# RastoBot-r2.net
KiCad netlist of a schematic drawn in EAGLE
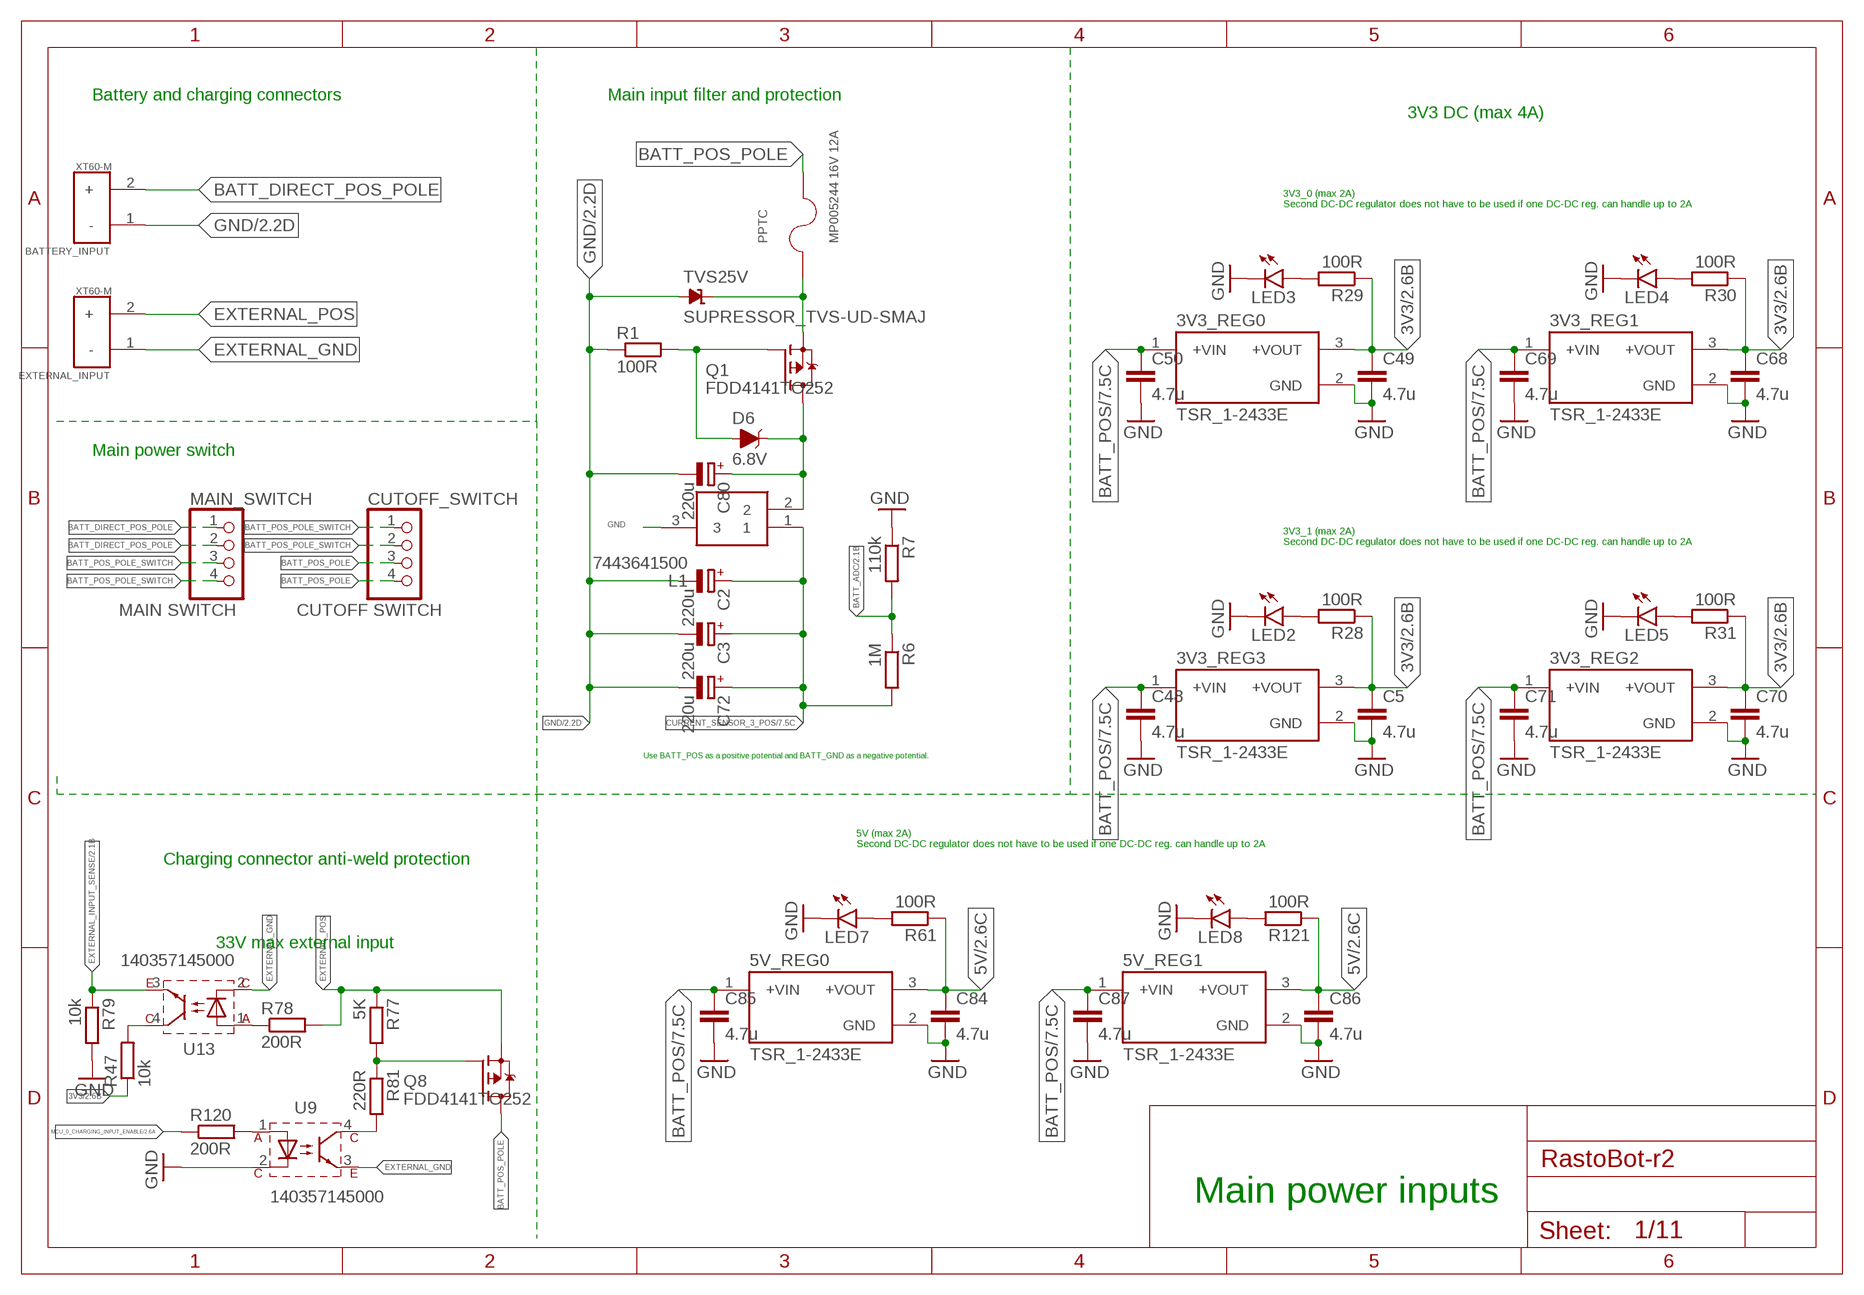
[diagram p0: schematic, sheet 1]
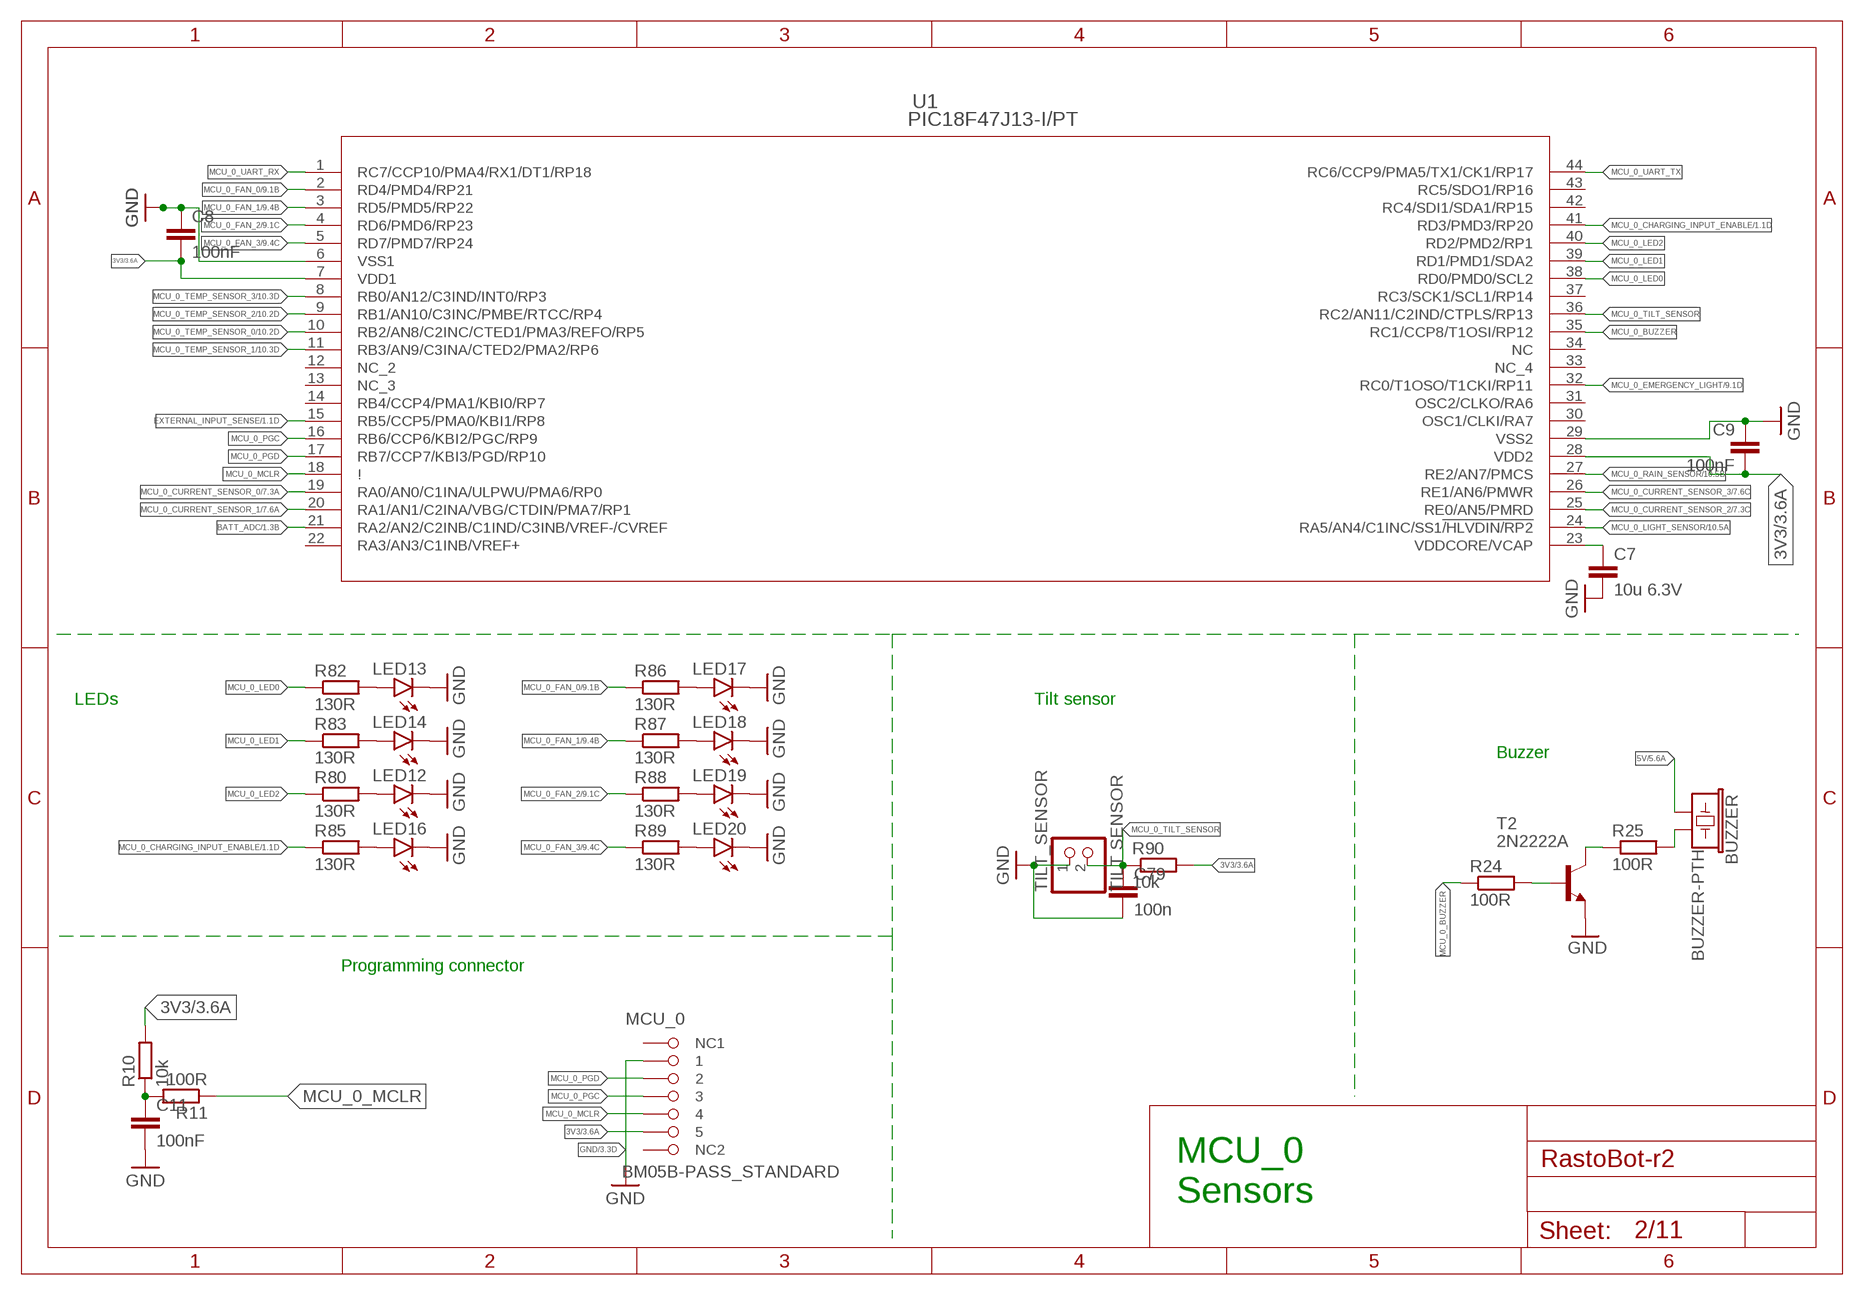
[diagram p1: schematic, sheet 2]
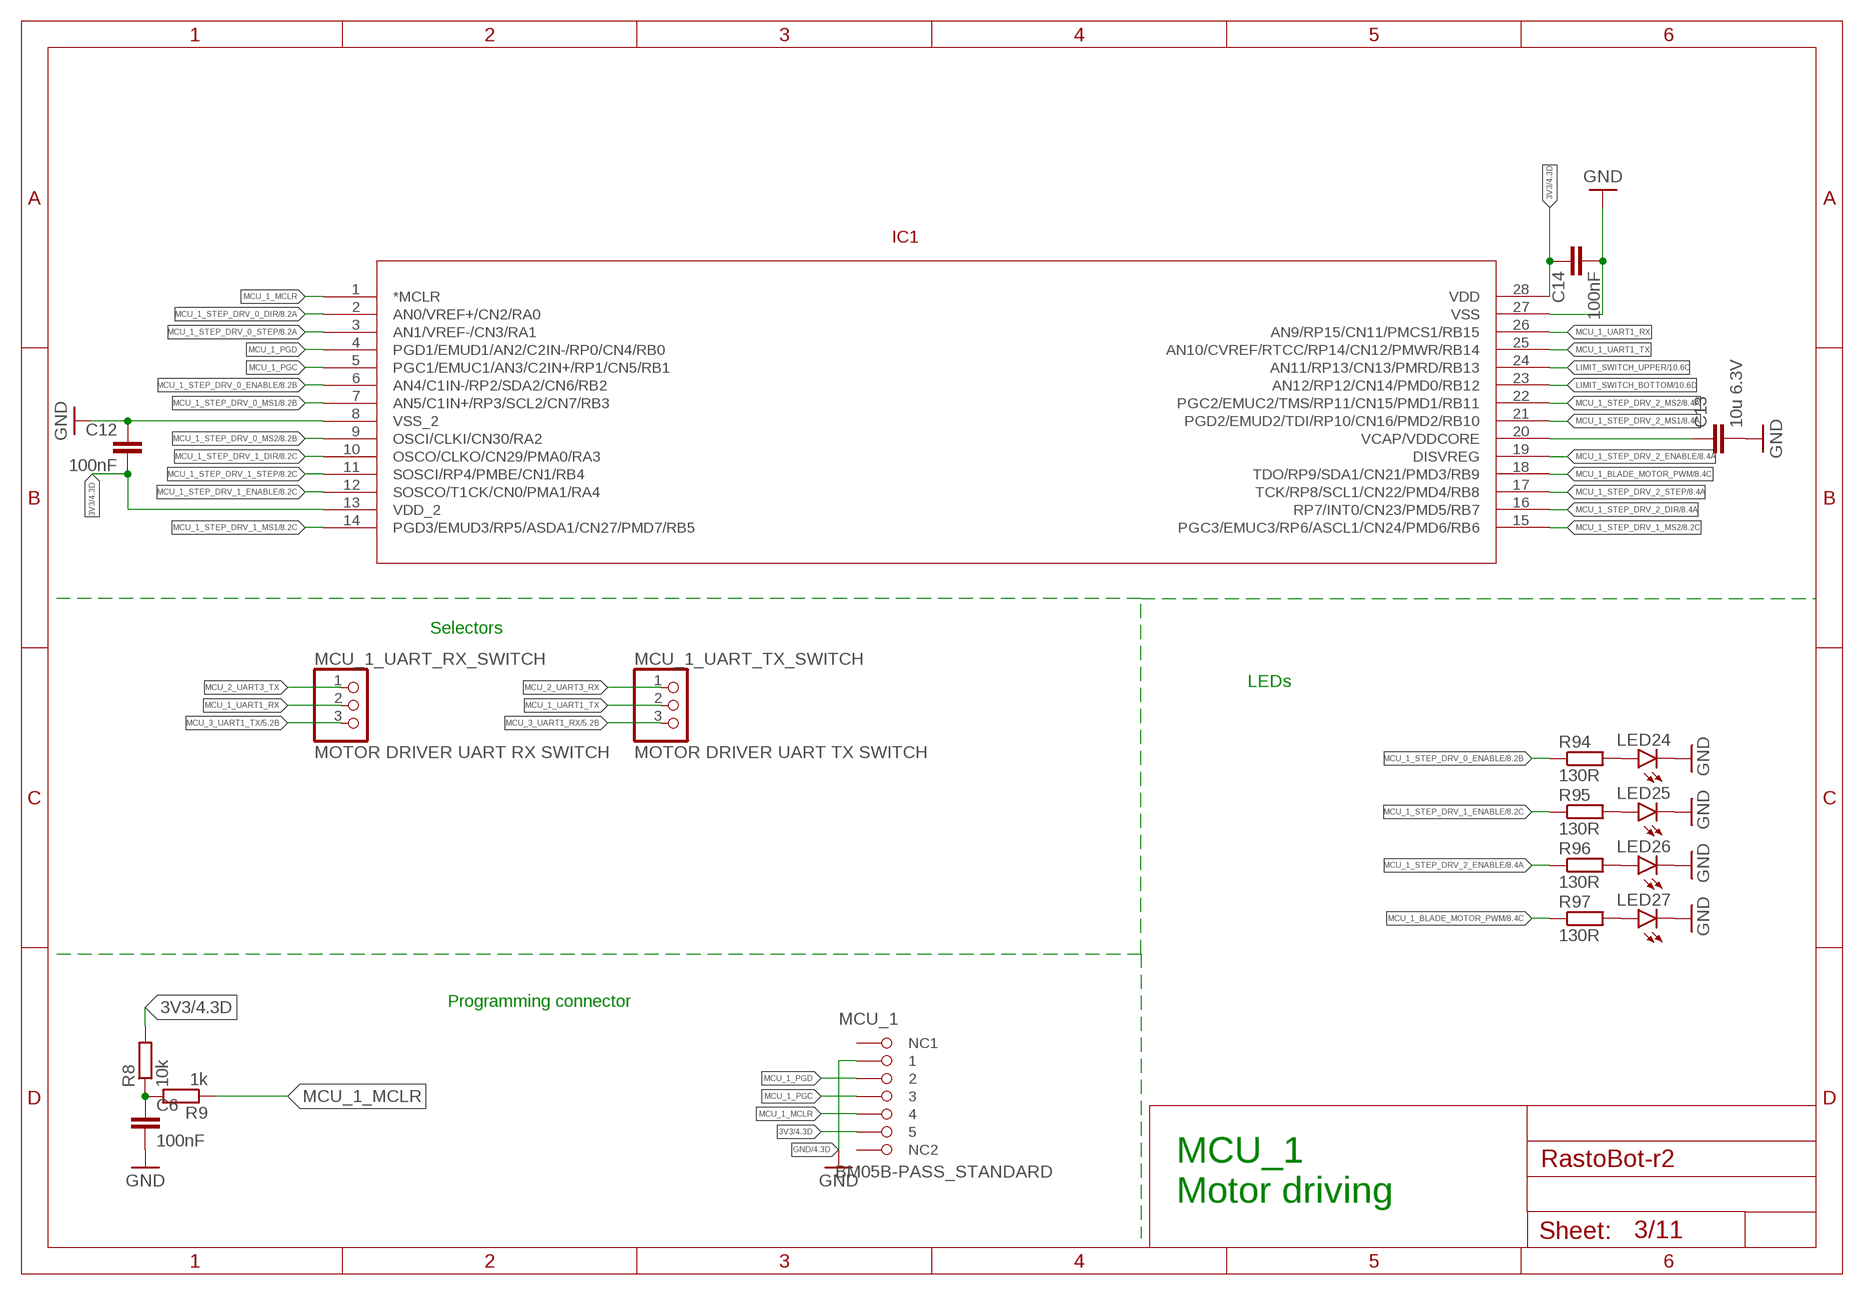
[diagram p2: schematic, sheet 3]
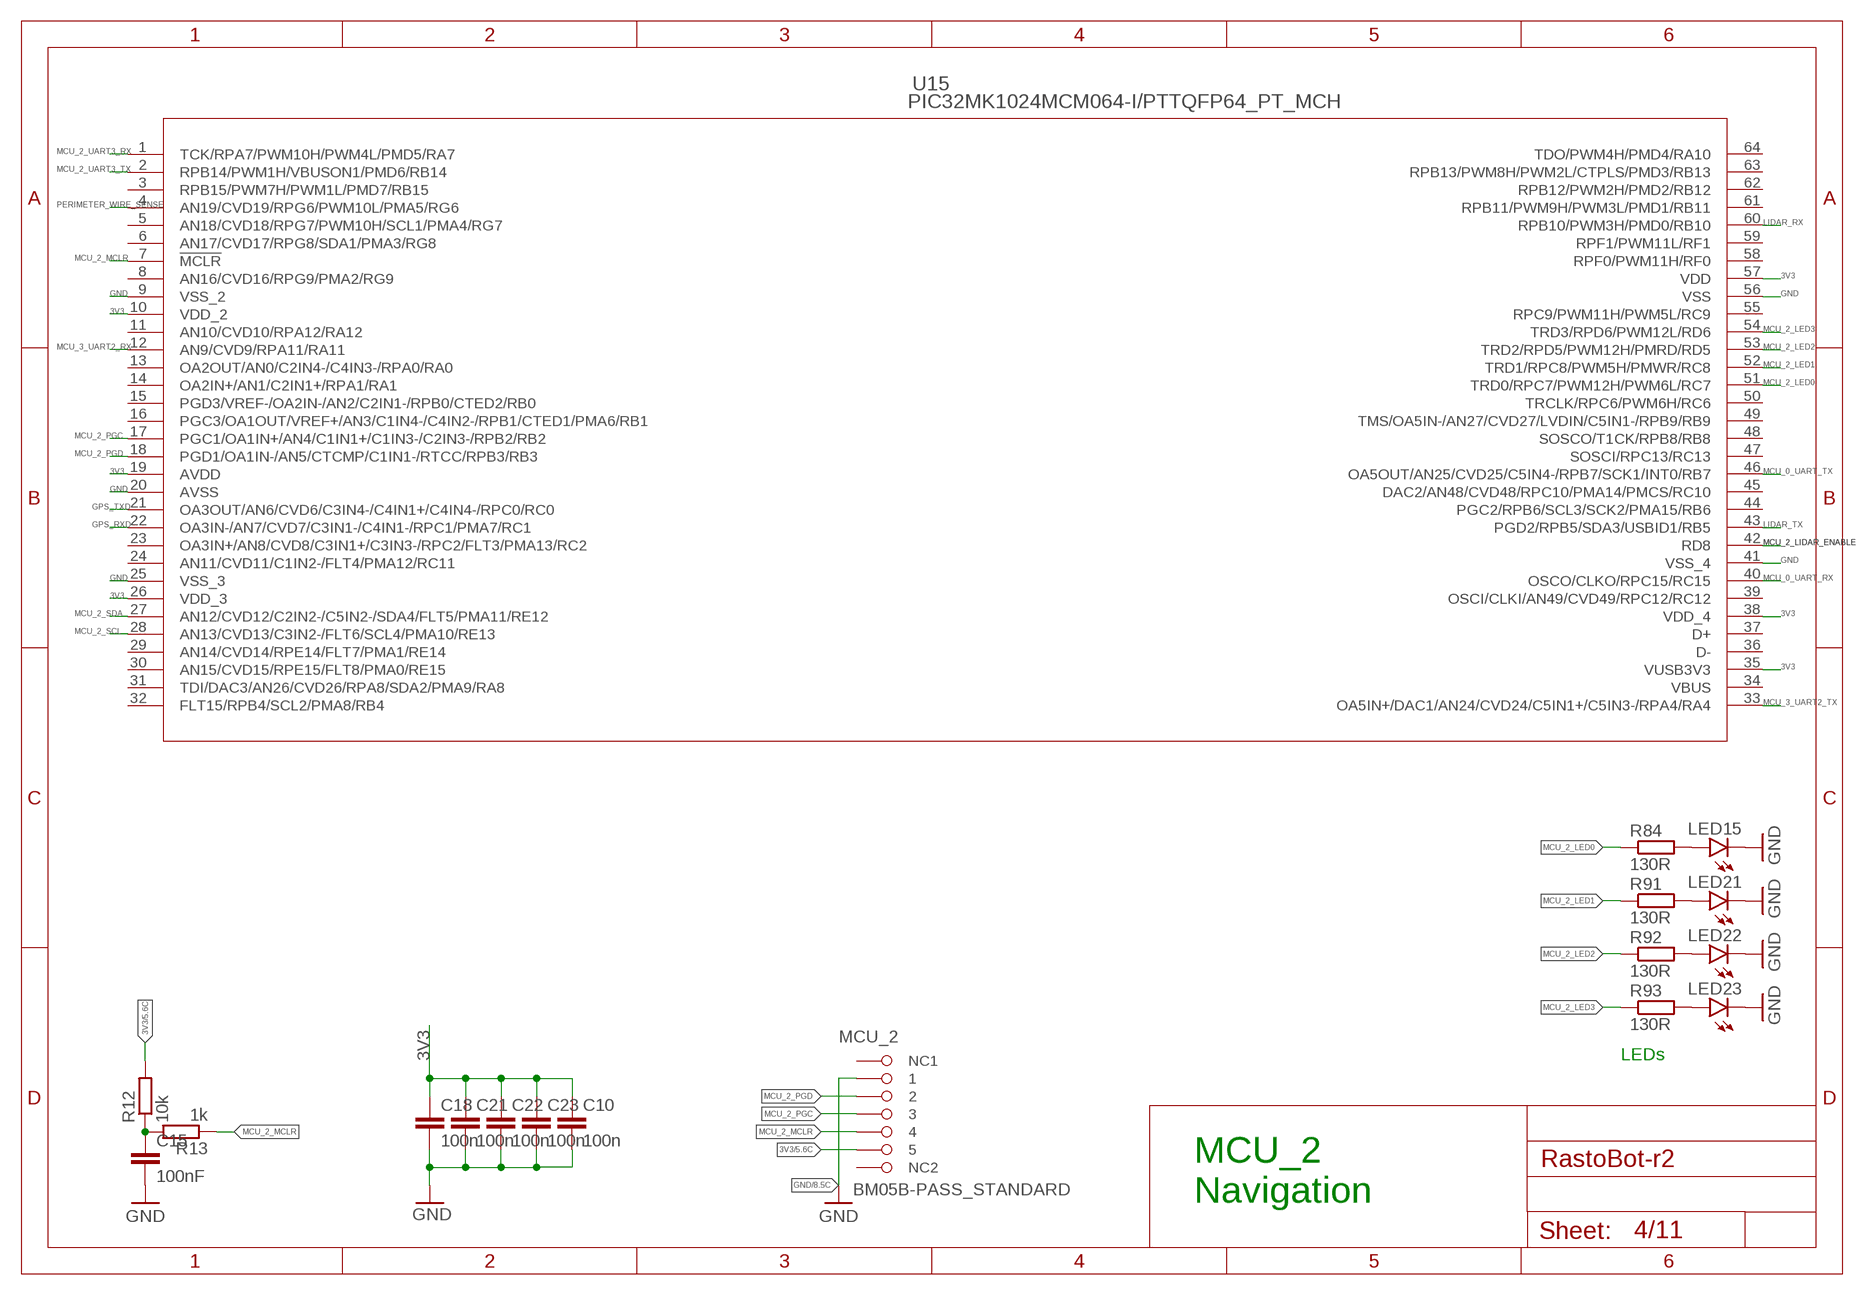
[diagram p3: schematic, sheet 4]
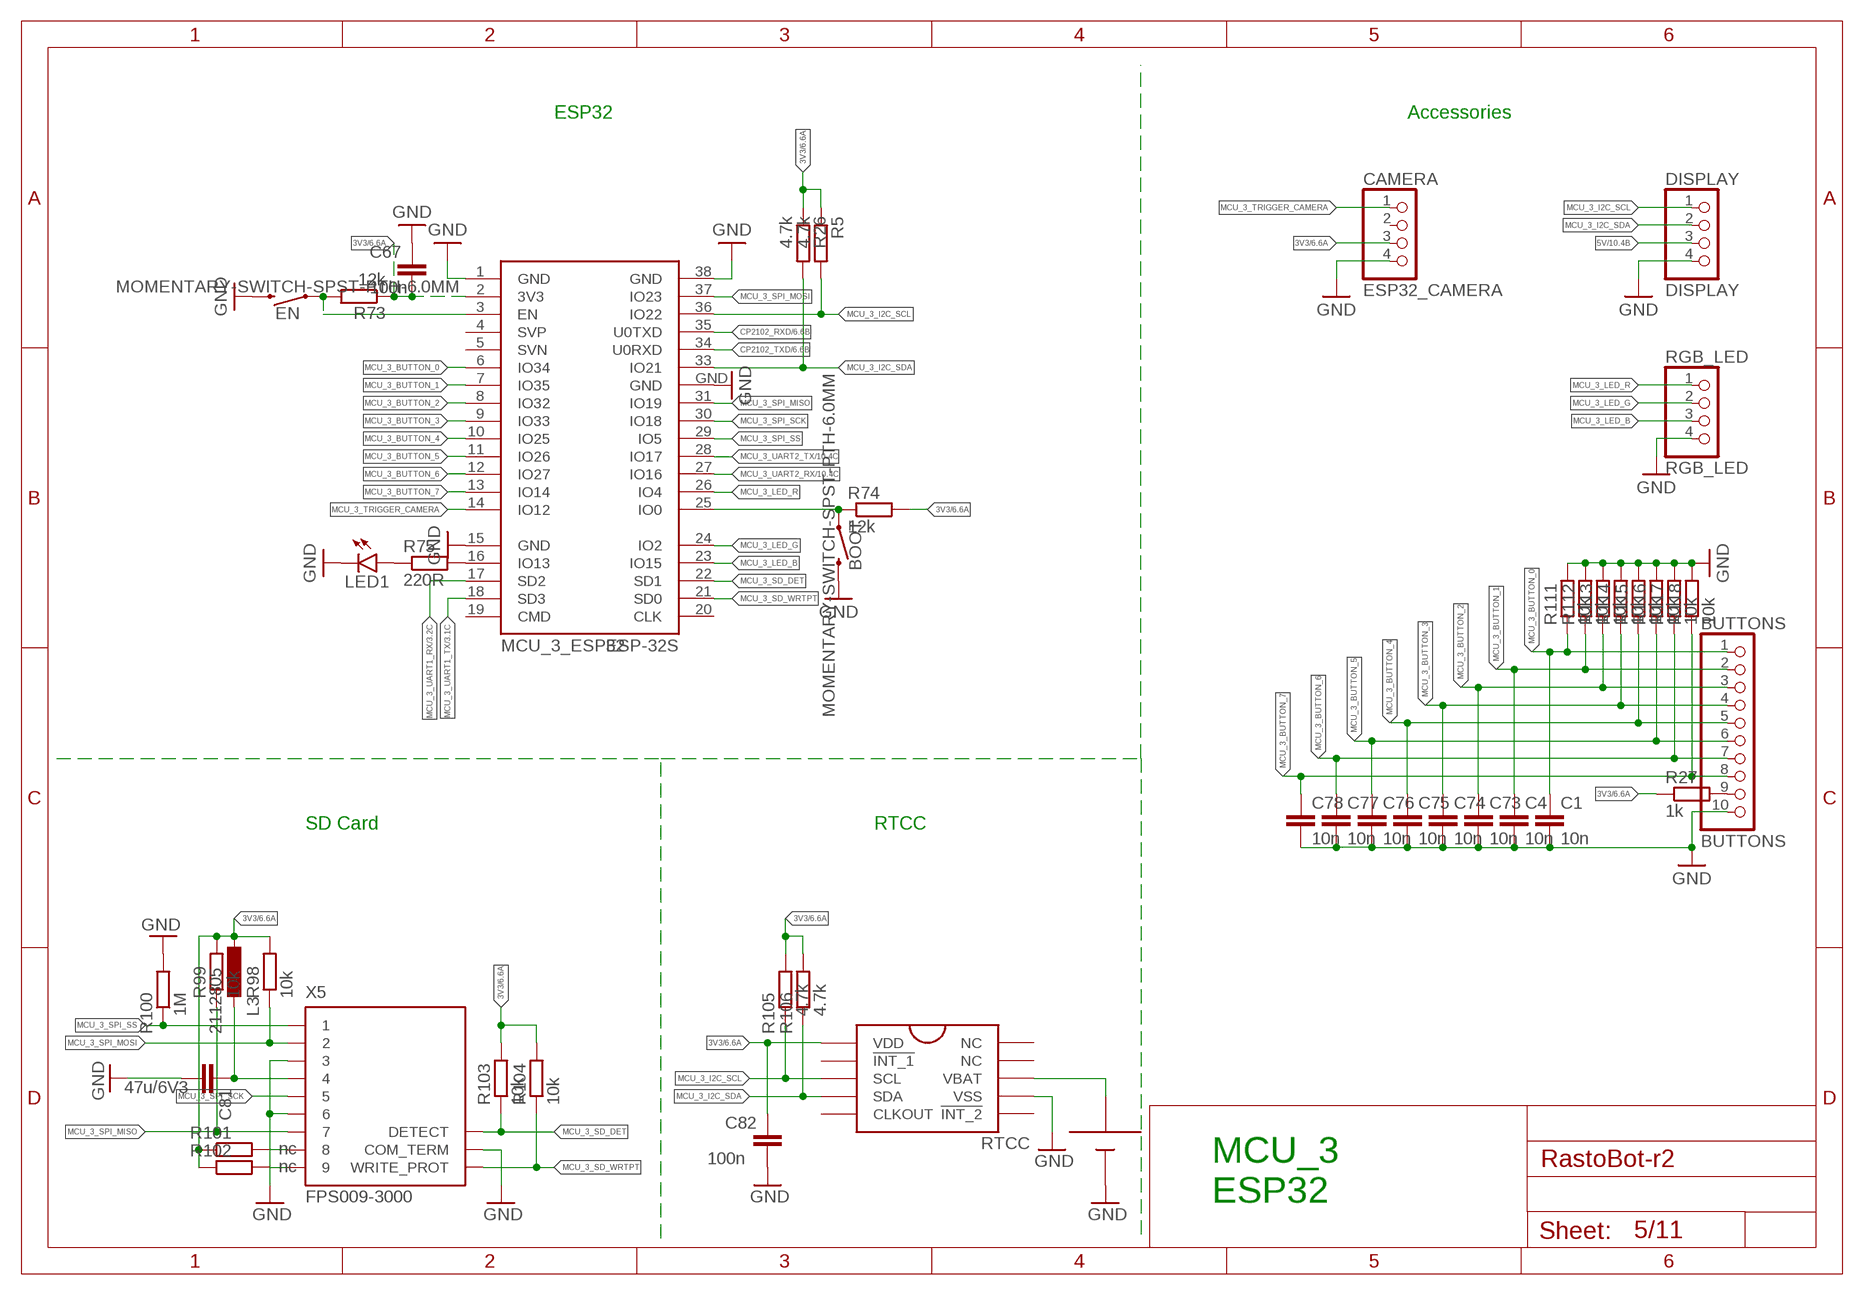
[diagram p4: schematic, sheet 5]
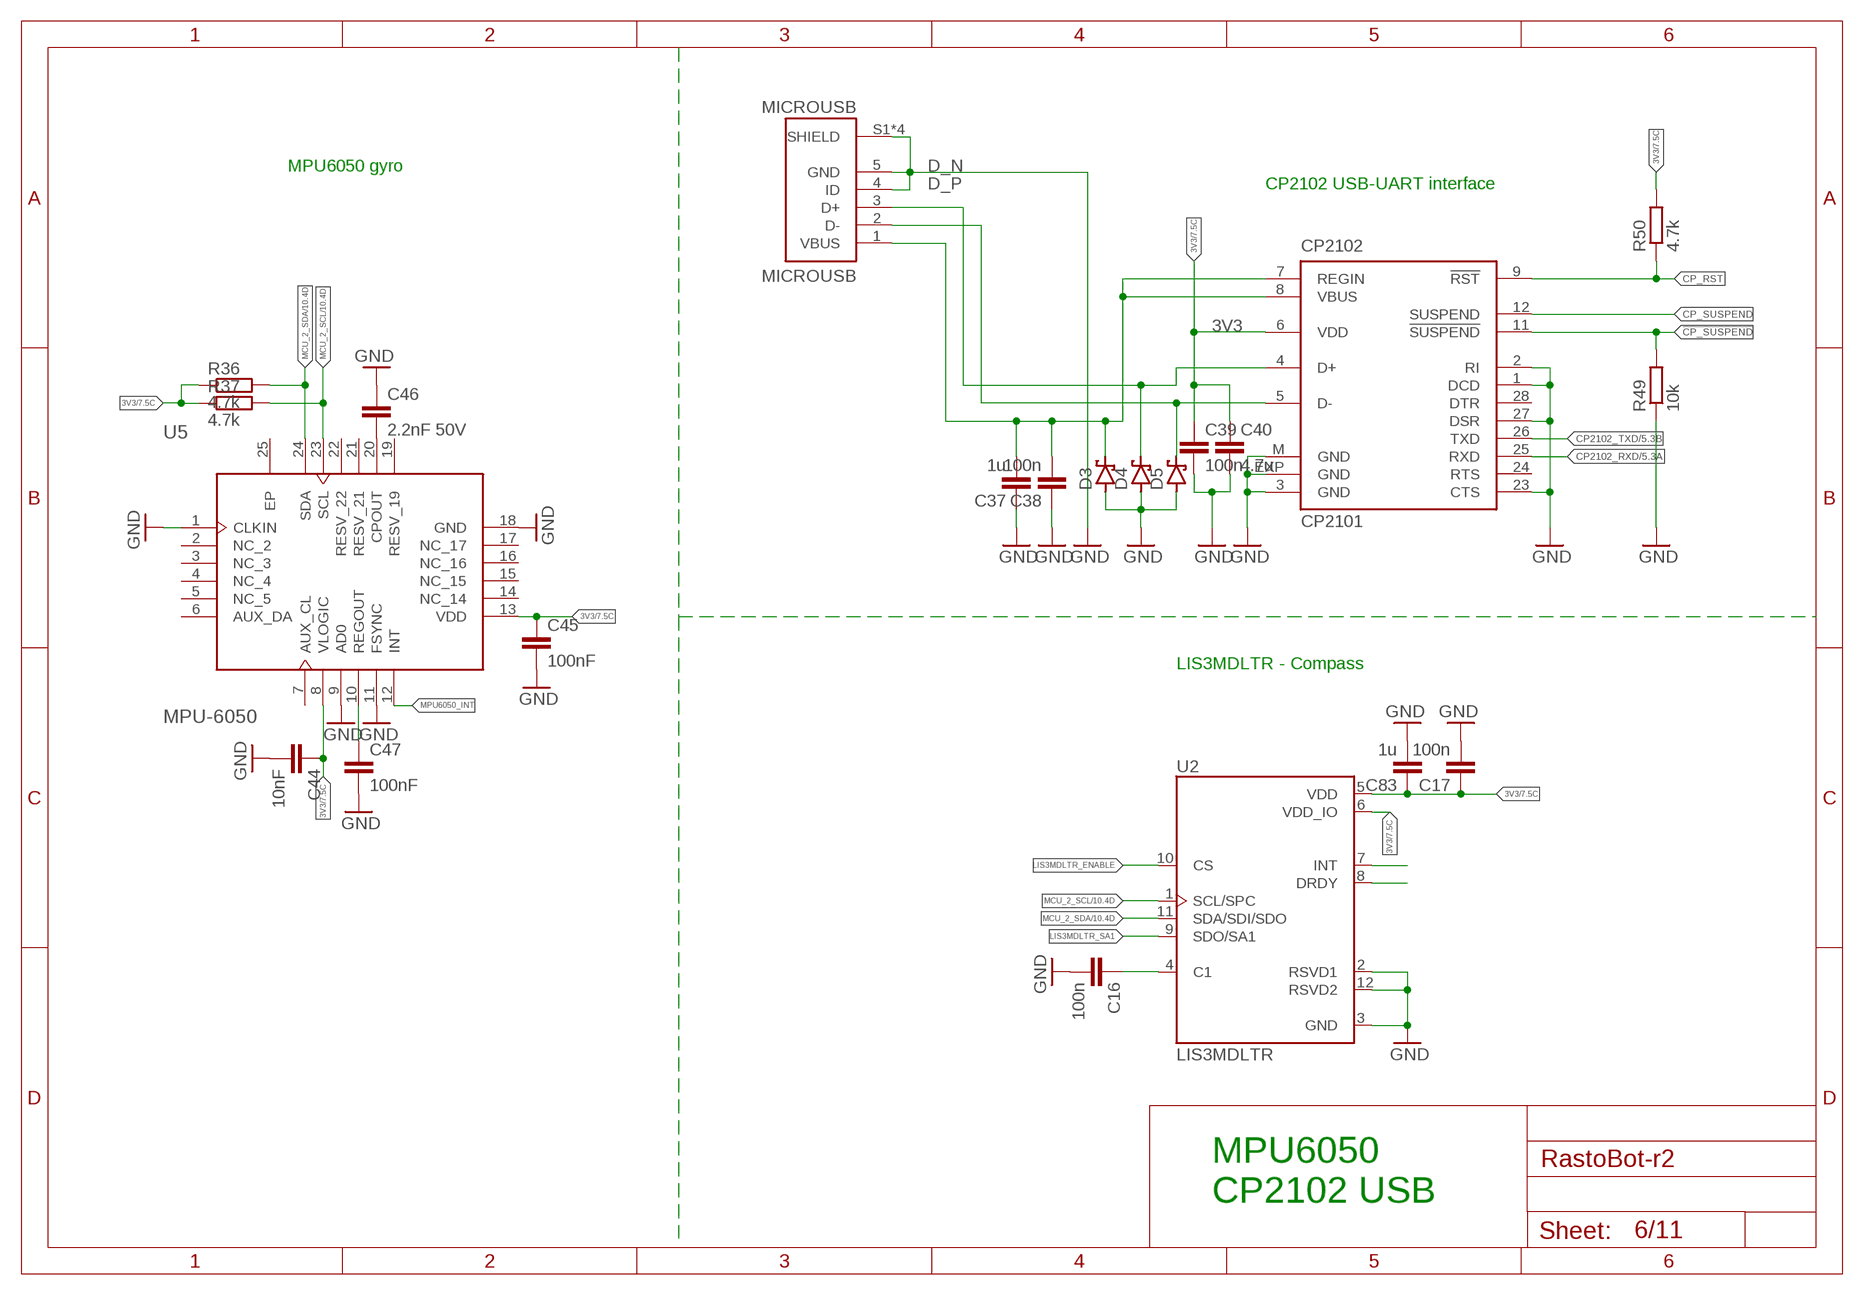
[diagram p5: schematic, sheet 6]
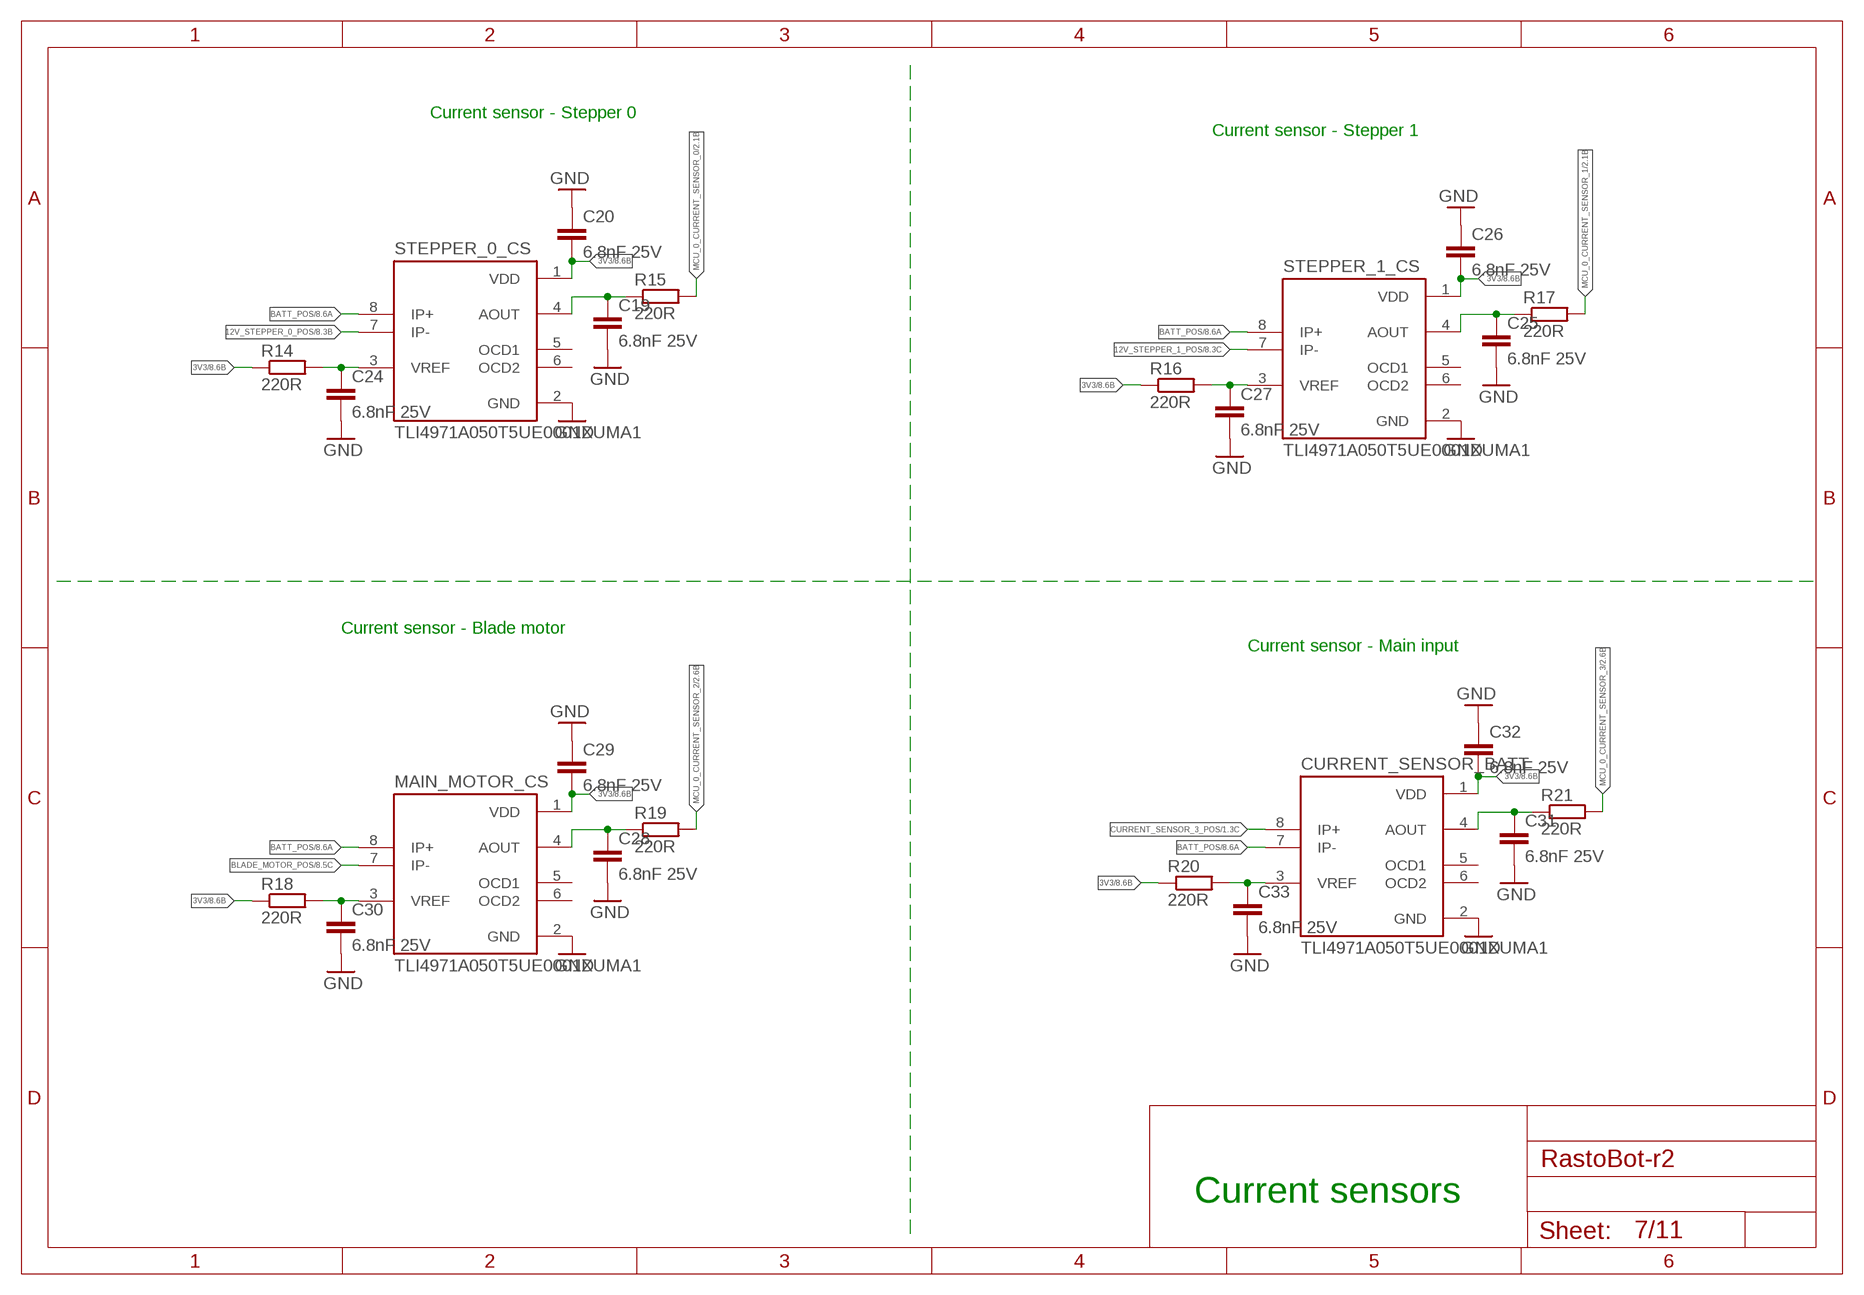
[diagram p6: schematic, sheet 7]
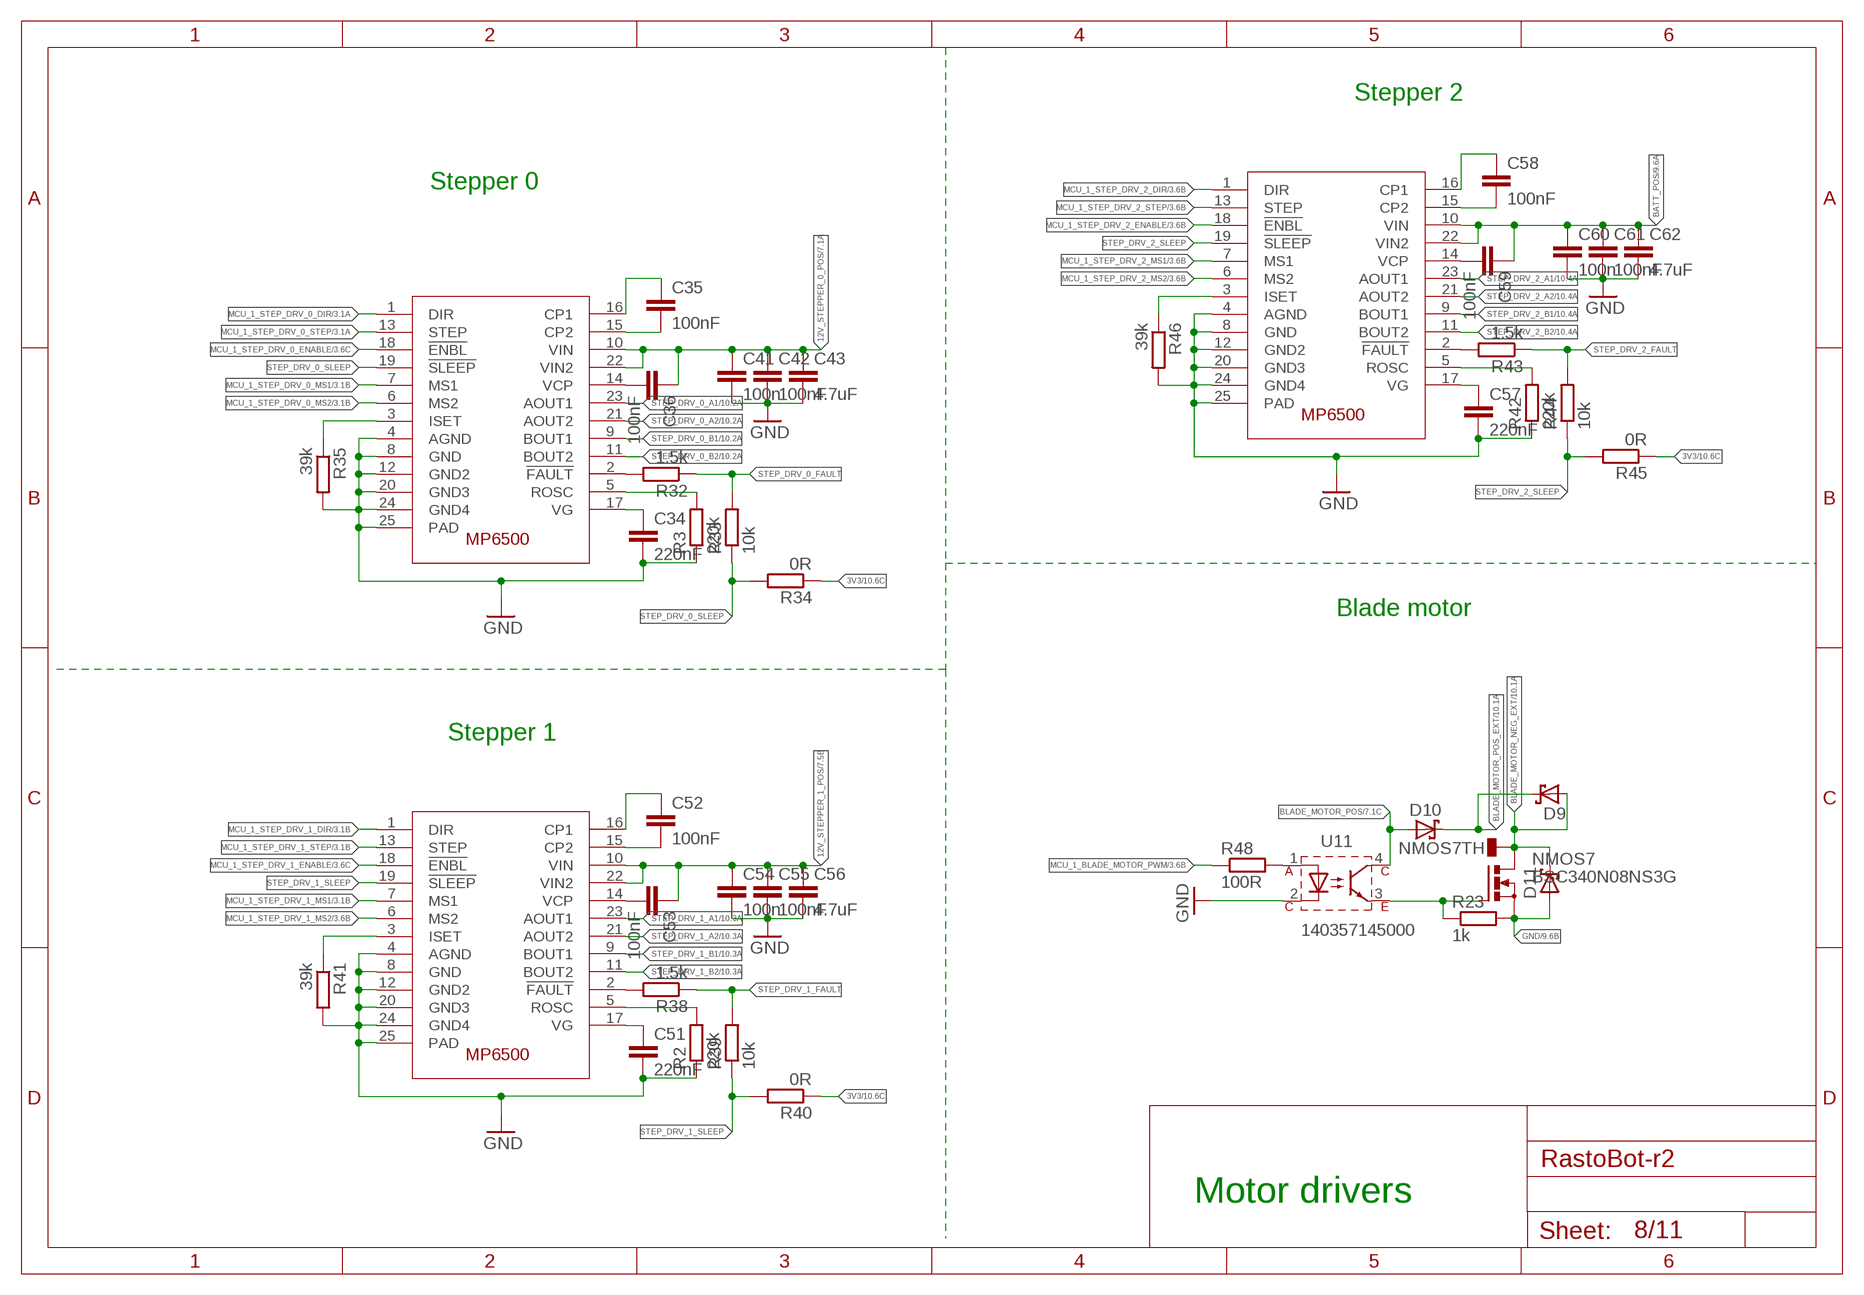
[diagram p7: schematic, sheet 8]
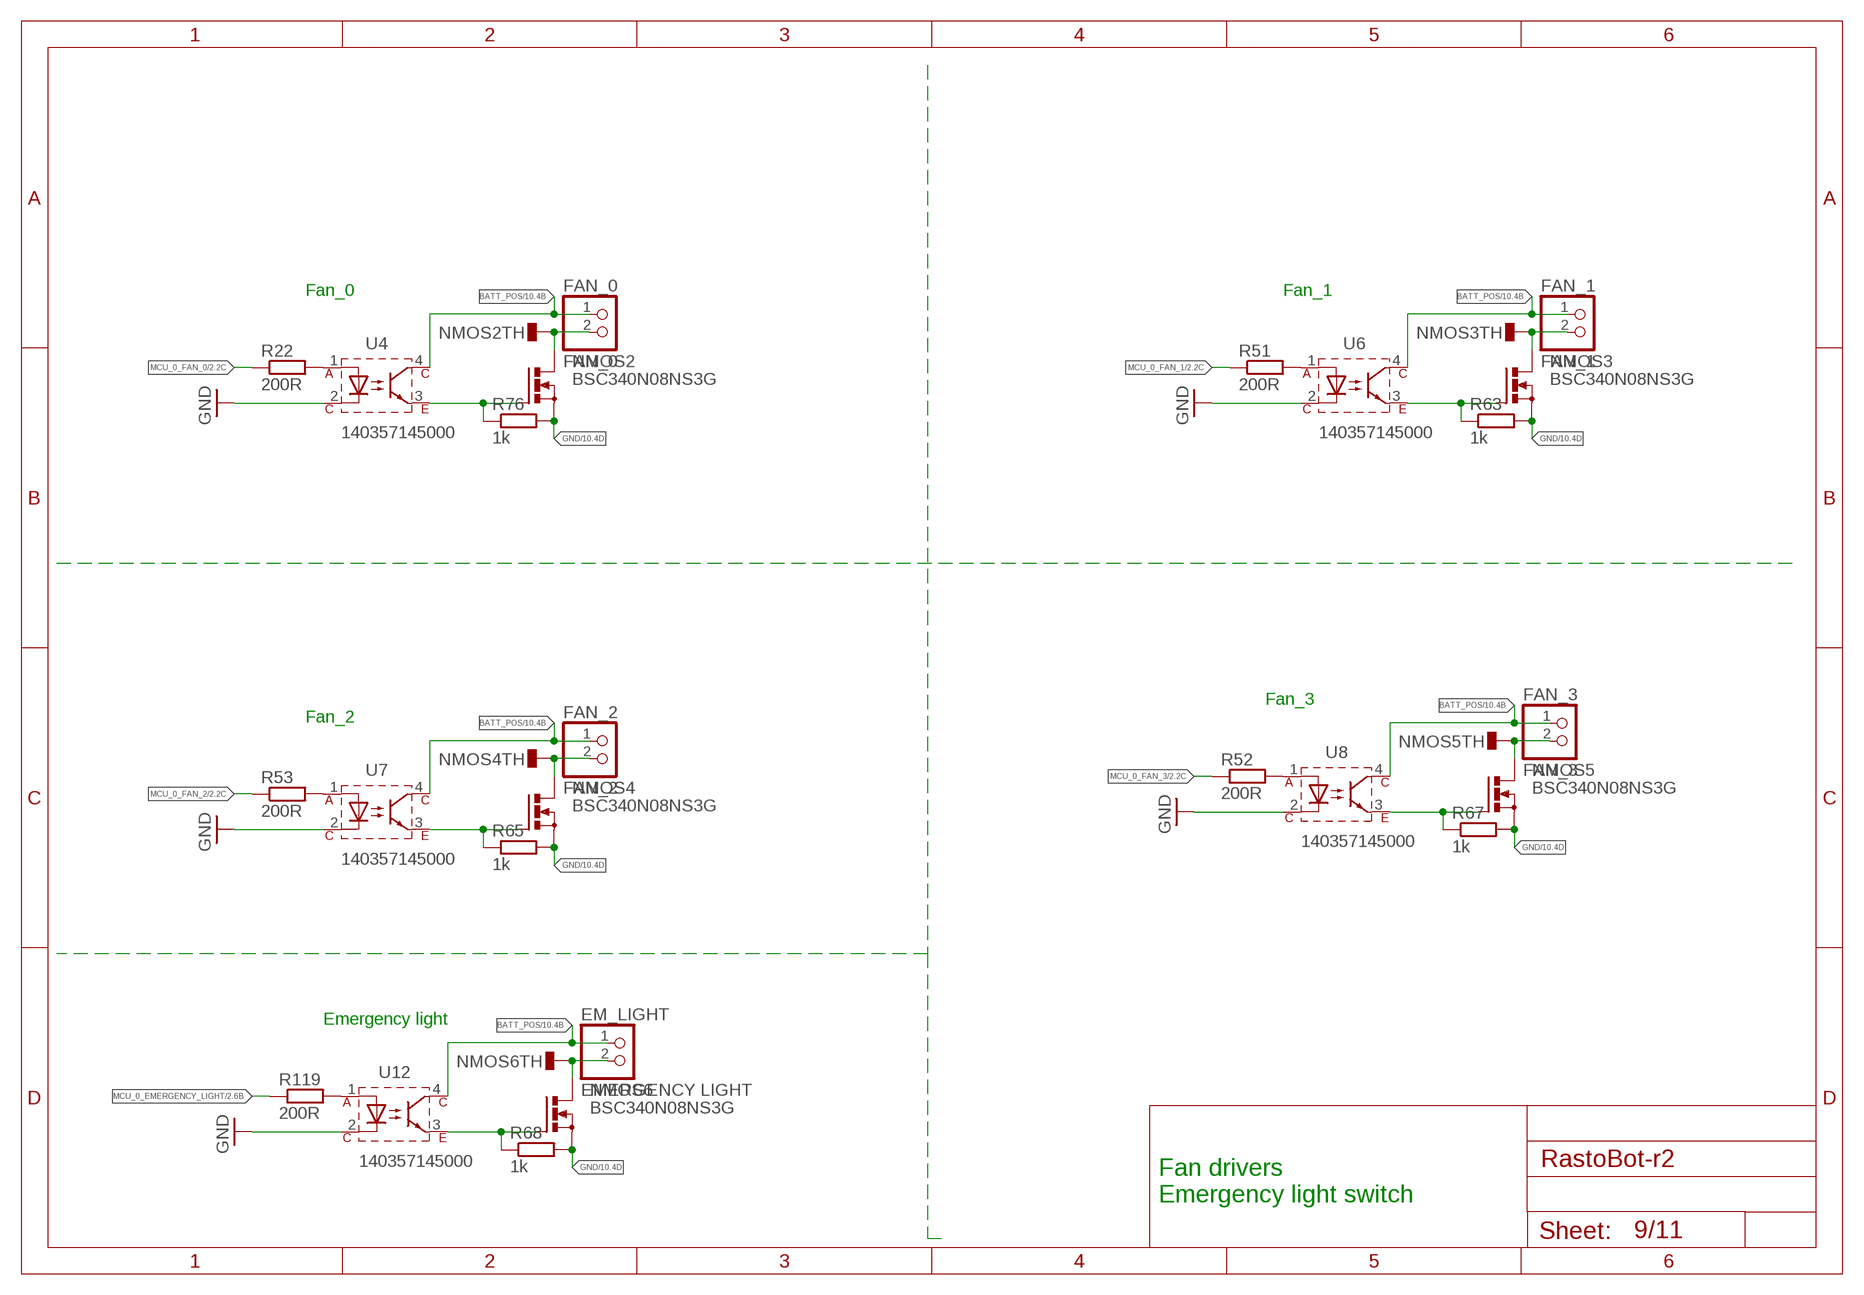
[diagram p8: schematic, sheet 9]
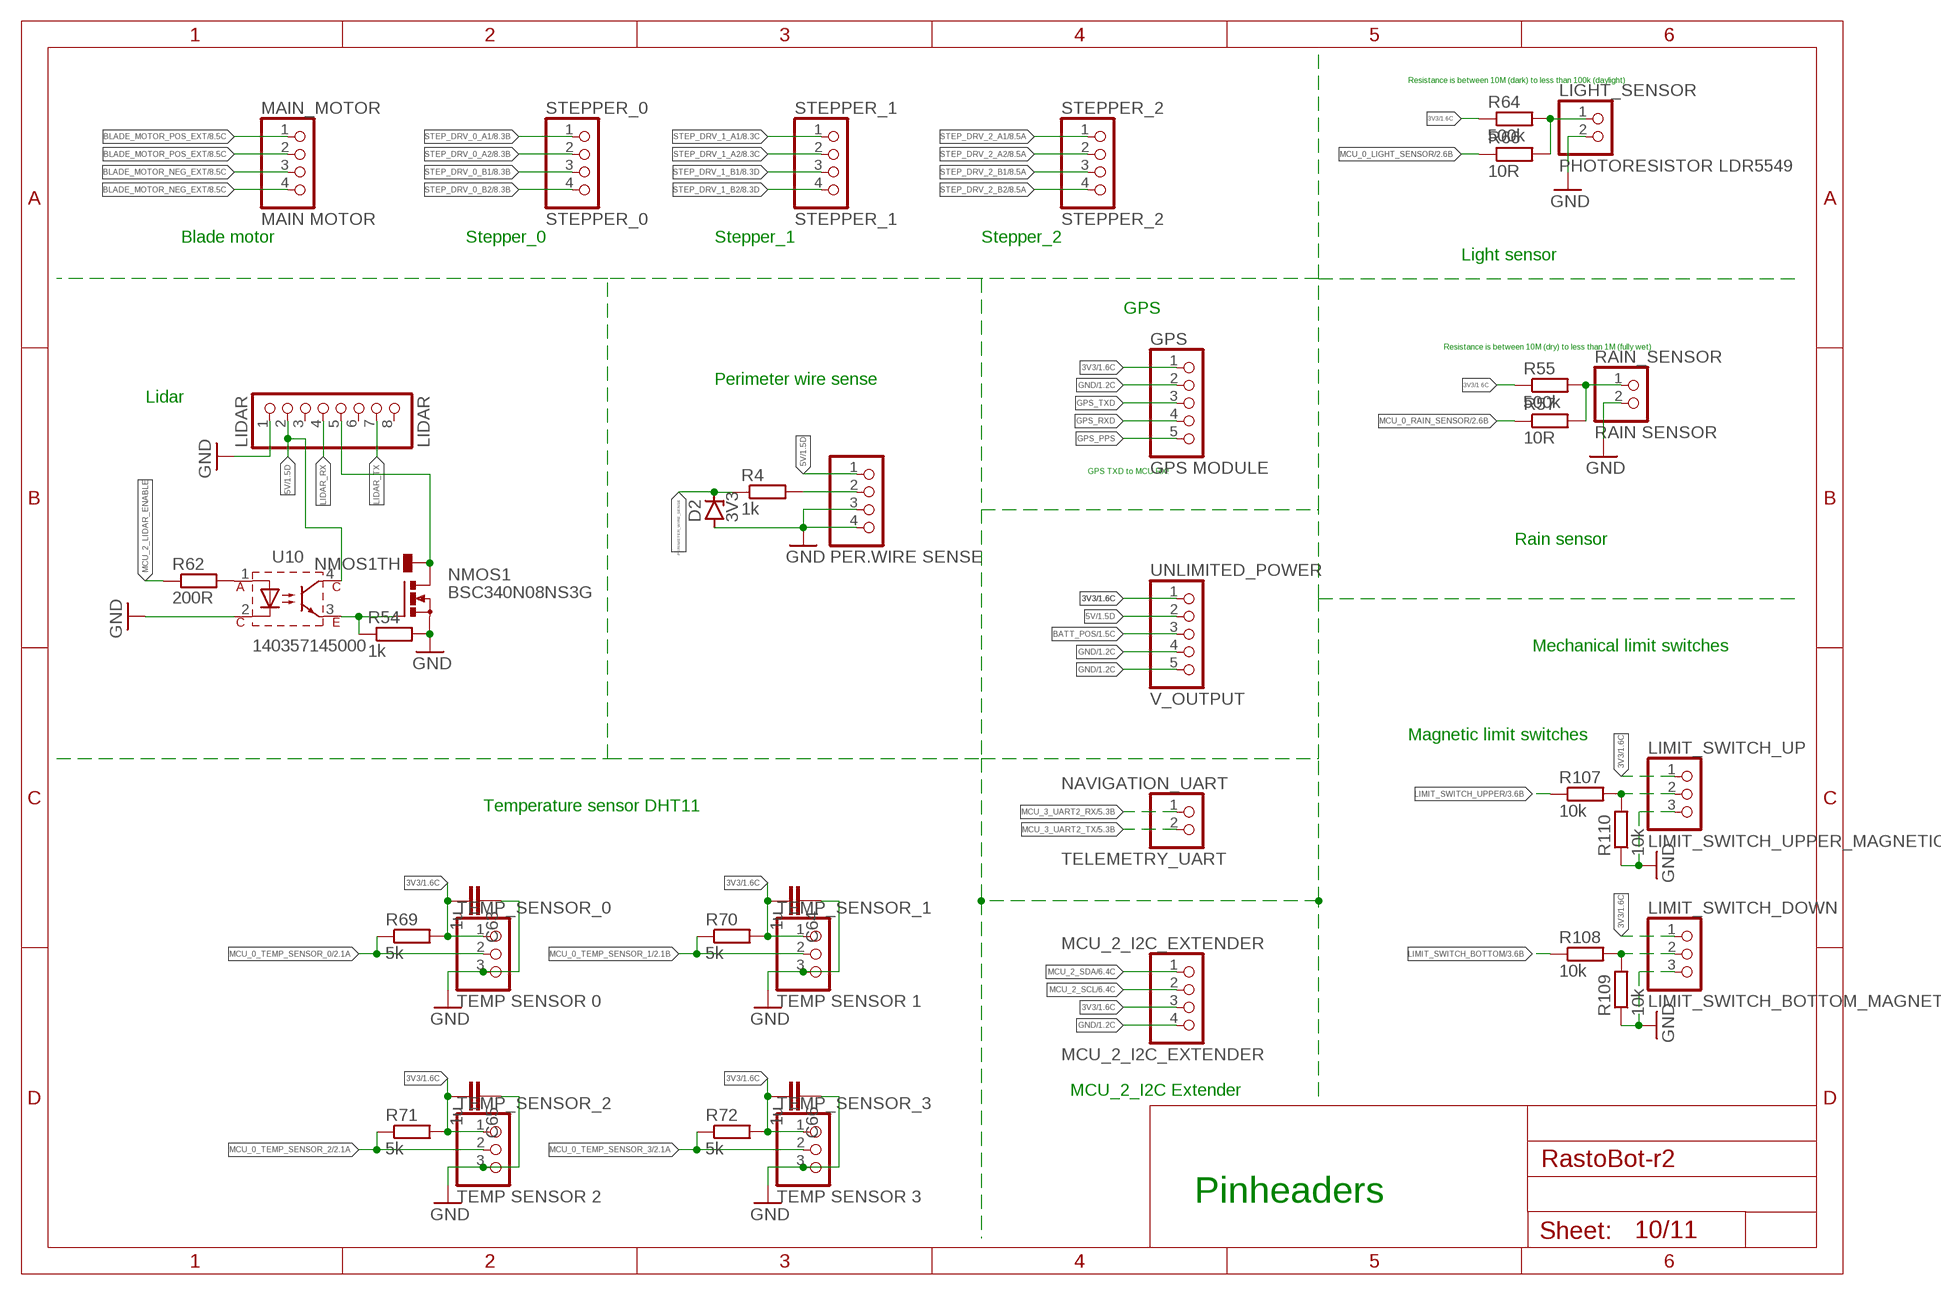
[diagram p9: schematic, sheet 10]
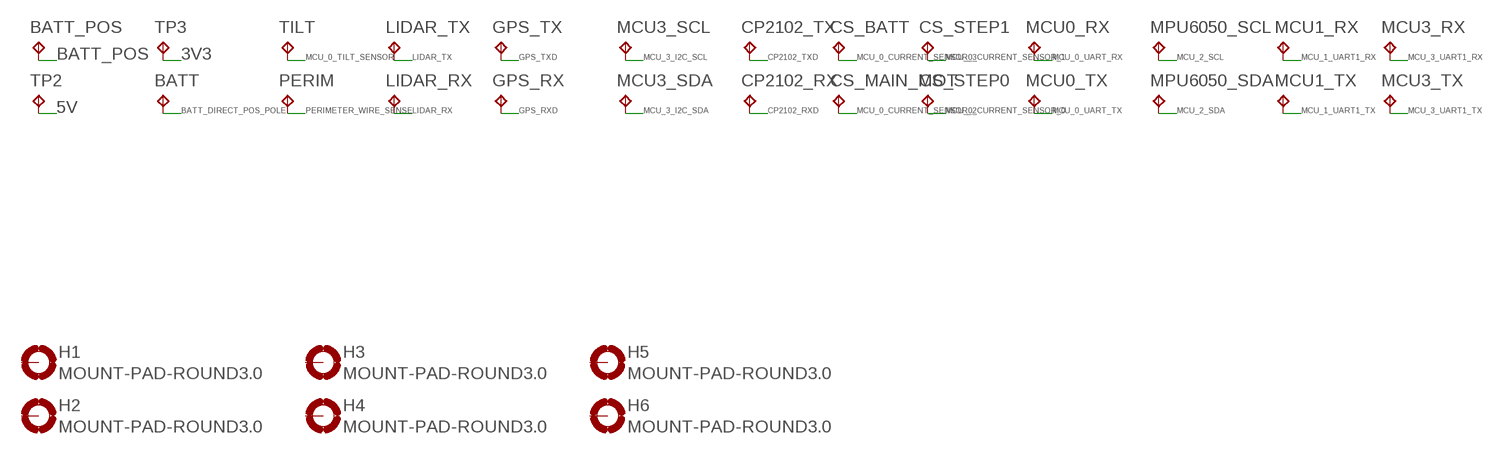
[diagram p10: schematic, sheet 11]

(export (version "E")
  (design (tool "Eeschema 10.0.6"))
  (components
    (comp (ref "BATT")
      (value "TPB1,27")
      (footprint "eagle-import:B1,27")
      (libsource (lib "eagle-import") (part "TPB1,27"))
    )
    (comp (ref "BATT_POS")
      (value "TPB1,27")
      (footprint "eagle-import:B1,27")
      (libsource (lib "eagle-import") (part "TPB1,27"))
    )
    (comp (ref "CP2102_RX")
      (value "TPB1,27")
      (footprint "eagle-import:B1,27")
      (libsource (lib "eagle-import") (part "TPB1,27"))
    )
    (comp (ref "CP2102_TX")
      (value "TPB1,27")
      (footprint "eagle-import:B1,27")
      (libsource (lib "eagle-import") (part "TPB1,27"))
    )
    (comp (ref "CS_BATT")
      (value "TPB1,27")
      (footprint "eagle-import:B1,27")
      (libsource (lib "eagle-import") (part "TPB1,27"))
    )
    (comp (ref "CS_MAIN_MOT")
      (value "TPB1,27")
      (footprint "eagle-import:B1,27")
      (libsource (lib "eagle-import") (part "TPB1,27"))
    )
    (comp (ref "CS_STEP0")
      (value "TPB1,27")
      (footprint "eagle-import:B1,27")
      (libsource (lib "eagle-import") (part "TPB1,27"))
    )
    (comp (ref "CS_STEP1")
      (value "TPB1,27")
      (footprint "eagle-import:B1,27")
      (libsource (lib "eagle-import") (part "TPB1,27"))
    )
    (comp (ref "GPS_RX")
      (value "TPB1,27")
      (footprint "eagle-import:B1,27")
      (libsource (lib "eagle-import") (part "TPB1,27"))
    )
    (comp (ref "GPS_TX")
      (value "TPB1,27")
      (footprint "eagle-import:B1,27")
      (libsource (lib "eagle-import") (part "TPB1,27"))
    )
    (comp (ref "H1")
      (value "MOUNT-PAD-ROUND3.0")
      (footprint "eagle-import:3,0-PAD")
      (libsource (lib "eagle-import") (part "MOUNT-PAD-ROUND3.0"))
    )
    (comp (ref "H2")
      (value "MOUNT-PAD-ROUND3.0")
      (footprint "eagle-import:3,0-PAD")
      (libsource (lib "eagle-import") (part "MOUNT-PAD-ROUND3.0"))
    )
    (comp (ref "H3")
      (value "MOUNT-PAD-ROUND3.0")
      (footprint "eagle-import:3,0-PAD")
      (libsource (lib "eagle-import") (part "MOUNT-PAD-ROUND3.0"))
    )
    (comp (ref "H4")
      (value "MOUNT-PAD-ROUND3.0")
      (footprint "eagle-import:3,0-PAD")
      (libsource (lib "eagle-import") (part "MOUNT-PAD-ROUND3.0"))
    )
    (comp (ref "H5")
      (value "MOUNT-PAD-ROUND3.0")
      (footprint "eagle-import:3,0-PAD")
      (libsource (lib "eagle-import") (part "MOUNT-PAD-ROUND3.0"))
    )
    (comp (ref "H6")
      (value "MOUNT-PAD-ROUND3.0")
      (footprint "eagle-import:3,0-PAD")
      (libsource (lib "eagle-import") (part "MOUNT-PAD-ROUND3.0"))
    )
    (comp (ref "LIDAR_RX")
      (value "TPB1,27")
      (footprint "eagle-import:B1,27")
      (libsource (lib "eagle-import") (part "TPB1,27"))
    )
    (comp (ref "LIDAR_TX")
      (value "TPB1,27")
      (footprint "eagle-import:B1,27")
      (libsource (lib "eagle-import") (part "TPB1,27"))
    )
    (comp (ref "MCU0_RX")
      (value "TPB1,27")
      (footprint "eagle-import:B1,27")
      (libsource (lib "eagle-import") (part "TPB1,27"))
    )
    (comp (ref "MCU0_TX")
      (value "TPB1,27")
      (footprint "eagle-import:B1,27")
      (libsource (lib "eagle-import") (part "TPB1,27"))
    )
    (comp (ref "MCU1_RX")
      (value "TPB1,27")
      (footprint "eagle-import:B1,27")
      (libsource (lib "eagle-import") (part "TPB1,27"))
    )
    (comp (ref "MCU1_TX")
      (value "TPB1,27")
      (footprint "eagle-import:B1,27")
      (libsource (lib "eagle-import") (part "TPB1,27"))
    )
    (comp (ref "MCU3_RX")
      (value "TPB1,27")
      (footprint "eagle-import:B1,27")
      (libsource (lib "eagle-import") (part "TPB1,27"))
    )
    (comp (ref "MCU3_SCL")
      (value "TPB1,27")
      (footprint "eagle-import:B1,27")
      (libsource (lib "eagle-import") (part "TPB1,27"))
    )
    (comp (ref "MCU3_SDA")
      (value "TPB1,27")
      (footprint "eagle-import:B1,27")
      (libsource (lib "eagle-import") (part "TPB1,27"))
    )
    (comp (ref "MCU3_TX")
      (value "TPB1,27")
      (footprint "eagle-import:B1,27")
      (libsource (lib "eagle-import") (part "TPB1,27"))
    )
    (comp (ref "MPU6050_SCL")
      (value "TPB1,27")
      (footprint "eagle-import:B1,27")
      (libsource (lib "eagle-import") (part "TPB1,27"))
    )
    (comp (ref "MPU6050_SDA")
      (value "TPB1,27")
      (footprint "eagle-import:B1,27")
      (libsource (lib "eagle-import") (part "TPB1,27"))
    )
    (comp (ref "PERIM")
      (value "TPB1,27")
      (footprint "eagle-import:B1,27")
      (libsource (lib "eagle-import") (part "TPB1,27"))
    )
    (comp (ref "TILT")
      (value "TPB1,27")
      (footprint "eagle-import:B1,27")
      (libsource (lib "eagle-import") (part "TPB1,27"))
    )
    (comp (ref "TP2")
      (value "TPB1,27")
      (footprint "eagle-import:B1,27")
      (libsource (lib "eagle-import") (part "TPB1,27"))
    )
    (comp (ref "TP3")
      (value "TPB1,27")
      (footprint "eagle-import:B1,27")
      (libsource (lib "eagle-import") (part "TPB1,27"))
    )
    (comp (ref "C10")
      (value "100n")
      (footprint "eagle-import:C0603")
      (libsource (lib "eagle-import") (part "C-EUC0603"))
    )
    (comp (ref "C15")
      (value "100nF")
      (footprint "eagle-import:C0603")
      (libsource (lib "eagle-import") (part "rcl_334_C-EUC0603"))
    )
    (comp (ref "C18")
      (value "100n")
      (footprint "eagle-import:C0603")
      (libsource (lib "eagle-import") (part "C-EUC0603"))
    )
    (comp (ref "C21")
      (value "100n")
      (footprint "eagle-import:C0603")
      (libsource (lib "eagle-import") (part "C-EUC0603"))
    )
    (comp (ref "C22")
      (value "100n")
      (footprint "eagle-import:C0603")
      (libsource (lib "eagle-import") (part "C-EUC0603"))
    )
    (comp (ref "C23")
      (value "100n")
      (footprint "eagle-import:C0603")
      (libsource (lib "eagle-import") (part "C-EUC0603"))
    )
    (comp (ref "LED15")
      (value "LEDSML0805")
      (footprint "eagle-import:SML0805")
      (libsource (lib "eagle-import") (part "LEDSML0805"))
    )
    (comp (ref "LED21")
      (value "LEDSML0805")
      (footprint "eagle-import:SML0805")
      (libsource (lib "eagle-import") (part "LEDSML0805"))
    )
    (comp (ref "LED22")
      (value "LEDSML0805")
      (footprint "eagle-import:SML0805")
      (libsource (lib "eagle-import") (part "LEDSML0805"))
    )
    (comp (ref "LED23")
      (value "LEDSML0805")
      (footprint "eagle-import:SML0805")
      (libsource (lib "eagle-import") (part "LEDSML0805"))
    )
    (comp (ref "MCU_2")
      (value "BM05B-PASS_STANDARD")
      (footprint "eagle-import:BM05B-PASS")
      (libsource (lib "eagle-import") (part "BM05B-PASS_STANDARD"))
    )
    (comp (ref "R12")
      (value "10k")
      (footprint "eagle-import:R0805")
      (libsource (lib "eagle-import") (part "rcl_334_R-EU_R0805"))
    )
    (comp (ref "R13")
      (value "1k")
      (footprint "eagle-import:R0805")
      (libsource (lib "eagle-import") (part "rcl_334_R-EU_R0805"))
    )
    (comp (ref "R84")
      (value "130R")
      (footprint "eagle-import:R0603")
      (libsource (lib "eagle-import") (part "rcl_334_R-EU_R0603"))
    )
    (comp (ref "R91")
      (value "130R")
      (footprint "eagle-import:R0603")
      (libsource (lib "eagle-import") (part "rcl_334_R-EU_R0603"))
    )
    (comp (ref "R92")
      (value "130R")
      (footprint "eagle-import:R0603")
      (libsource (lib "eagle-import") (part "rcl_334_R-EU_R0603"))
    )
    (comp (ref "R93")
      (value "130R")
      (footprint "eagle-import:R0603")
      (libsource (lib "eagle-import") (part "rcl_334_R-EU_R0603"))
    )
    (comp (ref "U15")
      (value "PIC32MK1024MCM064-I/PTTQFP64_PT_MCH")
      (footprint "eagle-import:TQFP64_PT_MCH")
      (fields
        (field (name "MANUFACTURER_PART_NUMBER") "PIC32MK1024MCM064-I/PT")
        (field (name "COPYRIGHT") "Copyright (C) 2022 Ultra Librarian. All rights reserved.")
      )
      (libsource (lib "eagle-import") (part "PIC32MK1024MCM064-I/PTTQFP64_PT_MCH"))
    )
    (comp (ref "C34")
      (value "220nF")
      (footprint "eagle-import:C0603")
      (libsource (lib "eagle-import") (part "rcl_334_C-EUC0603"))
    )
    (comp (ref "C35")
      (value "100nF")
      (footprint "eagle-import:C0603")
      (libsource (lib "eagle-import") (part "rcl_334_C-EUC0603"))
    )
    (comp (ref "C36")
      (value "100nF")
      (footprint "eagle-import:C0603")
      (libsource (lib "eagle-import") (part "rcl_334_C-EUC0603"))
    )
    (comp (ref "C41")
      (value "100n")
      (footprint "eagle-import:C0603")
      (libsource (lib "eagle-import") (part "rcl_334_C-EUC0603"))
    )
    (comp (ref "C42")
      (value "100nF")
      (footprint "eagle-import:C0603")
      (libsource (lib "eagle-import") (part "rcl_334_C-EUC0603"))
    )
    (comp (ref "C43")
      (value "4.7uF")
      (footprint "eagle-import:C0603")
      (libsource (lib "eagle-import") (part "rcl_334_C-EUC0603"))
    )
    (comp (ref "C51")
      (value "220nF")
      (footprint "eagle-import:C0603")
      (libsource (lib "eagle-import") (part "rcl_334_C-EUC0603"))
    )
    (comp (ref "C52")
      (value "100nF")
      (footprint "eagle-import:C0603")
      (libsource (lib "eagle-import") (part "rcl_334_C-EUC0603"))
    )
    (comp (ref "C53")
      (value "100nF")
      (footprint "eagle-import:C0603")
      (libsource (lib "eagle-import") (part "rcl_334_C-EUC0603"))
    )
    (comp (ref "C54")
      (value "100n")
      (footprint "eagle-import:C0603")
      (libsource (lib "eagle-import") (part "rcl_334_C-EUC0603"))
    )
    (comp (ref "C55")
      (value "100nF")
      (footprint "eagle-import:C0603")
      (libsource (lib "eagle-import") (part "rcl_334_C-EUC0603"))
    )
    (comp (ref "C56")
      (value "4.7uF")
      (footprint "eagle-import:C0603")
      (libsource (lib "eagle-import") (part "rcl_334_C-EUC0603"))
    )
    (comp (ref "C57")
      (value "220nF")
      (footprint "eagle-import:C0603")
      (libsource (lib "eagle-import") (part "rcl_334_C-EUC0603"))
    )
    (comp (ref "C58")
      (value "100nF")
      (footprint "eagle-import:C0603")
      (libsource (lib "eagle-import") (part "rcl_334_C-EUC0603"))
    )
    (comp (ref "C59")
      (value "100nF")
      (footprint "eagle-import:C0603")
      (libsource (lib "eagle-import") (part "rcl_334_C-EUC0603"))
    )
    (comp (ref "C60")
      (value "100n")
      (footprint "eagle-import:C0603")
      (libsource (lib "eagle-import") (part "rcl_334_C-EUC0603"))
    )
    (comp (ref "C61")
      (value "100nF")
      (footprint "eagle-import:C0603")
      (libsource (lib "eagle-import") (part "rcl_334_C-EUC0603"))
    )
    (comp (ref "C62")
      (value "4.7uF")
      (footprint "eagle-import:C0603")
      (libsource (lib "eagle-import") (part "rcl_334_C-EUC0603"))
    )
    (comp (ref "D9")
      (value "SCHOTTKY-DIODEAG")
      (footprint "eagle-import:AG")
      (libsource (lib "eagle-import") (part "SCHOTTKY-DIODEAG"))
    )
    (comp (ref "D10")
      (value "SCHOTTKY-DIODEAG")
      (footprint "eagle-import:AG")
      (libsource (lib "eagle-import") (part "SCHOTTKY-DIODEAG"))
    )
    (comp (ref "D11")
      (value "SCHOTTKY-DIODEAG")
      (footprint "eagle-import:AG")
      (libsource (lib "eagle-import") (part "SCHOTTKY-DIODEAG"))
    )
    (comp (ref "NMOS7")
      (value "BSC340N08NS3G")
      (footprint "eagle-import:PG-TDSON-8")
      (libsource (lib "eagle-import") (part "BSC340N08NS3G"))
    )
    (comp (ref "R2")
      (value "220k")
      (footprint "eagle-import:R0603")
      (libsource (lib "eagle-import") (part "rcl_334_R-EU_R0603"))
    )
    (comp (ref "R3")
      (value "220k")
      (footprint "eagle-import:R0603")
      (libsource (lib "eagle-import") (part "rcl_334_R-EU_R0603"))
    )
    (comp (ref "R23")
      (value "1k")
      (footprint "eagle-import:R0805")
      (libsource (lib "eagle-import") (part "rcl_334_R-EU_R0805"))
    )
    (comp (ref "R32")
      (value "1.5k")
      (footprint "eagle-import:R0603")
      (libsource (lib "eagle-import") (part "rcl_334_R-EU_R0603"))
    )
    (comp (ref "R33")
      (value "10k")
      (footprint "eagle-import:R0603")
      (libsource (lib "eagle-import") (part "rcl_334_R-EU_R0603"))
    )
    (comp (ref "R34")
      (value "0R")
      (footprint "eagle-import:R0603")
      (libsource (lib "eagle-import") (part "rcl_334_R-EU_R0603"))
    )
    (comp (ref "R35")
      (value "39k")
      (footprint "eagle-import:R0603")
      (libsource (lib "eagle-import") (part "rcl_334_R-EU_R0603"))
    )
    (comp (ref "R38")
      (value "1.5k")
      (footprint "eagle-import:R0603")
      (libsource (lib "eagle-import") (part "rcl_334_R-EU_R0603"))
    )
    (comp (ref "R39")
      (value "10k")
      (footprint "eagle-import:R0603")
      (libsource (lib "eagle-import") (part "rcl_334_R-EU_R0603"))
    )
    (comp (ref "R40")
      (value "0R")
      (footprint "eagle-import:R0603")
      (libsource (lib "eagle-import") (part "rcl_334_R-EU_R0603"))
    )
    (comp (ref "R41")
      (value "39k")
      (footprint "eagle-import:R0603")
      (libsource (lib "eagle-import") (part "rcl_334_R-EU_R0603"))
    )
    (comp (ref "R42")
      (value "220k")
      (footprint "eagle-import:R0603")
      (libsource (lib "eagle-import") (part "rcl_334_R-EU_R0603"))
    )
    (comp (ref "R43")
      (value "1.5k")
      (footprint "eagle-import:R0603")
      (libsource (lib "eagle-import") (part "rcl_334_R-EU_R0603"))
    )
    (comp (ref "R44")
      (value "10k")
      (footprint "eagle-import:R0603")
      (libsource (lib "eagle-import") (part "rcl_334_R-EU_R0603"))
    )
    (comp (ref "R45")
      (value "0R")
      (footprint "eagle-import:R0603")
      (libsource (lib "eagle-import") (part "rcl_334_R-EU_R0603"))
    )
    (comp (ref "R46")
      (value "39k")
      (footprint "eagle-import:R0603")
      (libsource (lib "eagle-import") (part "rcl_334_R-EU_R0603"))
    )
    (comp (ref "R48")
      (value "100R")
      (footprint "eagle-import:R0805")
      (libsource (lib "eagle-import") (part "rcl_334_R-EU_R0805"))
    )
    (comp (ref "SD1")
      (value "MP6500")
      (footprint "eagle-import:QFN65P500X500X100-25N")
      (libsource (lib "eagle-import") (part "MP6500"))
    )
    (comp (ref "SD2")
      (value "MP6500")
      (footprint "eagle-import:QFN65P500X500X100-25N")
      (libsource (lib "eagle-import") (part "MP6500"))
    )
    (comp (ref "SD3")
      (value "MP6500")
      (footprint "eagle-import:QFN65P500X500X100-25N")
      (libsource (lib "eagle-import") (part "MP6500"))
    )
    (comp (ref "U11")
      (value "140357145000")
      (footprint "eagle-import:WL-OCPT_SOP4")
      (libsource (lib "eagle-import") (part "WL-OCPT_SERIES_357_140357145000"))
    )
    (comp (ref "BUZZER")
      (value "BUZZER-PTH")
      (footprint "eagle-import:BUZZER-12MM")
      (libsource (lib "eagle-import") (part "BUZZER-PTH"))
    )
    (comp (ref "C7")
      (value "10u 6.3V")
      (footprint "eagle-import:C1206")
      (libsource (lib "eagle-import") (part "rcl_334_C-EUC1206"))
    )
    (comp (ref "C8")
      (value "100nF")
      (footprint "eagle-import:C0603")
      (libsource (lib "eagle-import") (part "rcl_334_C-EUC0603"))
    )
    (comp (ref "C9")
      (value "100nF")
      (footprint "eagle-import:C0603")
      (libsource (lib "eagle-import") (part "rcl_334_C-EUC0603"))
    )
    (comp (ref "C11")
      (value "100nF")
      (footprint "eagle-import:C0603")
      (libsource (lib "eagle-import") (part "rcl_334_C-EUC0603"))
    )
    (comp (ref "C79")
      (value "100n")
      (footprint "eagle-import:C1206")
      (libsource (lib "eagle-import") (part "rcl_334_C-EUC1206"))
    )
    (comp (ref "LED12")
      (value "LEDSML0805")
      (footprint "eagle-import:SML0805")
      (libsource (lib "eagle-import") (part "LEDSML0805"))
    )
    (comp (ref "LED13")
      (value "LEDSML0805")
      (footprint "eagle-import:SML0805")
      (libsource (lib "eagle-import") (part "LEDSML0805"))
    )
    (comp (ref "LED14")
      (value "LEDSML0805")
      (footprint "eagle-import:SML0805")
      (libsource (lib "eagle-import") (part "LEDSML0805"))
    )
    (comp (ref "LED16")
      (value "LEDSML0805")
      (footprint "eagle-import:SML0805")
      (libsource (lib "eagle-import") (part "LEDSML0805"))
    )
    (comp (ref "LED17")
      (value "LEDSML0805")
      (footprint "eagle-import:SML0805")
      (libsource (lib "eagle-import") (part "LEDSML0805"))
    )
    (comp (ref "LED18")
      (value "LEDSML0805")
      (footprint "eagle-import:SML0805")
      (libsource (lib "eagle-import") (part "LEDSML0805"))
    )
    (comp (ref "LED19")
      (value "LEDSML0805")
      (footprint "eagle-import:SML0805")
      (libsource (lib "eagle-import") (part "LEDSML0805"))
    )
    (comp (ref "LED20")
      (value "LEDSML0805")
      (footprint "eagle-import:SML0805")
      (libsource (lib "eagle-import") (part "LEDSML0805"))
    )
    (comp (ref "MCU_0")
      (value "BM05B-PASS_STANDARD")
      (footprint "eagle-import:BM05B-PASS")
      (libsource (lib "eagle-import") (part "BM05B-PASS_STANDARD"))
    )
    (comp (ref "R10")
      (value "10k")
      (footprint "eagle-import:R0805")
      (libsource (lib "eagle-import") (part "rcl_334_R-EU_R0805"))
    )
    (comp (ref "R11")
      (value "100R")
      (footprint "eagle-import:R0805")
      (libsource (lib "eagle-import") (part "rcl_334_R-EU_R0805"))
    )
    (comp (ref "R24")
      (value "100R")
      (footprint "eagle-import:R0805")
      (libsource (lib "eagle-import") (part "rcl_334_R-EU_R0805"))
    )
    (comp (ref "R25")
      (value "100R")
      (footprint "eagle-import:R0805")
      (libsource (lib "eagle-import") (part "rcl_334_R-EU_R0805"))
    )
    (comp (ref "R80")
      (value "130R")
      (footprint "eagle-import:R0603")
      (libsource (lib "eagle-import") (part "rcl_334_R-EU_R0603"))
    )
    (comp (ref "R82")
      (value "130R")
      (footprint "eagle-import:R0603")
      (libsource (lib "eagle-import") (part "rcl_334_R-EU_R0603"))
    )
    (comp (ref "R83")
      (value "130R")
      (footprint "eagle-import:R0603")
      (libsource (lib "eagle-import") (part "rcl_334_R-EU_R0603"))
    )
    (comp (ref "R85")
      (value "130R")
      (footprint "eagle-import:R0603")
      (libsource (lib "eagle-import") (part "rcl_334_R-EU_R0603"))
    )
    (comp (ref "R86")
      (value "130R")
      (footprint "eagle-import:R0603")
      (libsource (lib "eagle-import") (part "rcl_334_R-EU_R0603"))
    )
    (comp (ref "R87")
      (value "130R")
      (footprint "eagle-import:R0603")
      (libsource (lib "eagle-import") (part "rcl_334_R-EU_R0603"))
    )
    (comp (ref "R88")
      (value "130R")
      (footprint "eagle-import:R0603")
      (libsource (lib "eagle-import") (part "rcl_334_R-EU_R0603"))
    )
    (comp (ref "R89")
      (value "130R")
      (footprint "eagle-import:R0603")
      (libsource (lib "eagle-import") (part "rcl_334_R-EU_R0603"))
    )
    (comp (ref "R90")
      (value "10k")
      (footprint "eagle-import:R0603")
      (libsource (lib "eagle-import") (part "rcl_334_R-EU_R0603"))
    )
    (comp (ref "T2")
      (value "2N2222A")
      (footprint "eagle-import:TO92-CBE")
      (libsource (lib "eagle-import") (part "-NPN-TO92-CBEBC547"))
    )
    (comp (ref "TILT_SENSOR")
      (value "TILT SENSOR")
      (footprint "eagle-import:1X02")
      (libsource (lib "eagle-import") (part "PINHD-1X2"))
    )
    (comp (ref "U1")
      (value "PIC18F47J13-I/PT")
      (footprint "eagle-import:TQFP44_10X10MC_MCH")
      (fields
        (field (name "MANUFACTURER_PART_NUMBER") "pic18f47j13-i/pt")
        (field (name "COPYRIGHT") "Copyright (C) 2022 Ultra Librarian. All rights reserved.")
      )
      (libsource (lib "eagle-import") (part "PIC18F47J13-I/PT"))
    )
    (comp (ref "3V3_REG0")
      (value "TSR_1-2433E")
      (footprint "eagle-import:CONV_TSR_1-2433E")
      (fields (field (name "MF") "Traco Power") (field (name "MP") "TSR 1-2433E"))
      (libsource (lib "eagle-import") (part "TSR_1-2433E"))
    )
    (comp (ref "3V3_REG1")
      (value "TSR_1-2433E")
      (footprint "eagle-import:CONV_TSR_1-2433E")
      (fields (field (name "MF") "Traco Power") (field (name "MP") "TSR 1-2433E"))
      (libsource (lib "eagle-import") (part "TSR_1-2433E"))
    )
    (comp (ref "3V3_REG2")
      (value "TSR_1-2433E")
      (footprint "eagle-import:CONV_TSR_1-2433E")
      (fields (field (name "MF") "Traco Power") (field (name "MP") "TSR 1-2433E"))
      (libsource (lib "eagle-import") (part "TSR_1-2433E"))
    )
    (comp (ref "3V3_REG3")
      (value "TSR_1-2433E")
      (footprint "eagle-import:CONV_TSR_1-2433E")
      (fields (field (name "MF") "Traco Power") (field (name "MP") "TSR 1-2433E"))
      (libsource (lib "eagle-import") (part "TSR_1-2433E"))
    )
    (comp (ref "5V_REG0")
      (value "TSR_1-2433E")
      (footprint "eagle-import:CONV_TSR_1-2433E")
      (fields (field (name "MF") "Traco Power") (field (name "MP") "TSR 1-2433E"))
      (libsource (lib "eagle-import") (part "TSR_1-2433E"))
    )
    (comp (ref "5V_REG1")
      (value "TSR_1-2433E")
      (footprint "eagle-import:CONV_TSR_1-2433E")
      (fields (field (name "MF") "Traco Power") (field (name "MP") "TSR 1-2433E"))
      (libsource (lib "eagle-import") (part "TSR_1-2433E"))
    )
    (comp (ref "BATTERY_INPUT")
      (value "XT60-M")
      (footprint "eagle-import:AMASS_XT60-M")
      (fields (field (name "MF") "AMASS"))
      (libsource (lib "eagle-import") (part "XT60-M"))
    )
    (comp (ref "C2")
      (value "220u")
      (footprint "eagle-import:E2,5-5")
      (libsource (lib "eagle-import") (part "CPOL-EUE2.5-5"))
    )
    (comp (ref "C3")
      (value "220u")
      (footprint "eagle-import:E2,5-5")
      (libsource (lib "eagle-import") (part "CPOL-EUE2.5-5"))
    )
    (comp (ref "C5")
      (value "4.7u")
      (footprint "eagle-import:C1206")
      (libsource (lib "eagle-import") (part "rcl_334_C-EUC1206"))
    )
    (comp (ref "C48")
      (value "4.7u")
      (footprint "eagle-import:C1206")
      (libsource (lib "eagle-import") (part "rcl_334_C-EUC1206"))
    )
    (comp (ref "C49")
      (value "4.7u")
      (footprint "eagle-import:C1206")
      (libsource (lib "eagle-import") (part "rcl_334_C-EUC1206"))
    )
    (comp (ref "C50")
      (value "4.7u")
      (footprint "eagle-import:C1206")
      (libsource (lib "eagle-import") (part "rcl_334_C-EUC1206"))
    )
    (comp (ref "C68")
      (value "4.7u")
      (footprint "eagle-import:C1206")
      (libsource (lib "eagle-import") (part "rcl_334_C-EUC1206"))
    )
    (comp (ref "C69")
      (value "4.7u")
      (footprint "eagle-import:C1206")
      (libsource (lib "eagle-import") (part "rcl_334_C-EUC1206"))
    )
    (comp (ref "C70")
      (value "4.7u")
      (footprint "eagle-import:C1206")
      (libsource (lib "eagle-import") (part "rcl_334_C-EUC1206"))
    )
    (comp (ref "C71")
      (value "4.7u")
      (footprint "eagle-import:C1206")
      (libsource (lib "eagle-import") (part "rcl_334_C-EUC1206"))
    )
    (comp (ref "C72")
      (value "220u")
      (footprint "eagle-import:E2,5-5")
      (libsource (lib "eagle-import") (part "CPOL-EUE2.5-5"))
    )
    (comp (ref "C80")
      (value "220u")
      (footprint "eagle-import:E2,5-5")
      (libsource (lib "eagle-import") (part "CPOL-EUE2.5-5"))
    )
    (comp (ref "C84")
      (value "4.7u")
      (footprint "eagle-import:C1206")
      (libsource (lib "eagle-import") (part "rcl_334_C-EUC1206"))
    )
    (comp (ref "C85")
      (value "4.7u")
      (footprint "eagle-import:C1206")
      (libsource (lib "eagle-import") (part "rcl_334_C-EUC1206"))
    )
    (comp (ref "C86")
      (value "4.7u")
      (footprint "eagle-import:C1206")
      (libsource (lib "eagle-import") (part "rcl_334_C-EUC1206"))
    )
    (comp (ref "C87")
      (value "4.7u")
      (footprint "eagle-import:C1206")
      (libsource (lib "eagle-import") (part "rcl_334_C-EUC1206"))
    )
    (comp (ref "CUTOFF_SWITCH")
      (value "CUTOFF SWITCH")
      (footprint "eagle-import:1X04")
      (libsource (lib "eagle-import") (part "PINHD-1X4"))
    )
    (comp (ref "D6")
      (value "6.8V")
      (footprint "eagle-import:SOD-323")
      (libsource (lib "eagle-import") (part "DIODE-ZENER-BZT52C3V6S"))
    )
    (comp (ref "EXTERNAL_INPUT")
      (value "XT60-M")
      (footprint "eagle-import:AMASS_XT60-M")
      (fields (field (name "MF") "AMASS"))
      (libsource (lib "eagle-import") (part "XT60-M"))
    )
    (comp (ref "L1")
      (value "7443641500")
      (footprint "eagle-import:74436413300")
      (fields (field (name "MOUSER_PART_NUMBER") "710-7443641500"))
      (libsource (lib "eagle-import") (part "7443641500"))
    )
    (comp (ref "LED2")
      (value "LEDSML0805")
      (footprint "eagle-import:SML0805")
      (libsource (lib "eagle-import") (part "LEDSML0805"))
    )
    (comp (ref "LED3")
      (value "LEDSML0805")
      (footprint "eagle-import:SML0805")
      (libsource (lib "eagle-import") (part "LEDSML0805"))
    )
    (comp (ref "LED4")
      (value "LEDSML0805")
      (footprint "eagle-import:SML0805")
      (libsource (lib "eagle-import") (part "LEDSML0805"))
    )
    (comp (ref "LED5")
      (value "LEDSML0805")
      (footprint "eagle-import:SML0805")
      (libsource (lib "eagle-import") (part "LEDSML0805"))
    )
    (comp (ref "LED7")
      (value "LEDSML0805")
      (footprint "eagle-import:SML0805")
      (libsource (lib "eagle-import") (part "LEDSML0805"))
    )
    (comp (ref "LED8")
      (value "LEDSML0805")
      (footprint "eagle-import:SML0805")
      (libsource (lib "eagle-import") (part "LEDSML0805"))
    )
    (comp (ref "MAIN_SWITCH")
      (value "MAIN SWITCH")
      (footprint "eagle-import:1X04")
      (libsource (lib "eagle-import") (part "PINHD-1X4"))
    )
    (comp (ref "PPTC")
      (value "MP005244 16V 12A")
      (footprint "eagle-import:FUSE_0ZCF0075AF2C")
      (fields (field (name "MF") "Bel Fuse") (field (name "MP") "0ZCF0075AF2C"))
      (libsource (lib "eagle-import") (part "0ZCF0075AF2C"))
    )
    (comp (ref "Q1")
      (value "FDD4141TO252")
      (footprint "eagle-import:TO252")
      (libsource (lib "eagle-import") (part "FDD4141TO252"))
    )
    (comp (ref "Q8")
      (value "FDD4141TO252")
      (footprint "eagle-import:TO252")
      (libsource (lib "eagle-import") (part "FDD4141TO252"))
    )
    (comp (ref "R1")
      (value "100R")
      (footprint "eagle-import:R0805")
      (libsource (lib "eagle-import") (part "rcl_334_R-EU_R0805"))
    )
    (comp (ref "R6")
      (value "1M")
      (footprint "eagle-import:R0805")
      (libsource (lib "eagle-import") (part "rcl_334_R-EU_R0805"))
    )
    (comp (ref "R7")
      (value "110k")
      (footprint "eagle-import:R0805")
      (libsource (lib "eagle-import") (part "rcl_334_R-EU_R0805"))
    )
    (comp (ref "R28")
      (value "100R")
      (footprint "eagle-import:R0603")
      (libsource (lib "eagle-import") (part "rcl_334_R-EU_R0603"))
    )
    (comp (ref "R29")
      (value "100R")
      (footprint "eagle-import:R0603")
      (libsource (lib "eagle-import") (part "rcl_334_R-EU_R0603"))
    )
    (comp (ref "R30")
      (value "100R")
      (footprint "eagle-import:R0603")
      (libsource (lib "eagle-import") (part "rcl_334_R-EU_R0603"))
    )
    (comp (ref "R31")
      (value "100R")
      (footprint "eagle-import:R0603")
      (libsource (lib "eagle-import") (part "rcl_334_R-EU_R0603"))
    )
    (comp (ref "R47")
      (value "10k")
      (footprint "eagle-import:R0805")
      (libsource (lib "eagle-import") (part "rcl_334_R-EU_R0805"))
    )
    (comp (ref "R61")
      (value "100R")
      (footprint "eagle-import:R0603")
      (libsource (lib "eagle-import") (part "rcl_334_R-EU_R0603"))
    )
    (comp (ref "R77")
      (value "5K")
      (footprint "eagle-import:R0805")
      (libsource (lib "eagle-import") (part "rcl_334_R-EU_R0805"))
    )
    (comp (ref "R78")
      (value "200R")
      (footprint "eagle-import:R0805")
      (libsource (lib "eagle-import") (part "rcl_334_R-EU_R0805"))
    )
    (comp (ref "R79")
      (value "10k")
      (footprint "eagle-import:R0805")
      (libsource (lib "eagle-import") (part "rcl_334_R-EU_R0805"))
    )
    (comp (ref "R81")
      (value "220R")
      (footprint "eagle-import:R0805")
      (libsource (lib "eagle-import") (part "rcl_334_R-EU_R0805"))
    )
    (comp (ref "R120")
      (value "200R")
      (footprint "eagle-import:R0805")
      (libsource (lib "eagle-import") (part "rcl_334_R-EU_R0805"))
    )
    (comp (ref "R121")
      (value "100R")
      (footprint "eagle-import:R0603")
      (libsource (lib "eagle-import") (part "rcl_334_R-EU_R0603"))
    )
    (comp (ref "TVS25V")
      (value "SUPRESSOR_TVS-UD-SMAJ")
      (footprint "eagle-import:SUPRESSOR_SMAJ")
      (libsource (lib "eagle-import") (part "SUPRESSOR_TVS-UD-SMAJ"))
    )
    (comp (ref "U9")
      (value "140357145000")
      (footprint "eagle-import:WL-OCPT_SOP4")
      (libsource (lib "eagle-import") (part "WL-OCPT_SERIES_357_140357145000"))
    )
    (comp (ref "U13")
      (value "140357145000")
      (footprint "eagle-import:WL-OCPT_SOP4")
      (libsource (lib "eagle-import") (part "WL-OCPT_SERIES_357_140357145000"))
    )
    (comp (ref "C6")
      (value "100nF")
      (footprint "eagle-import:C0603")
      (libsource (lib "eagle-import") (part "rcl_334_C-EUC0603"))
    )
    (comp (ref "C12")
      (value "100nF")
      (footprint "eagle-import:C0603")
      (libsource (lib "eagle-import") (part "rcl_334_C-EUC0603"))
    )
    (comp (ref "C13")
      (value "10u 6.3V")
      (footprint "eagle-import:C1206")
      (libsource (lib "eagle-import") (part "rcl_334_C-EUC1206"))
    )
    (comp (ref "C14")
      (value "100nF")
      (footprint "eagle-import:C0603")
      (libsource (lib "eagle-import") (part "rcl_334_C-EUC0603"))
    )
    (comp (ref "IC1")
      (value "PIC24FJ32GA002-X")
      (footprint "eagle-import:SPDIP28_300MC")
      (libsource (lib "eagle-import") (part "PIC24FJ32GA002-X"))
    )
    (comp (ref "LED24")
      (value "LEDSML0805")
      (footprint "eagle-import:SML0805")
      (libsource (lib "eagle-import") (part "LEDSML0805"))
    )
    (comp (ref "LED25")
      (value "LEDSML0805")
      (footprint "eagle-import:SML0805")
      (libsource (lib "eagle-import") (part "LEDSML0805"))
    )
    (comp (ref "LED26")
      (value "LEDSML0805")
      (footprint "eagle-import:SML0805")
      (libsource (lib "eagle-import") (part "LEDSML0805"))
    )
    (comp (ref "LED27")
      (value "LEDSML0805")
      (footprint "eagle-import:SML0805")
      (libsource (lib "eagle-import") (part "LEDSML0805"))
    )
    (comp (ref "MCU_1")
      (value "BM05B-PASS_STANDARD")
      (footprint "eagle-import:BM05B-PASS")
      (libsource (lib "eagle-import") (part "BM05B-PASS_STANDARD"))
    )
    (comp (ref "MCU_1_UART_RX_SWITCH")
      (value "MOTOR DRIVER UART RX SWITCH")
      (footprint "eagle-import:1X03")
      (libsource (lib "eagle-import") (part "PINHD-1X3"))
    )
    (comp (ref "MCU_1_UART_TX_SWITCH")
      (value "MOTOR DRIVER UART TX SWITCH")
      (footprint "eagle-import:1X03")
      (libsource (lib "eagle-import") (part "PINHD-1X3"))
    )
    (comp (ref "R8")
      (value "10k")
      (footprint "eagle-import:R0805")
      (libsource (lib "eagle-import") (part "rcl_334_R-EU_R0805"))
    )
    (comp (ref "R9")
      (value "1k")
      (footprint "eagle-import:R0805")
      (libsource (lib "eagle-import") (part "rcl_334_R-EU_R0805"))
    )
    (comp (ref "R94")
      (value "130R")
      (footprint "eagle-import:R0603")
      (libsource (lib "eagle-import") (part "rcl_334_R-EU_R0603"))
    )
    (comp (ref "R95")
      (value "130R")
      (footprint "eagle-import:R0603")
      (libsource (lib "eagle-import") (part "rcl_334_R-EU_R0603"))
    )
    (comp (ref "R96")
      (value "130R")
      (footprint "eagle-import:R0603")
      (libsource (lib "eagle-import") (part "rcl_334_R-EU_R0603"))
    )
    (comp (ref "R97")
      (value "130R")
      (footprint "eagle-import:R0603")
      (libsource (lib "eagle-import") (part "rcl_334_R-EU_R0603"))
    )
    (comp (ref "C19")
      (value "6.8nF 25V")
      (footprint "eagle-import:C0603")
      (libsource (lib "eagle-import") (part "rcl_334_C-EUC0603"))
    )
    (comp (ref "C20")
      (value "6.8nF 25V")
      (footprint "eagle-import:C0603")
      (libsource (lib "eagle-import") (part "rcl_334_C-EUC0603"))
    )
    (comp (ref "C24")
      (value "6.8nF 25V")
      (footprint "eagle-import:C0603")
      (libsource (lib "eagle-import") (part "rcl_334_C-EUC0603"))
    )
    (comp (ref "C25")
      (value "6.8nF 25V")
      (footprint "eagle-import:C0603")
      (libsource (lib "eagle-import") (part "rcl_334_C-EUC0603"))
    )
    (comp (ref "C26")
      (value "6.8nF 25V")
      (footprint "eagle-import:C0603")
      (libsource (lib "eagle-import") (part "rcl_334_C-EUC0603"))
    )
    (comp (ref "C27")
      (value "6.8nF 25V")
      (footprint "eagle-import:C0603")
      (libsource (lib "eagle-import") (part "rcl_334_C-EUC0603"))
    )
    (comp (ref "C28")
      (value "6.8nF 25V")
      (footprint "eagle-import:C0603")
      (libsource (lib "eagle-import") (part "rcl_334_C-EUC0603"))
    )
    (comp (ref "C29")
      (value "6.8nF 25V")
      (footprint "eagle-import:C0603")
      (libsource (lib "eagle-import") (part "rcl_334_C-EUC0603"))
    )
    (comp (ref "C30")
      (value "6.8nF 25V")
      (footprint "eagle-import:C0603")
      (libsource (lib "eagle-import") (part "rcl_334_C-EUC0603"))
    )
    (comp (ref "C31")
      (value "6.8nF 25V")
      (footprint "eagle-import:C0603")
      (libsource (lib "eagle-import") (part "rcl_334_C-EUC0603"))
    )
    (comp (ref "C32")
      (value "6.8nF 25V")
      (footprint "eagle-import:C0603")
      (libsource (lib "eagle-import") (part "rcl_334_C-EUC0603"))
    )
    (comp (ref "C33")
      (value "6.8nF 25V")
      (footprint "eagle-import:C0603")
      (libsource (lib "eagle-import") (part "rcl_334_C-EUC0603"))
    )
    (comp (ref "CURRENT_SENSOR_BATT")
      (value "TLI4971A050T5UE0001XUMA1")
      (footprint "eagle-import:IC_TLI4971A050T5UE0001XUMA1")
      (fields (field (name "MF") "Infineon Technologies"))
      (libsource (lib "eagle-import") (part "TLI4971A050T5UE0001XUMA1"))
    )
    (comp (ref "MAIN_MOTOR_CS")
      (value "TLI4971A050T5UE0001XUMA1")
      (footprint "eagle-import:IC_TLI4971A050T5UE0001XUMA1")
      (fields (field (name "MF") "Infineon Technologies"))
      (libsource (lib "eagle-import") (part "TLI4971A050T5UE0001XUMA1"))
    )
    (comp (ref "R14")
      (value "220R")
      (footprint "eagle-import:R0805")
      (libsource (lib "eagle-import") (part "rcl_334_R-EU_R0805"))
    )
    (comp (ref "R15")
      (value "220R")
      (footprint "eagle-import:R0805")
      (libsource (lib "eagle-import") (part "rcl_334_R-EU_R0805"))
    )
    (comp (ref "R16")
      (value "220R")
      (footprint "eagle-import:R0805")
      (libsource (lib "eagle-import") (part "rcl_334_R-EU_R0805"))
    )
    (comp (ref "R17")
      (value "220R")
      (footprint "eagle-import:R0805")
      (libsource (lib "eagle-import") (part "rcl_334_R-EU_R0805"))
    )
    (comp (ref "R18")
      (value "220R")
      (footprint "eagle-import:R0805")
      (libsource (lib "eagle-import") (part "rcl_334_R-EU_R0805"))
    )
    (comp (ref "R19")
      (value "220R")
      (footprint "eagle-import:R0805")
      (libsource (lib "eagle-import") (part "rcl_334_R-EU_R0805"))
    )
    (comp (ref "R20")
      (value "220R")
      (footprint "eagle-import:R0805")
      (libsource (lib "eagle-import") (part "rcl_334_R-EU_R0805"))
    )
    (comp (ref "R21")
      (value "220R")
      (footprint "eagle-import:R0805")
      (libsource (lib "eagle-import") (part "rcl_334_R-EU_R0805"))
    )
    (comp (ref "STEPPER_0_CS")
      (value "TLI4971A050T5UE0001XUMA1")
      (footprint "eagle-import:IC_TLI4971A050T5UE0001XUMA1")
      (fields (field (name "MF") "Infineon Technologies"))
      (libsource (lib "eagle-import") (part "TLI4971A050T5UE0001XUMA1"))
    )
    (comp (ref "STEPPER_1_CS")
      (value "TLI4971A050T5UE0001XUMA1")
      (footprint "eagle-import:IC_TLI4971A050T5UE0001XUMA1")
      (fields (field (name "MF") "Infineon Technologies"))
      (libsource (lib "eagle-import") (part "TLI4971A050T5UE0001XUMA1"))
    )
    (comp (ref "BATT1")
      (value "SMTU2032LF")
      (footprint "eagle-import:SMTU2032LF")
      (libsource (lib "eagle-import") (part "SMTU2032LF"))
    )
    (comp (ref "BOOT")
      (value "MOMENTARY-SWITCH-SPST-PTH-6.0MM")
      (footprint "eagle-import:TACTILE_SWITCH_PTH_6.0MM")
      (libsource (lib "eagle-import") (part "MOMENTARY-SWITCH-SPST-PTH-6.0MM"))
    )
    (comp (ref "BUTTONS")
      (value "BUTTONS")
      (footprint "eagle-import:1X10")
      (libsource (lib "eagle-import") (part "PINHD-1X10"))
    )
    (comp (ref "C1")
      (value "10n")
      (footprint "eagle-import:C0603")
      (libsource (lib "eagle-import") (part "rcl_334_C-EUC0603"))
    )
    (comp (ref "C4")
      (value "10n")
      (footprint "eagle-import:C0603")
      (libsource (lib "eagle-import") (part "rcl_334_C-EUC0603"))
    )
    (comp (ref "C67")
      (value "100n")
      (footprint "eagle-import:C0603")
      (libsource (lib "eagle-import") (part "C-EUC0603"))
    )
    (comp (ref "C73")
      (value "10n")
      (footprint "eagle-import:C0603")
      (libsource (lib "eagle-import") (part "rcl_334_C-EUC0603"))
    )
    (comp (ref "C74")
      (value "10n")
      (footprint "eagle-import:C0603")
      (libsource (lib "eagle-import") (part "rcl_334_C-EUC0603"))
    )
    (comp (ref "C75")
      (value "10n")
      (footprint "eagle-import:C0603")
      (libsource (lib "eagle-import") (part "rcl_334_C-EUC0603"))
    )
    (comp (ref "C76")
      (value "10n")
      (footprint "eagle-import:C0603")
      (libsource (lib "eagle-import") (part "rcl_334_C-EUC0603"))
    )
    (comp (ref "C77")
      (value "10n")
      (footprint "eagle-import:C0603")
      (libsource (lib "eagle-import") (part "rcl_334_C-EUC0603"))
    )
    (comp (ref "C78")
      (value "10n")
      (footprint "eagle-import:C0603")
      (libsource (lib "eagle-import") (part "rcl_334_C-EUC0603"))
    )
    (comp (ref "C81")
      (value "47u/6V3")
      (footprint "eagle-import:C1206")
      (libsource (lib "eagle-import") (part "C-EUC1206"))
    )
    (comp (ref "C82")
      (value "100n")
      (footprint "eagle-import:C0603")
      (libsource (lib "eagle-import") (part "C-EUC0603"))
    )
    (comp (ref "CAMERA")
      (value "ESP32_CAMERA")
      (footprint "eagle-import:1X04")
      (libsource (lib "eagle-import") (part "PINHD-1X4"))
    )
    (comp (ref "DISPLAY")
      (value "DISPLAY")
      (footprint "eagle-import:1X04")
      (libsource (lib "eagle-import") (part "PINHD-1X4"))
    )
    (comp (ref "EN")
      (value "MOMENTARY-SWITCH-SPST-PTH-6.0MM")
      (footprint "eagle-import:TACTILE_SWITCH_PTH_6.0MM")
      (libsource (lib "eagle-import") (part "MOMENTARY-SWITCH-SPST-PTH-6.0MM"))
    )
    (comp (ref "L3")
      (value "2112805")
      (footprint "eagle-import:L2825P")
      (libsource (lib "eagle-import") (part "L-EUL2825P"))
    )
    (comp (ref "LED1")
      (value "LEDSML0805")
      (footprint "eagle-import:SML0805")
      (libsource (lib "eagle-import") (part "LEDSML0805"))
    )
    (comp (ref "MCU_3_ESP32")
      (value "ESP-32S")
      (footprint "eagle-import:ESP-32S")
      (fields (field (name "MF") "Olimex LTD"))
      (libsource (lib "eagle-import") (part "ESP-32S"))
    )
    (comp (ref "R5")
      (value "4.7k")
      (footprint "eagle-import:R0603")
      (libsource (lib "eagle-import") (part "rcl_334_R-EU_R0603"))
    )
    (comp (ref "R26")
      (value "4.7k")
      (footprint "eagle-import:R0603")
      (libsource (lib "eagle-import") (part "rcl_334_R-EU_R0603"))
    )
    (comp (ref "R27")
      (value "1k")
      (footprint "eagle-import:R0603")
      (libsource (lib "eagle-import") (part "rcl_334_R-EU_R0603"))
    )
    (comp (ref "R73")
      (value "12k")
      (footprint "eagle-import:R0805")
      (libsource (lib "eagle-import") (part "rcl_334_R-EU_R0805"))
    )
    (comp (ref "R74")
      (value "12k")
      (footprint "eagle-import:R0805")
      (libsource (lib "eagle-import") (part "rcl_334_R-EU_R0805"))
    )
    (comp (ref "R75")
      (value "220R")
      (footprint "eagle-import:R0805")
      (libsource (lib "eagle-import") (part "rcl_334_R-EU_R0805"))
    )
    (comp (ref "R98")
      (value "10k")
      (footprint "eagle-import:R0603")
      (libsource (lib "eagle-import") (part "R-EU_R0603"))
    )
    (comp (ref "R99")
      (value "10k")
      (footprint "eagle-import:R0603")
      (libsource (lib "eagle-import") (part "R-EU_R0603"))
    )
    (comp (ref "R100")
      (value "1M")
      (footprint "eagle-import:R0603")
      (libsource (lib "eagle-import") (part "R-EU_R0603"))
    )
    (comp (ref "R101")
      (value "nc")
      (footprint "eagle-import:R0603")
      (libsource (lib "eagle-import") (part "R-EU_R0603"))
    )
    (comp (ref "R102")
      (value "nc")
      (footprint "eagle-import:R0603")
      (libsource (lib "eagle-import") (part "R-EU_R0603"))
    )
    (comp (ref "R103")
      (value "10k")
      (footprint "eagle-import:R0603")
      (libsource (lib "eagle-import") (part "R-EU_R0603"))
    )
    (comp (ref "R104")
      (value "10k")
      (footprint "eagle-import:R0603")
      (libsource (lib "eagle-import") (part "R-EU_R0603"))
    )
    (comp (ref "R105")
      (value "4.7k")
      (footprint "eagle-import:R0603")
      (libsource (lib "eagle-import") (part "R-EU_R0603"))
    )
    (comp (ref "R106")
      (value "4.7k")
      (footprint "eagle-import:R0603")
      (libsource (lib "eagle-import") (part "R-EU_R0603"))
    )
    (comp (ref "R111")
      (value "10k")
      (footprint "eagle-import:R0603")
      (libsource (lib "eagle-import") (part "rcl_334_R-EU_R0603"))
    )
    (comp (ref "R112")
      (value "10k")
      (footprint "eagle-import:R0603")
      (libsource (lib "eagle-import") (part "rcl_334_R-EU_R0603"))
    )
    (comp (ref "R113")
      (value "10k")
      (footprint "eagle-import:R0603")
      (libsource (lib "eagle-import") (part "rcl_334_R-EU_R0603"))
    )
    (comp (ref "R114")
      (value "10k")
      (footprint "eagle-import:R0603")
      (libsource (lib "eagle-import") (part "rcl_334_R-EU_R0603"))
    )
    (comp (ref "R115")
      (value "10k")
      (footprint "eagle-import:R0603")
      (libsource (lib "eagle-import") (part "rcl_334_R-EU_R0603"))
    )
    (comp (ref "R116")
      (value "10k")
      (footprint "eagle-import:R0603")
      (libsource (lib "eagle-import") (part "rcl_334_R-EU_R0603"))
    )
    (comp (ref "R117")
      (value "10k")
      (footprint "eagle-import:R0603")
      (libsource (lib "eagle-import") (part "rcl_334_R-EU_R0603"))
    )
    (comp (ref "R118")
      (value "10k")
      (footprint "eagle-import:R0603")
      (libsource (lib "eagle-import") (part "rcl_334_R-EU_R0603"))
    )
    (comp (ref "RGB_LED")
      (value "RGB_LED")
      (footprint "eagle-import:1X04")
      (libsource (lib "eagle-import") (part "PINHD-1X4"))
    )
    (comp (ref "RTCC")
      (value "AB-RTCMC-32.768KHZ-B5ZE-S3-T")
      (footprint "eagle-import:AB-RTCMC-32.768KHZ-B5ZE-S3-T")
      (libsource (lib "eagle-import") (part "AB-RTCMC-32.768KHZ-B5ZE-S3-T"))
    )
    (comp (ref "X5")
      (value "FPS009-3000")
      (footprint "eagle-import:FPS009-3000")
      (libsource (lib "eagle-import") (part "FPS009-3000"))
    )
    (comp (ref "EM_LIGHT")
      (value "EMERGENCY LIGHT")
      (footprint "eagle-import:1X02")
      (libsource (lib "eagle-import") (part "PINHD-1X2"))
    )
    (comp (ref "FAN_0")
      (value "FAN_0")
      (footprint "eagle-import:1X02")
      (libsource (lib "eagle-import") (part "PINHD-1X2"))
    )
    (comp (ref "FAN_1")
      (value "FAN_1")
      (footprint "eagle-import:1X02")
      (libsource (lib "eagle-import") (part "PINHD-1X2"))
    )
    (comp (ref "FAN_2")
      (value "FAN_2")
      (footprint "eagle-import:1X02")
      (libsource (lib "eagle-import") (part "PINHD-1X2"))
    )
    (comp (ref "FAN_3")
      (value "FAN_3")
      (footprint "eagle-import:1X02")
      (libsource (lib "eagle-import") (part "PINHD-1X2"))
    )
    (comp (ref "NMOS2")
      (value "BSC340N08NS3G")
      (footprint "eagle-import:PG-TDSON-8")
      (libsource (lib "eagle-import") (part "BSC340N08NS3G"))
    )
    (comp (ref "NMOS3")
      (value "BSC340N08NS3G")
      (footprint "eagle-import:PG-TDSON-8")
      (libsource (lib "eagle-import") (part "BSC340N08NS3G"))
    )
    (comp (ref "NMOS4")
      (value "BSC340N08NS3G")
      (footprint "eagle-import:PG-TDSON-8")
      (libsource (lib "eagle-import") (part "BSC340N08NS3G"))
    )
    (comp (ref "NMOS5")
      (value "BSC340N08NS3G")
      (footprint "eagle-import:PG-TDSON-8")
      (libsource (lib "eagle-import") (part "BSC340N08NS3G"))
    )
    (comp (ref "NMOS6")
      (value "BSC340N08NS3G")
      (footprint "eagle-import:PG-TDSON-8")
      (libsource (lib "eagle-import") (part "BSC340N08NS3G"))
    )
    (comp (ref "R22")
      (value "200R")
      (footprint "eagle-import:R0805")
      (libsource (lib "eagle-import") (part "rcl_334_R-EU_R0805"))
    )
    (comp (ref "R51")
      (value "200R")
      (footprint "eagle-import:R0805")
      (libsource (lib "eagle-import") (part "rcl_334_R-EU_R0805"))
    )
    (comp (ref "R52")
      (value "200R")
      (footprint "eagle-import:R0805")
      (libsource (lib "eagle-import") (part "rcl_334_R-EU_R0805"))
    )
    (comp (ref "R53")
      (value "200R")
      (footprint "eagle-import:R0805")
      (libsource (lib "eagle-import") (part "rcl_334_R-EU_R0805"))
    )
    (comp (ref "R63")
      (value "1k")
      (footprint "eagle-import:R0805")
      (libsource (lib "eagle-import") (part "rcl_334_R-EU_R0805"))
    )
    (comp (ref "R65")
      (value "1k")
      (footprint "eagle-import:R0805")
      (libsource (lib "eagle-import") (part "rcl_334_R-EU_R0805"))
    )
    (comp (ref "R67")
      (value "1k")
      (footprint "eagle-import:R0805")
      (libsource (lib "eagle-import") (part "rcl_334_R-EU_R0805"))
    )
    (comp (ref "R68")
      (value "1k")
      (footprint "eagle-import:R0805")
      (libsource (lib "eagle-import") (part "rcl_334_R-EU_R0805"))
    )
    (comp (ref "R76")
      (value "1k")
      (footprint "eagle-import:R0805")
      (libsource (lib "eagle-import") (part "rcl_334_R-EU_R0805"))
    )
    (comp (ref "R119")
      (value "200R")
      (footprint "eagle-import:R0805")
      (libsource (lib "eagle-import") (part "rcl_334_R-EU_R0805"))
    )
    (comp (ref "U4")
      (value "140357145000")
      (footprint "eagle-import:WL-OCPT_SOP4")
      (libsource (lib "eagle-import") (part "WL-OCPT_SERIES_357_140357145000"))
    )
    (comp (ref "U6")
      (value "140357145000")
      (footprint "eagle-import:WL-OCPT_SOP4")
      (libsource (lib "eagle-import") (part "WL-OCPT_SERIES_357_140357145000"))
    )
    (comp (ref "U7")
      (value "140357145000")
      (footprint "eagle-import:WL-OCPT_SOP4")
      (libsource (lib "eagle-import") (part "WL-OCPT_SERIES_357_140357145000"))
    )
    (comp (ref "U8")
      (value "140357145000")
      (footprint "eagle-import:WL-OCPT_SOP4")
      (libsource (lib "eagle-import") (part "WL-OCPT_SERIES_357_140357145000"))
    )
    (comp (ref "U12")
      (value "140357145000")
      (footprint "eagle-import:WL-OCPT_SOP4")
      (libsource (lib "eagle-import") (part "WL-OCPT_SERIES_357_140357145000"))
    )
    (comp (ref "C16")
      (value "100n")
      (footprint "eagle-import:C0603")
      (libsource (lib "eagle-import") (part "rcl@1_C-EUC0603"))
    )
    (comp (ref "C17")
      (value "100n")
      (footprint "eagle-import:C0603")
      (libsource (lib "eagle-import") (part "rcl@1_C-EUC0603"))
    )
    (comp (ref "C37")
      (value "1u")
      (footprint "eagle-import:C0603")
      (libsource (lib "eagle-import") (part "rcl@1_C-EUC0603"))
    )
    (comp (ref "C38")
      (value "100n")
      (footprint "eagle-import:C0603")
      (libsource (lib "eagle-import") (part "rcl@1_C-EUC0603"))
    )
    (comp (ref "C39")
      (value "100n")
      (footprint "eagle-import:C0603")
      (libsource (lib "eagle-import") (part "rcl@1_C-EUC0603"))
    )
    (comp (ref "C40")
      (value "4.7u")
      (footprint "eagle-import:C0603")
      (libsource (lib "eagle-import") (part "rcl@1_C-EUC0603"))
    )
    (comp (ref "C44")
      (value "10nF")
      (footprint "eagle-import:C0603")
      (libsource (lib "eagle-import") (part "rcl_334_C-EUC0603"))
    )
    (comp (ref "C45")
      (value "100nF")
      (footprint "eagle-import:C0603")
      (libsource (lib "eagle-import") (part "rcl_334_C-EUC0603"))
    )
    (comp (ref "C46")
      (value "2.2nF 50V")
      (footprint "eagle-import:C0603")
      (libsource (lib "eagle-import") (part "rcl_334_C-EUC0603"))
    )
    (comp (ref "C47")
      (value "100nF")
      (footprint "eagle-import:C0603")
      (libsource (lib "eagle-import") (part "rcl_334_C-EUC0603"))
    )
    (comp (ref "C83")
      (value "1u")
      (footprint "eagle-import:C0603")
      (libsource (lib "eagle-import") (part "rcl@1_C-EUC0603"))
    )
    (comp (ref "CP2102")
      (value "CP2101")
      (footprint "eagle-import:MLP28")
      (fields (field (name "MF") "FARNELL") (field (name "MPN") "CP2102-GM"))
      (libsource (lib "eagle-import") (part "CP2101"))
    )
    (comp (ref "D3")
      (value "BAT60J")
      (footprint "eagle-import:SOD323_ST")
      (libsource (lib "eagle-import") (part "BAT60J"))
    )
    (comp (ref "D4")
      (value "BAT60J")
      (footprint "eagle-import:SOD323_ST")
      (libsource (lib "eagle-import") (part "BAT60J"))
    )
    (comp (ref "D5")
      (value "BAT60J")
      (footprint "eagle-import:SOD323_ST")
      (libsource (lib "eagle-import") (part "BAT60J"))
    )
    (comp (ref "MICROUSB")
      (value "MICROUSB")
      (footprint "eagle-import:MOLEX_47642-0001")
      (fields (field (name "MF") "Molex") (field (name "MP") "47642-0001"))
      (libsource (lib "eagle-import") (part "MICROUSB"))
    )
    (comp (ref "R36")
      (value "4.7k")
      (footprint "eagle-import:R0603")
      (libsource (lib "eagle-import") (part "rcl_334_R-EU_R0603"))
    )
    (comp (ref "R37")
      (value "4.7k")
      (footprint "eagle-import:R0603")
      (libsource (lib "eagle-import") (part "rcl_334_R-EU_R0603"))
    )
    (comp (ref "R49")
      (value "10k")
      (footprint "eagle-import:R0603")
      (libsource (lib "eagle-import") (part "rcl@1_R-EU_R0603"))
    )
    (comp (ref "R50")
      (value "4.7k")
      (footprint "eagle-import:R0603")
      (libsource (lib "eagle-import") (part "rcl@1_R-EU_R0603"))
    )
    (comp (ref "U2")
      (value "LIS3MDLTR")
      (footprint "eagle-import:XDCR_LIS3MDLTR")
      (fields (field (name "MF") "STMicroelectronics"))
      (libsource (lib "eagle-import") (part "LIS3MDLTR"))
    )
    (comp (ref "U5")
      (value "MPU-6050")
      (footprint "eagle-import:24-VFQFN")
      (fields
        (field (name "DIGIKEY_PART_NUMBER") "1428-1007-1-ND")
        (field (name "MANUFACTURER") "TDK InvenSense")
        (field (name "CREATED_BY") "PCBLayout.com")
      )
      (libsource (lib "eagle-import") (part "MPU-6050"))
    )
    (comp (ref "C63")
      (value "1u")
      (footprint "eagle-import:C0603")
      (libsource (lib "eagle-import") (part "rcl@1_C-EUC0603"))
    )
    (comp (ref "C64")
      (value "1u")
      (footprint "eagle-import:C0603")
      (libsource (lib "eagle-import") (part "rcl@1_C-EUC0603"))
    )
    (comp (ref "C65")
      (value "1u")
      (footprint "eagle-import:C0603")
      (libsource (lib "eagle-import") (part "rcl@1_C-EUC0603"))
    )
    (comp (ref "C66")
      (value "1u")
      (footprint "eagle-import:C0603")
      (libsource (lib "eagle-import") (part "rcl@1_C-EUC0603"))
    )
    (comp (ref "D2")
      (value "3V3")
      (footprint "eagle-import:SOD80C")
      (libsource (lib "eagle-import") (part "ZENER-DIODESOD80C"))
    )
    (comp (ref "GPS")
      (value "GPS MODULE")
      (footprint "eagle-import:1X05")
      (libsource (lib "eagle-import") (part "PINHD-1X5"))
    )
    (comp (ref "LIDAR")
      (value "LIDAR")
      (footprint "eagle-import:1X08")
      (libsource (lib "eagle-import") (part "PINHD-1X8"))
    )
    (comp (ref "LIGHT_SENSOR")
      (value "PHOTORESISTOR LDR5549")
      (footprint "eagle-import:1X02")
      (libsource (lib "eagle-import") (part "PINHD-1X2"))
    )
    (comp (ref "LIMIT_SWITCH_DOWN")
      (value "LIMIT_SWITCH_BOTTOM_MAGNETIC")
      (footprint "eagle-import:1X03")
      (libsource (lib "eagle-import") (part "PINHD-1X3"))
    )
    (comp (ref "LIMIT_SWITCH_UP")
      (value "LIMIT_SWITCH_UPPER_MAGNETIC")
      (footprint "eagle-import:1X03")
      (libsource (lib "eagle-import") (part "PINHD-1X3"))
    )
    (comp (ref "MAIN_MOTOR")
      (value "MAIN MOTOR")
      (footprint "eagle-import:1X04")
      (libsource (lib "eagle-import") (part "PINHD-1X4"))
    )
    (comp (ref "MCU_2_I2C_EXTENDER")
      (value "MCU_2_I2C_EXTENDER")
      (footprint "eagle-import:1X04")
      (libsource (lib "eagle-import") (part "PINHD-1X4"))
    )
    (comp (ref "NAVIGATION_UART")
      (value "TELEMETRY_UART")
      (footprint "eagle-import:1X02")
      (libsource (lib "eagle-import") (part "PINHD-1X2"))
    )
    (comp (ref "NMOS1")
      (value "BSC340N08NS3G")
      (footprint "eagle-import:PG-TDSON-8")
      (libsource (lib "eagle-import") (part "BSC340N08NS3G"))
    )
    (comp (ref "PERIMETER_WIRE")
      (value "PER.WIRE SENSE")
      (footprint "eagle-import:1X04")
      (libsource (lib "eagle-import") (part "PINHD-1X4"))
    )
    (comp (ref "R4")
      (value "1k")
      (footprint "eagle-import:R0805")
      (libsource (lib "eagle-import") (part "rcl_334_R-EU_R0805"))
    )
    (comp (ref "R54")
      (value "1k")
      (footprint "eagle-import:R0805")
      (libsource (lib "eagle-import") (part "rcl_334_R-EU_R0805"))
    )
    (comp (ref "R55")
      (value "500k")
      (footprint "eagle-import:R0805")
      (libsource (lib "eagle-import") (part "rcl_334_R-EU_R0805"))
    )
    (comp (ref "R57")
      (value "10R")
      (footprint "eagle-import:R0805")
      (libsource (lib "eagle-import") (part "rcl_334_R-EU_R0805"))
    )
    (comp (ref "R62")
      (value "200R")
      (footprint "eagle-import:R0805")
      (libsource (lib "eagle-import") (part "rcl_334_R-EU_R0805"))
    )
    (comp (ref "R64")
      (value "500k")
      (footprint "eagle-import:R0805")
      (libsource (lib "eagle-import") (part "rcl_334_R-EU_R0805"))
    )
    (comp (ref "R66")
      (value "10R")
      (footprint "eagle-import:R0805")
      (libsource (lib "eagle-import") (part "rcl_334_R-EU_R0805"))
    )
    (comp (ref "R69")
      (value "5k")
      (footprint "eagle-import:R0805")
      (libsource (lib "eagle-import") (part "rcl_334_R-EU_R0805"))
    )
    (comp (ref "R70")
      (value "5k")
      (footprint "eagle-import:R0603")
      (libsource (lib "eagle-import") (part "rcl_334_R-EU_R0603"))
    )
    (comp (ref "R71")
      (value "5k")
      (footprint "eagle-import:R0805")
      (libsource (lib "eagle-import") (part "rcl_334_R-EU_R0805"))
    )
    (comp (ref "R72")
      (value "5k")
      (footprint "eagle-import:R0805")
      (libsource (lib "eagle-import") (part "rcl_334_R-EU_R0805"))
    )
    (comp (ref "R107")
      (value "10k")
      (footprint "eagle-import:R0805")
      (libsource (lib "eagle-import") (part "rcl_334_R-EU_R0805"))
    )
    (comp (ref "R108")
      (value "10k")
      (footprint "eagle-import:R0805")
      (libsource (lib "eagle-import") (part "rcl_334_R-EU_R0805"))
    )
    (comp (ref "R109")
      (value "10k")
      (footprint "eagle-import:R0805")
      (libsource (lib "eagle-import") (part "rcl_334_R-EU_R0805"))
    )
    (comp (ref "R110")
      (value "10k")
      (footprint "eagle-import:R0805")
      (libsource (lib "eagle-import") (part "rcl_334_R-EU_R0805"))
    )
    (comp (ref "RAIN_SENSOR")
      (value "RAIN SENSOR")
      (footprint "eagle-import:1X02")
      (libsource (lib "eagle-import") (part "PINHD-1X2"))
    )
    (comp (ref "STEPPER_0")
      (value "STEPPER_0")
      (footprint "eagle-import:1X04")
      (libsource (lib "eagle-import") (part "PINHD-1X4"))
    )
    (comp (ref "STEPPER_1")
      (value "STEPPER_1")
      (footprint "eagle-import:1X04")
      (libsource (lib "eagle-import") (part "PINHD-1X4"))
    )
    (comp (ref "STEPPER_2")
      (value "STEPPER_2")
      (footprint "eagle-import:1X04")
      (libsource (lib "eagle-import") (part "PINHD-1X4"))
    )
    (comp (ref "TEMP_SENSOR_0")
      (value "TEMP SENSOR 0")
      (footprint "eagle-import:1X03")
      (libsource (lib "eagle-import") (part "PINHD-1X3"))
    )
    (comp (ref "TEMP_SENSOR_1")
      (value "TEMP SENSOR 1")
      (footprint "eagle-import:1X03")
      (libsource (lib "eagle-import") (part "PINHD-1X3"))
    )
    (comp (ref "TEMP_SENSOR_2")
      (value "TEMP SENSOR 2")
      (footprint "eagle-import:1X03")
      (libsource (lib "eagle-import") (part "PINHD-1X3"))
    )
    (comp (ref "TEMP_SENSOR_3")
      (value "TEMP SENSOR 3")
      (footprint "eagle-import:1X03")
      (libsource (lib "eagle-import") (part "PINHD-1X3"))
    )
    (comp (ref "U10")
      (value "140357145000")
      (footprint "eagle-import:WL-OCPT_SOP4")
      (libsource (lib "eagle-import") (part "WL-OCPT_SERIES_357_140357145000"))
    )
    (comp (ref "UNLIMITED_POWER")
      (value "V_OUTPUT")
      (footprint "eagle-import:1X05")
      (libsource (lib "eagle-import") (part "PINHD-1X5"))
    )
  )
  (nets
    (net (code "1") (name "3V3") (class "Default")
      (node (ref "3V3_REG0") (pin "3") (pinfunction "+VOUT_3") (pintype "output"))
      (node (ref "3V3_REG1") (pin "3") (pinfunction "+VOUT_3") (pintype "output"))
      (node (ref "3V3_REG2") (pin "3") (pinfunction "+VOUT_3") (pintype "output"))
      (node (ref "3V3_REG3") (pin "3") (pinfunction "+VOUT_3") (pintype "output"))
      (node (ref "C10") (pin "1") (pinfunction "1_1") (pintype "passive"))
      (node (ref "C12") (pin "2") (pinfunction "2_2") (pintype "passive"))
      (node (ref "C14") (pin "1") (pinfunction "1_1") (pintype "passive"))
      (node (ref "C17") (pin "1") (pinfunction "1_1") (pintype "passive"))
      (node (ref "C18") (pin "1") (pinfunction "1_1") (pintype "passive"))
      (node (ref "C20") (pin "2") (pinfunction "2_2") (pintype "passive"))
      (node (ref "C21") (pin "1") (pinfunction "1_1") (pintype "passive"))
      (node (ref "C22") (pin "1") (pinfunction "1_1") (pintype "passive"))
      (node (ref "C23") (pin "1") (pinfunction "1_1") (pintype "passive"))
      (node (ref "C26") (pin "2") (pinfunction "2_2") (pintype "passive"))
      (node (ref "C29") (pin "2") (pinfunction "2_2") (pintype "passive"))
      (node (ref "C32") (pin "2") (pinfunction "2_2") (pintype "passive"))
      (node (ref "C39") (pin "1") (pinfunction "1_1") (pintype "passive"))
      (node (ref "C40") (pin "1") (pinfunction "1_1") (pintype "passive"))
      (node (ref "C44") (pin "1") (pinfunction "1_1") (pintype "passive"))
      (node (ref "C45") (pin "1") (pinfunction "1_1") (pintype "passive"))
      (node (ref "C49") (pin "1") (pinfunction "1_1") (pintype "passive"))
      (node (ref "C5") (pin "1") (pinfunction "1_1") (pintype "passive"))
      (node (ref "C63") (pin "2") (pinfunction "2_2") (pintype "passive"))
      (node (ref "C64") (pin "2") (pinfunction "2_2") (pintype "passive"))
      (node (ref "C65") (pin "2") (pinfunction "2_2") (pintype "passive"))
      (node (ref "C66") (pin "2") (pinfunction "2_2") (pintype "passive"))
      (node (ref "C67") (pin "2") (pinfunction "2_2") (pintype "passive"))
      (node (ref "C68") (pin "1") (pinfunction "1_1") (pintype "passive"))
      (node (ref "C70") (pin "1") (pinfunction "1_1") (pintype "passive"))
      (node (ref "C8") (pin "2") (pinfunction "2_2") (pintype "passive"))
      (node (ref "C82") (pin "1") (pinfunction "1_1") (pintype "passive"))
      (node (ref "C83") (pin "1") (pinfunction "1_1") (pintype "passive"))
      (node (ref "C9") (pin "2") (pinfunction "2_2") (pintype "passive"))
      (node (ref "CAMERA") (pin "3") (pinfunction "3_3") (pintype "passive"))
      (node (ref "CP2102") (pin "6") (pinfunction "VDD_6") (pintype "power_in"))
      (node (ref "CURRENT_SENSOR_BATT") (pin "1") (pinfunction "VDD_1") (pintype "power_in"))
      (node (ref "GPS") (pin "1") (pinfunction "1_1") (pintype "passive"))
      (node (ref "IC1") (pin "13") (pinfunction "VDD_2_13") (pintype "passive"))
      (node (ref "IC1") (pin "28") (pinfunction "VDD_28") (pintype "passive"))
      (node (ref "L3") (pin "2") (pinfunction "2_2") (pintype "passive"))
      (node (ref "LIMIT_SWITCH_DOWN") (pin "1") (pinfunction "1_1") (pintype "passive"))
      (node (ref "LIMIT_SWITCH_UP") (pin "1") (pinfunction "1_1") (pintype "passive"))
      (node (ref "MAIN_MOTOR_CS") (pin "1") (pinfunction "VDD_1") (pintype "power_in"))
      (node (ref "MCU_0") (pin "P$5") (pinfunction "5_P$5") (pintype "bidirectional"))
      (node (ref "MCU_1") (pin "P$5") (pinfunction "5_P$5") (pintype "bidirectional"))
      (node (ref "MCU_2") (pin "P$5") (pinfunction "5_P$5") (pintype "bidirectional"))
      (node (ref "MCU_2_I2C_EXTENDER") (pin "3") (pinfunction "3_3") (pintype "passive"))
      (node (ref "MCU_3_ESP32") (pin "2") (pinfunction "3V3_2") (pintype "power_in"))
      (node (ref "R10") (pin "2") (pinfunction "2_2") (pintype "passive"))
      (node (ref "R101") (pin "1") (pinfunction "1_1") (pintype "passive"))
      (node (ref "R102") (pin "1") (pinfunction "1_1") (pintype "passive"))
      (node (ref "R103") (pin "2") (pinfunction "2_2") (pintype "passive"))
      (node (ref "R104") (pin "2") (pinfunction "2_2") (pintype "passive"))
      (node (ref "R105") (pin "2") (pinfunction "2_2") (pintype "passive"))
      (node (ref "R106") (pin "2") (pinfunction "2_2") (pintype "passive"))
      (node (ref "R12") (pin "2") (pinfunction "2_2") (pintype "passive"))
      (node (ref "R14") (pin "1") (pinfunction "1_1") (pintype "passive"))
      (node (ref "R16") (pin "1") (pinfunction "1_1") (pintype "passive"))
      (node (ref "R18") (pin "1") (pinfunction "1_1") (pintype "passive"))
      (node (ref "R20") (pin "1") (pinfunction "1_1") (pintype "passive"))
      (node (ref "R26") (pin "1") (pinfunction "1_1") (pintype "passive"))
      (node (ref "R27") (pin "1") (pinfunction "1_1") (pintype "passive"))
      (node (ref "R28") (pin "1") (pinfunction "1_1") (pintype "passive"))
      (node (ref "R29") (pin "1") (pinfunction "1_1") (pintype "passive"))
      (node (ref "R30") (pin "1") (pinfunction "1_1") (pintype "passive"))
      (node (ref "R31") (pin "1") (pinfunction "1_1") (pintype "passive"))
      (node (ref "R34") (pin "1") (pinfunction "1_1") (pintype "passive"))
      (node (ref "R36") (pin "1") (pinfunction "1_1") (pintype "passive"))
      (node (ref "R37") (pin "1") (pinfunction "1_1") (pintype "passive"))
      (node (ref "R40") (pin "1") (pinfunction "1_1") (pintype "passive"))
      (node (ref "R45") (pin "1") (pinfunction "1_1") (pintype "passive"))
      (node (ref "R47") (pin "1") (pinfunction "1_1") (pintype "passive"))
      (node (ref "R5") (pin "1") (pinfunction "1_1") (pintype "passive"))
      (node (ref "R50") (pin "2") (pinfunction "2_2") (pintype "passive"))
      (node (ref "R55") (pin "1") (pinfunction "1_1") (pintype "passive"))
      (node (ref "R64") (pin "1") (pinfunction "1_1") (pintype "passive"))
      (node (ref "R69") (pin "2") (pinfunction "2_2") (pintype "passive"))
      (node (ref "R70") (pin "2") (pinfunction "2_2") (pintype "passive"))
      (node (ref "R71") (pin "2") (pinfunction "2_2") (pintype "passive"))
      (node (ref "R72") (pin "2") (pinfunction "2_2") (pintype "passive"))
      (node (ref "R73") (pin "1") (pinfunction "1_1") (pintype "passive"))
      (node (ref "R74") (pin "2") (pinfunction "2_2") (pintype "passive"))
      (node (ref "R8") (pin "2") (pinfunction "2_2") (pintype "passive"))
      (node (ref "R90") (pin "2") (pinfunction "2_2") (pintype "passive"))
      (node (ref "R98") (pin "2") (pinfunction "2_2") (pintype "passive"))
      (node (ref "R99") (pin "2") (pinfunction "2_2") (pintype "passive"))
      (node (ref "RTCC") (pin "1") (pinfunction "VDD_1") (pintype "bidirectional"))
      (node (ref "STEPPER_0_CS") (pin "1") (pinfunction "VDD_1") (pintype "power_in"))
      (node (ref "STEPPER_1_CS") (pin "1") (pinfunction "VDD_1") (pintype "power_in"))
      (node (ref "TEMP_SENSOR_0") (pin "1") (pinfunction "1_1") (pintype "passive"))
      (node (ref "TEMP_SENSOR_1") (pin "1") (pinfunction "1_1") (pintype "passive"))
      (node (ref "TEMP_SENSOR_2") (pin "1") (pinfunction "1_1") (pintype "passive"))
      (node (ref "TEMP_SENSOR_3") (pin "1") (pinfunction "1_1") (pintype "passive"))
      (node (ref "TP3") (pin "TP") (pinfunction "TP_TP") (pintype "input"))
      (node (ref "U1") (pin "28") (pinfunction "VDD2_28") (pintype "power_in"))
      (node (ref "U1") (pin "7") (pinfunction "VDD1_7") (pintype "power_in"))
      (node (ref "U15") (pin "10") (pinfunction "VDD_2_10") (pintype "power_in"))
      (node (ref "U15") (pin "19") (pinfunction "AVDD_19") (pintype "power_in"))
      (node (ref "U15") (pin "26") (pinfunction "VDD_3_26") (pintype "power_in"))
      (node (ref "U15") (pin "35") (pinfunction "VUSB3V3_35") (pintype "power_in"))
      (node (ref "U15") (pin "38") (pinfunction "VDD_4_38") (pintype "power_in"))
      (node (ref "U15") (pin "57") (pinfunction "VDD_57") (pintype "power_in"))
      (node (ref "U2") (pin "5") (pinfunction "VDD_5") (pintype "power_in"))
      (node (ref "U2") (pin "6") (pinfunction "VDD_IO_6") (pintype "power_in"))
      (node (ref "U5") (pin "13") (pinfunction "VDD_13") (pintype "power_in"))
      (node (ref "U5") (pin "8") (pinfunction "VLOGIC_8") (pintype "power_in"))
      (node (ref "UNLIMITED_POWER") (pin "1") (pinfunction "1_1") (pintype "passive"))
    )
    (net (code "2") (name "5V") (class "Default")
      (node (ref "5V_REG0") (pin "3") (pinfunction "+VOUT_3") (pintype "output"))
      (node (ref "5V_REG1") (pin "3") (pinfunction "+VOUT_3") (pintype "output"))
      (node (ref "BUZZER") (pin "+") (pinfunction "1_+") (pintype "passive"))
      (node (ref "C84") (pin "1") (pinfunction "1_1") (pintype "passive"))
      (node (ref "C86") (pin "1") (pinfunction "1_1") (pintype "passive"))
      (node (ref "DISPLAY") (pin "3") (pinfunction "3_3") (pintype "passive"))
      (node (ref "LIDAR") (pin "2") (pinfunction "2_2") (pintype "passive"))
      (node (ref "PERIMETER_WIRE") (pin "1") (pinfunction "1_1") (pintype "passive"))
      (node (ref "R121") (pin "1") (pinfunction "1_1") (pintype "passive"))
      (node (ref "R61") (pin "1") (pinfunction "1_1") (pintype "passive"))
      (node (ref "TP2") (pin "TP") (pinfunction "TP_TP") (pintype "input"))
      (node (ref "U10") (pin "4") (pinfunction "4_4") (pintype "passive"))
      (node (ref "UNLIMITED_POWER") (pin "2") (pinfunction "2_2") (pintype "passive"))
    )
    (net (code "3") (name "12V_STEPPER_0_POS") (class "Default")
      (node (ref "C36") (pin "1") (pinfunction "1_1") (pintype "passive"))
      (node (ref "C41") (pin "1") (pinfunction "1_1") (pintype "passive"))
      (node (ref "C42") (pin "1") (pinfunction "1_1") (pintype "passive"))
      (node (ref "C43") (pin "1") (pinfunction "1_1") (pintype "passive"))
      (node (ref "SD1") (pin "10") (pinfunction "VIN_10") (pintype "bidirectional"))
      (node (ref "SD1") (pin "22") (pinfunction "VIN2_22") (pintype "bidirectional"))
      (node (ref "STEPPER_0_CS") (pin "7") (pinfunction "IP-_7") (pintype "input"))
    )
    (net (code "4") (name "12V_STEPPER_1_POS") (class "Default")
      (node (ref "C53") (pin "1") (pinfunction "1_1") (pintype "passive"))
      (node (ref "C54") (pin "1") (pinfunction "1_1") (pintype "passive"))
      (node (ref "C55") (pin "1") (pinfunction "1_1") (pintype "passive"))
      (node (ref "C56") (pin "1") (pinfunction "1_1") (pintype "passive"))
      (node (ref "SD2") (pin "10") (pinfunction "VIN_10") (pintype "bidirectional"))
      (node (ref "SD2") (pin "22") (pinfunction "VIN2_22") (pintype "bidirectional"))
      (node (ref "STEPPER_1_CS") (pin "7") (pinfunction "IP-_7") (pintype "input"))
    )
    (net (code "5") (name "BATT_ADC") (class "Default")
      (node (ref "R6") (pin "1") (pinfunction "1_1") (pintype "passive"))
      (node (ref "R7") (pin "2") (pinfunction "2_2") (pintype "passive"))
      (node (ref "U1") (pin "21") (pinfunction "RA2/AN2/C2INB/C1IND/C3INB/VREF-/CVREF_21") (pintype "bidirectional"))
    )
    (net (code "6") (name "BATT_DIRECT_POS_POLE") (class "Default")
      (node (ref "BATT") (pin "TP") (pinfunction "TP_TP") (pintype "input"))
      (node (ref "BATTERY_INPUT") (pin "2") (pinfunction "+_2") (pintype "passive"))
      (node (ref "MAIN_SWITCH") (pin "1") (pinfunction "1_1") (pintype "passive"))
      (node (ref "MAIN_SWITCH") (pin "2") (pinfunction "2_2") (pintype "passive"))
    )
    (net (code "7") (name "BATT_POS") (class "Default")
      (node (ref "3V3_REG0") (pin "1") (pinfunction "+VIN_1") (pintype "input"))
      (node (ref "3V3_REG1") (pin "1") (pinfunction "+VIN_1") (pintype "input"))
      (node (ref "3V3_REG2") (pin "1") (pinfunction "+VIN_1") (pintype "input"))
      (node (ref "3V3_REG3") (pin "1") (pinfunction "+VIN_1") (pintype "input"))
      (node (ref "5V_REG0") (pin "1") (pinfunction "+VIN_1") (pintype "input"))
      (node (ref "5V_REG1") (pin "1") (pinfunction "+VIN_1") (pintype "input"))
      (node (ref "BATT_POS") (pin "TP") (pinfunction "TP_TP") (pintype "input"))
      (node (ref "C48") (pin "1") (pinfunction "1_1") (pintype "passive"))
      (node (ref "C50") (pin "1") (pinfunction "1_1") (pintype "passive"))
      (node (ref "C59") (pin "1") (pinfunction "1_1") (pintype "passive"))
      (node (ref "C60") (pin "1") (pinfunction "1_1") (pintype "passive"))
      (node (ref "C61") (pin "1") (pinfunction "1_1") (pintype "passive"))
      (node (ref "C62") (pin "1") (pinfunction "1_1") (pintype "passive"))
      (node (ref "C69") (pin "1") (pinfunction "1_1") (pintype "passive"))
      (node (ref "C71") (pin "1") (pinfunction "1_1") (pintype "passive"))
      (node (ref "C85") (pin "1") (pinfunction "1_1") (pintype "passive"))
      (node (ref "C87") (pin "1") (pinfunction "1_1") (pintype "passive"))
      (node (ref "CURRENT_SENSOR_BATT") (pin "7") (pinfunction "IP-_7") (pintype "input"))
      (node (ref "EM_LIGHT") (pin "1") (pinfunction "1_1") (pintype "passive"))
      (node (ref "FAN_0") (pin "1") (pinfunction "1_1") (pintype "passive"))
      (node (ref "FAN_1") (pin "1") (pinfunction "1_1") (pintype "passive"))
      (node (ref "FAN_2") (pin "1") (pinfunction "1_1") (pintype "passive"))
      (node (ref "FAN_3") (pin "1") (pinfunction "1_1") (pintype "passive"))
      (node (ref "MAIN_MOTOR_CS") (pin "8") (pinfunction "IP+_8") (pintype "input"))
      (node (ref "SD3") (pin "10") (pinfunction "VIN_10") (pintype "bidirectional"))
      (node (ref "SD3") (pin "22") (pinfunction "VIN2_22") (pintype "bidirectional"))
      (node (ref "STEPPER_0_CS") (pin "8") (pinfunction "IP+_8") (pintype "input"))
      (node (ref "STEPPER_1_CS") (pin "8") (pinfunction "IP+_8") (pintype "input"))
      (node (ref "U12") (pin "4") (pinfunction "4_4") (pintype "passive"))
      (node (ref "U4") (pin "4") (pinfunction "4_4") (pintype "passive"))
      (node (ref "U6") (pin "4") (pinfunction "4_4") (pintype "passive"))
      (node (ref "U7") (pin "4") (pinfunction "4_4") (pintype "passive"))
      (node (ref "U8") (pin "4") (pinfunction "4_4") (pintype "passive"))
      (node (ref "UNLIMITED_POWER") (pin "3") (pinfunction "3_3") (pintype "passive"))
    )
    (net (code "8") (name "BATT_POS_POLE") (class "Default")
      (node (ref "CUTOFF_SWITCH") (pin "3") (pinfunction "3_3") (pintype "passive"))
      (node (ref "CUTOFF_SWITCH") (pin "4") (pinfunction "4_4") (pintype "passive"))
      (node (ref "PPTC") (pin "2") (pinfunction "2_2") (pintype "passive"))
      (node (ref "Q8") (pin "3") (pinfunction "D_3") (pintype "passive"))
    )
    (net (code "9") (name "BATT_POS_POLE_SWITCH") (class "Default")
      (node (ref "CUTOFF_SWITCH") (pin "1") (pinfunction "1_1") (pintype "passive"))
      (node (ref "CUTOFF_SWITCH") (pin "2") (pinfunction "2_2") (pintype "passive"))
      (node (ref "MAIN_SWITCH") (pin "3") (pinfunction "3_3") (pintype "passive"))
      (node (ref "MAIN_SWITCH") (pin "4") (pinfunction "4_4") (pintype "passive"))
    )
    (net (code "10") (name "BLADE_MOTOR_NEG_EXT") (class "Default")
      (node (ref "D11") (pin "C") (pinfunction "C_C") (pintype "passive"))
      (node (ref "D9") (pin "A") (pinfunction "A_A") (pintype "passive"))
      (node (ref "MAIN_MOTOR") (pin "3") (pinfunction "3_3") (pintype "passive"))
      (node (ref "MAIN_MOTOR") (pin "4") (pinfunction "4_4") (pintype "passive"))
      (node (ref "NMOS7") (pin "5") (pinfunction "D_5") (pintype "passive"))
      (node (ref "NMOS7") (pin "6") (pinfunction "D_6") (pintype "passive"))
      (node (ref "NMOS7") (pin "7") (pinfunction "D_7") (pintype "passive"))
      (node (ref "NMOS7") (pin "8") (pinfunction "D_8") (pintype "passive"))
      (node (ref "NMOS7") (pin "TH") (pinfunction "TH_TH") (pintype "passive"))
    )
    (net (code "11") (name "BLADE_MOTOR_POS") (class "Default")
      (node (ref "D10") (pin "A") (pinfunction "A_A") (pintype "passive"))
      (node (ref "MAIN_MOTOR_CS") (pin "7") (pinfunction "IP-_7") (pintype "input"))
      (node (ref "U11") (pin "4") (pinfunction "4_4") (pintype "passive"))
    )
    (net (code "12") (name "BLADE_MOTOR_POS_EXT") (class "Default")
      (node (ref "D10") (pin "C") (pinfunction "C_C") (pintype "passive"))
      (node (ref "D9") (pin "C") (pinfunction "C_C") (pintype "passive"))
      (node (ref "MAIN_MOTOR") (pin "1") (pinfunction "1_1") (pintype "passive"))
      (node (ref "MAIN_MOTOR") (pin "2") (pinfunction "2_2") (pintype "passive"))
    )
    (net (code "13") (name "CP2102_RXD") (class "Default")
      (node (ref "CP2102") (pin "25") (pinfunction "RXD_25") (pintype "input"))
      (node (ref "CP2102_RX") (pin "TP") (pinfunction "TP_TP") (pintype "input"))
      (node (ref "MCU_3_ESP32") (pin "35") (pinfunction "U0TXD_35") (pintype "bidirectional"))
    )
    (net (code "14") (name "CP2102_TXD") (class "Default")
      (node (ref "CP2102") (pin "26") (pinfunction "TXD_26") (pintype "output"))
      (node (ref "CP2102_TX") (pin "TP") (pinfunction "TP_TP") (pintype "input"))
      (node (ref "MCU_3_ESP32") (pin "34") (pinfunction "U0RXD_34") (pintype "bidirectional"))
    )
    (net (code "15") (name "CP_RST") (class "Default")
      (node (ref "CP2102") (pin "9") (pinfunction "~{RST}_9") (pintype "bidirectional"))
      (node (ref "R50") (pin "1") (pinfunction "1_1") (pintype "passive"))
    )
    (net (code "16") (name "CP_SUSPEND") (class "Default")
      (node (ref "CP2102") (pin "12") (pinfunction "SUSPEND_12") (pintype "output"))
    )
    (net (code "17") (name "CURRENT_SENSOR_3_POS") (class "Default")
      (node (ref "C2") (pin "+") (pinfunction "+_+") (pintype "passive"))
      (node (ref "C3") (pin "+") (pinfunction "+_+") (pintype "passive"))
      (node (ref "C72") (pin "+") (pinfunction "+_+") (pintype "passive"))
      (node (ref "CURRENT_SENSOR_BATT") (pin "8") (pinfunction "IP+_8") (pintype "input"))
      (node (ref "L1") (pin "1") (pinfunction "1_1") (pintype "bidirectional"))
      (node (ref "R6") (pin "2") (pinfunction "2_2") (pintype "passive"))
    )
    (net (code "18") (name "D_N") (class "Default")
      (node (ref "CP2102") (pin "5") (pinfunction "D-_5") (pintype "bidirectional"))
      (node (ref "D5") (pin "C") (pinfunction "C_C") (pintype "passive"))
      (node (ref "MICROUSB") (pin "2") (pinfunction "D-_2") (pintype "bidirectional"))
    )
    (net (code "19") (name "D_P") (class "Default")
      (node (ref "CP2102") (pin "4") (pinfunction "D+_4") (pintype "bidirectional"))
      (node (ref "D4") (pin "C") (pinfunction "C_C") (pintype "passive"))
      (node (ref "MICROUSB") (pin "3") (pinfunction "D+_3") (pintype "bidirectional"))
    )
    (net (code "20") (name "EP") (class "Default")
      (node (ref "U5") (pin "25") (pinfunction "EP_25") (pintype "power_in"))
    )
    (net (code "21") (name "EXTERNAL_GND") (class "Default")
      (node (ref "EXTERNAL_INPUT") (pin "1") (pinfunction "-_1") (pintype "passive"))
      (node (ref "U13") (pin "2") (pinfunction "2_2") (pintype "passive"))
      (node (ref "U9") (pin "3") (pinfunction "3_3") (pintype "passive"))
    )
    (net (code "22") (name "EXTERNAL_INPUT_SENSE") (class "Default")
      (node (ref "R79") (pin "1") (pinfunction "1_1") (pintype "passive"))
      (node (ref "U1") (pin "15") (pinfunction "RB5/CCP5/PMA0/KBI1/RP8_15") (pintype "bidirectional"))
      (node (ref "U13") (pin "3") (pinfunction "3_3") (pintype "passive"))
    )
    (net (code "23") (name "EXTERNAL_POS") (class "Default")
      (node (ref "EXTERNAL_INPUT") (pin "2") (pinfunction "+_2") (pintype "passive"))
      (node (ref "Q8") (pin "2") (pinfunction "S_2") (pintype "passive"))
      (node (ref "R77") (pin "1") (pinfunction "1_1") (pintype "passive"))
      (node (ref "R78") (pin "2") (pinfunction "2_2") (pintype "passive"))
    )
    (net (code "24") (name "GND") (class "Default")
      (node (ref "3V3_REG0") (pin "2") (pinfunction "GND_2") (pintype "power_in"))
      (node (ref "3V3_REG1") (pin "2") (pinfunction "GND_2") (pintype "power_in"))
      (node (ref "3V3_REG2") (pin "2") (pinfunction "GND_2") (pintype "power_in"))
      (node (ref "3V3_REG3") (pin "2") (pinfunction "GND_2") (pintype "power_in"))
      (node (ref "5V_REG0") (pin "2") (pinfunction "GND_2") (pintype "power_in"))
      (node (ref "5V_REG1") (pin "2") (pinfunction "GND_2") (pintype "power_in"))
      (node (ref "BATT1") (pin "MINUS") (pinfunction "MINUS_MINUS") (pintype "bidirectional"))
      (node (ref "BATTERY_INPUT") (pin "1") (pinfunction "-_1") (pintype "passive"))
      (node (ref "BOOT") (pin "3") (pinfunction "2_3") (pintype "passive"))
      (node (ref "BUTTONS") (pin "10") (pinfunction "10_10") (pintype "passive"))
      (node (ref "C1") (pin "2") (pinfunction "2_2") (pintype "passive"))
      (node (ref "C10") (pin "2") (pinfunction "2_2") (pintype "passive"))
      (node (ref "C11") (pin "2") (pinfunction "2_2") (pintype "passive"))
      (node (ref "C12") (pin "1") (pinfunction "1_1") (pintype "passive"))
      (node (ref "C13") (pin "2") (pinfunction "2_2") (pintype "passive"))
      (node (ref "C14") (pin "2") (pinfunction "2_2") (pintype "passive"))
      (node (ref "C15") (pin "2") (pinfunction "2_2") (pintype "passive"))
      (node (ref "C16") (pin "2") (pinfunction "2_2") (pintype "passive"))
      (node (ref "C17") (pin "2") (pinfunction "2_2") (pintype "passive"))
      (node (ref "C18") (pin "2") (pinfunction "2_2") (pintype "passive"))
      (node (ref "C19") (pin "2") (pinfunction "2_2") (pintype "passive"))
      (node (ref "C2") (pin "-") (pinfunction "-_-") (pintype "passive"))
      (node (ref "C20") (pin "1") (pinfunction "1_1") (pintype "passive"))
      (node (ref "C21") (pin "2") (pinfunction "2_2") (pintype "passive"))
      (node (ref "C22") (pin "2") (pinfunction "2_2") (pintype "passive"))
      (node (ref "C23") (pin "2") (pinfunction "2_2") (pintype "passive"))
      (node (ref "C24") (pin "2") (pinfunction "2_2") (pintype "passive"))
      (node (ref "C25") (pin "2") (pinfunction "2_2") (pintype "passive"))
      (node (ref "C26") (pin "1") (pinfunction "1_1") (pintype "passive"))
      (node (ref "C27") (pin "2") (pinfunction "2_2") (pintype "passive"))
      (node (ref "C28") (pin "2") (pinfunction "2_2") (pintype "passive"))
      (node (ref "C29") (pin "1") (pinfunction "1_1") (pintype "passive"))
      (node (ref "C3") (pin "-") (pinfunction "-_-") (pintype "passive"))
      (node (ref "C30") (pin "2") (pinfunction "2_2") (pintype "passive"))
      (node (ref "C31") (pin "2") (pinfunction "2_2") (pintype "passive"))
      (node (ref "C32") (pin "1") (pinfunction "1_1") (pintype "passive"))
      (node (ref "C33") (pin "2") (pinfunction "2_2") (pintype "passive"))
      (node (ref "C34") (pin "2") (pinfunction "2_2") (pintype "passive"))
      (node (ref "C37") (pin "1") (pinfunction "1_1") (pintype "passive"))
      (node (ref "C38") (pin "1") (pinfunction "1_1") (pintype "passive"))
      (node (ref "C39") (pin "2") (pinfunction "2_2") (pintype "passive"))
      (node (ref "C4") (pin "2") (pinfunction "2_2") (pintype "passive"))
      (node (ref "C40") (pin "2") (pinfunction "2_2") (pintype "passive"))
      (node (ref "C41") (pin "2") (pinfunction "2_2") (pintype "passive"))
      (node (ref "C42") (pin "2") (pinfunction "2_2") (pintype "passive"))
      (node (ref "C43") (pin "2") (pinfunction "2_2") (pintype "passive"))
      (node (ref "C44") (pin "2") (pinfunction "2_2") (pintype "passive"))
      (node (ref "C45") (pin "2") (pinfunction "2_2") (pintype "passive"))
      (node (ref "C46") (pin "1") (pinfunction "1_1") (pintype "passive"))
      (node (ref "C47") (pin "2") (pinfunction "2_2") (pintype "passive"))
      (node (ref "C48") (pin "2") (pinfunction "2_2") (pintype "passive"))
      (node (ref "C49") (pin "2") (pinfunction "2_2") (pintype "passive"))
      (node (ref "C5") (pin "2") (pinfunction "2_2") (pintype "passive"))
      (node (ref "C50") (pin "2") (pinfunction "2_2") (pintype "passive"))
      (node (ref "C51") (pin "2") (pinfunction "2_2") (pintype "passive"))
      (node (ref "C54") (pin "2") (pinfunction "2_2") (pintype "passive"))
      (node (ref "C55") (pin "2") (pinfunction "2_2") (pintype "passive"))
      (node (ref "C56") (pin "2") (pinfunction "2_2") (pintype "passive"))
      (node (ref "C57") (pin "2") (pinfunction "2_2") (pintype "passive"))
      (node (ref "C6") (pin "2") (pinfunction "2_2") (pintype "passive"))
      (node (ref "C60") (pin "2") (pinfunction "2_2") (pintype "passive"))
      (node (ref "C61") (pin "2") (pinfunction "2_2") (pintype "passive"))
      (node (ref "C62") (pin "2") (pinfunction "2_2") (pintype "passive"))
      (node (ref "C63") (pin "1") (pinfunction "1_1") (pintype "passive"))
      (node (ref "C64") (pin "1") (pinfunction "1_1") (pintype "passive"))
      (node (ref "C65") (pin "1") (pinfunction "1_1") (pintype "passive"))
      (node (ref "C66") (pin "1") (pinfunction "1_1") (pintype "passive"))
      (node (ref "C67") (pin "1") (pinfunction "1_1") (pintype "passive"))
      (node (ref "C68") (pin "2") (pinfunction "2_2") (pintype "passive"))
      (node (ref "C69") (pin "2") (pinfunction "2_2") (pintype "passive"))
      (node (ref "C7") (pin "2") (pinfunction "2_2") (pintype "passive"))
      (node (ref "C70") (pin "2") (pinfunction "2_2") (pintype "passive"))
      (node (ref "C71") (pin "2") (pinfunction "2_2") (pintype "passive"))
      (node (ref "C72") (pin "-") (pinfunction "-_-") (pintype "passive"))
      (node (ref "C73") (pin "2") (pinfunction "2_2") (pintype "passive"))
      (node (ref "C74") (pin "2") (pinfunction "2_2") (pintype "passive"))
      (node (ref "C75") (pin "2") (pinfunction "2_2") (pintype "passive"))
      (node (ref "C76") (pin "2") (pinfunction "2_2") (pintype "passive"))
      (node (ref "C77") (pin "2") (pinfunction "2_2") (pintype "passive"))
      (node (ref "C78") (pin "2") (pinfunction "2_2") (pintype "passive"))
      (node (ref "C79") (pin "2") (pinfunction "2_2") (pintype "passive"))
      (node (ref "C8") (pin "1") (pinfunction "1_1") (pintype "passive"))
      (node (ref "C80") (pin "-") (pinfunction "-_-") (pintype "passive"))
      (node (ref "C81") (pin "2") (pinfunction "2_2") (pintype "passive"))
      (node (ref "C82") (pin "2") (pinfunction "2_2") (pintype "passive"))
      (node (ref "C83") (pin "2") (pinfunction "2_2") (pintype "passive"))
      (node (ref "C84") (pin "2") (pinfunction "2_2") (pintype "passive"))
      (node (ref "C85") (pin "2") (pinfunction "2_2") (pintype "passive"))
      (node (ref "C86") (pin "2") (pinfunction "2_2") (pintype "passive"))
      (node (ref "C87") (pin "2") (pinfunction "2_2") (pintype "passive"))
      (node (ref "C9") (pin "1") (pinfunction "1_1") (pintype "passive"))
      (node (ref "CAMERA") (pin "4") (pinfunction "4_4") (pintype "passive"))
      (node (ref "CP2102") (pin "1") (pinfunction "DCD_1") (pintype "input"))
      (node (ref "CP2102") (pin "2") (pinfunction "RI_2") (pintype "input"))
      (node (ref "CP2102") (pin "23") (pinfunction "CTS_23") (pintype "input"))
      (node (ref "CP2102") (pin "27") (pinfunction "DSR_27") (pintype "input"))
      (node (ref "CP2102") (pin "3") (pinfunction "GND_3") (pintype "power_in"))
      (node (ref "CP2102") (pin "EXP") (pinfunction "GND_EXP") (pintype "power_in"))
      (node (ref "CP2102") (pin "M") (pinfunction "GND_M") (pintype "power_in"))
      (node (ref "CURRENT_SENSOR_BATT") (pin "2") (pinfunction "GND_2") (pintype "power_in"))
      (node (ref "D11") (pin "A") (pinfunction "A_A") (pintype "passive"))
      (node (ref "D2") (pin "A") (pinfunction "A_A") (pintype "passive"))
      (node (ref "D3") (pin "A") (pinfunction "A_A") (pintype "passive"))
      (node (ref "D4") (pin "A") (pinfunction "A_A") (pintype "passive"))
      (node (ref "D5") (pin "A") (pinfunction "A_A") (pintype "passive"))
      (node (ref "DISPLAY") (pin "4") (pinfunction "4_4") (pintype "passive"))
      (node (ref "EN") (pin "3") (pinfunction "2_3") (pintype "passive"))
      (node (ref "GPS") (pin "2") (pinfunction "2_2") (pintype "passive"))
      (node (ref "IC1") (pin "27") (pinfunction "VSS_27") (pintype "passive"))
      (node (ref "IC1") (pin "8") (pinfunction "VSS_2_8") (pintype "passive"))
      (node (ref "L1") (pin "3") (pinfunction "3_3") (pintype "bidirectional"))
      (node (ref "LED1") (pin "C") (pinfunction "C_C") (pintype "passive"))
      (node (ref "LED12") (pin "C") (pinfunction "C_C") (pintype "passive"))
      (node (ref "LED13") (pin "C") (pinfunction "C_C") (pintype "passive"))
      (node (ref "LED14") (pin "C") (pinfunction "C_C") (pintype "passive"))
      (node (ref "LED15") (pin "C") (pinfunction "C_C") (pintype "passive"))
      (node (ref "LED16") (pin "C") (pinfunction "C_C") (pintype "passive"))
      (node (ref "LED17") (pin "C") (pinfunction "C_C") (pintype "passive"))
      (node (ref "LED18") (pin "C") (pinfunction "C_C") (pintype "passive"))
      (node (ref "LED19") (pin "C") (pinfunction "C_C") (pintype "passive"))
      (node (ref "LED2") (pin "C") (pinfunction "C_C") (pintype "passive"))
      (node (ref "LED20") (pin "C") (pinfunction "C_C") (pintype "passive"))
      (node (ref "LED21") (pin "C") (pinfunction "C_C") (pintype "passive"))
      (node (ref "LED22") (pin "C") (pinfunction "C_C") (pintype "passive"))
      (node (ref "LED23") (pin "C") (pinfunction "C_C") (pintype "passive"))
      (node (ref "LED24") (pin "C") (pinfunction "C_C") (pintype "passive"))
      (node (ref "LED25") (pin "C") (pinfunction "C_C") (pintype "passive"))
      (node (ref "LED26") (pin "C") (pinfunction "C_C") (pintype "passive"))
      (node (ref "LED27") (pin "C") (pinfunction "C_C") (pintype "passive"))
      (node (ref "LED3") (pin "C") (pinfunction "C_C") (pintype "passive"))
      (node (ref "LED4") (pin "C") (pinfunction "C_C") (pintype "passive"))
      (node (ref "LED5") (pin "C") (pinfunction "C_C") (pintype "passive"))
      (node (ref "LED7") (pin "C") (pinfunction "C_C") (pintype "passive"))
      (node (ref "LED8") (pin "C") (pinfunction "C_C") (pintype "passive"))
      (node (ref "LIDAR") (pin "1") (pinfunction "1_1") (pintype "passive"))
      (node (ref "LIGHT_SENSOR") (pin "2") (pinfunction "2_2") (pintype "passive"))
      (node (ref "LIMIT_SWITCH_DOWN") (pin "3") (pinfunction "3_3") (pintype "passive"))
      (node (ref "LIMIT_SWITCH_UP") (pin "3") (pinfunction "3_3") (pintype "passive"))
      (node (ref "MAIN_MOTOR_CS") (pin "2") (pinfunction "GND_2") (pintype "power_in"))
      (node (ref "MCU_0") (pin "P$1") (pinfunction "1_P$1") (pintype "bidirectional"))
      (node (ref "MCU_1") (pin "P$1") (pinfunction "1_P$1") (pintype "bidirectional"))
      (node (ref "MCU_2") (pin "P$1") (pinfunction "1_P$1") (pintype "bidirectional"))
      (node (ref "MCU_2_I2C_EXTENDER") (pin "4") (pinfunction "4_4") (pintype "passive"))
      (node (ref "MCU_3_ESP32") (pin "1") (pinfunction "GND_1") (pintype "power_in"))
      (node (ref "MCU_3_ESP32") (pin "15") (pinfunction "GND_15") (pintype "power_in"))
      (node (ref "MCU_3_ESP32") (pin "38") (pinfunction "GND_38") (pintype "power_in"))
      (node (ref "MCU_3_ESP32") (pin "GND") (pinfunction "GND_GND") (pintype "power_in"))
      (node (ref "MICROUSB") (pin "4") (pinfunction "ID_4") (pintype "bidirectional"))
      (node (ref "MICROUSB") (pin "5") (pinfunction "GND_5") (pintype "power_in"))
      (node (ref "MICROUSB") (pin "S1") (pinfunction "SHIELD_S1") (pintype "power_in"))
      (node (ref "MICROUSB") (pin "S2") (pinfunction "SHIELD_S2") (pintype "power_in"))
      (node (ref "MICROUSB") (pin "S3") (pinfunction "SHIELD_S3") (pintype "power_in"))
      (node (ref "MICROUSB") (pin "S4") (pinfunction "SHIELD_S4") (pintype "power_in"))
      (node (ref "NMOS1") (pin "1") (pinfunction "S_1") (pintype "passive"))
      (node (ref "NMOS1") (pin "2") (pinfunction "S_2") (pintype "passive"))
      (node (ref "NMOS1") (pin "3") (pinfunction "S_3") (pintype "passive"))
      (node (ref "NMOS2") (pin "1") (pinfunction "S_1") (pintype "passive"))
      (node (ref "NMOS2") (pin "2") (pinfunction "S_2") (pintype "passive"))
      (node (ref "NMOS2") (pin "3") (pinfunction "S_3") (pintype "passive"))
      (node (ref "NMOS3") (pin "1") (pinfunction "S_1") (pintype "passive"))
      (node (ref "NMOS3") (pin "2") (pinfunction "S_2") (pintype "passive"))
      (node (ref "NMOS3") (pin "3") (pinfunction "S_3") (pintype "passive"))
      (node (ref "NMOS4") (pin "1") (pinfunction "S_1") (pintype "passive"))
      (node (ref "NMOS4") (pin "2") (pinfunction "S_2") (pintype "passive"))
      (node (ref "NMOS4") (pin "3") (pinfunction "S_3") (pintype "passive"))
      (node (ref "NMOS5") (pin "1") (pinfunction "S_1") (pintype "passive"))
      (node (ref "NMOS5") (pin "2") (pinfunction "S_2") (pintype "passive"))
      (node (ref "NMOS5") (pin "3") (pinfunction "S_3") (pintype "passive"))
      (node (ref "NMOS6") (pin "1") (pinfunction "S_1") (pintype "passive"))
      (node (ref "NMOS6") (pin "2") (pinfunction "S_2") (pintype "passive"))
      (node (ref "NMOS6") (pin "3") (pinfunction "S_3") (pintype "passive"))
      (node (ref "NMOS7") (pin "1") (pinfunction "S_1") (pintype "passive"))
      (node (ref "NMOS7") (pin "2") (pinfunction "S_2") (pintype "passive"))
      (node (ref "NMOS7") (pin "3") (pinfunction "S_3") (pintype "passive"))
      (node (ref "PERIMETER_WIRE") (pin "3") (pinfunction "3_3") (pintype "passive"))
      (node (ref "PERIMETER_WIRE") (pin "4") (pinfunction "4_4") (pintype "passive"))
      (node (ref "R1") (pin "1") (pinfunction "1_1") (pintype "passive"))
      (node (ref "R100") (pin "2") (pinfunction "2_2") (pintype "passive"))
      (node (ref "R109") (pin "1") (pinfunction "1_1") (pintype "passive"))
      (node (ref "R110") (pin "1") (pinfunction "1_1") (pintype "passive"))
      (node (ref "R111") (pin "2") (pinfunction "2_2") (pintype "passive"))
      (node (ref "R112") (pin "2") (pinfunction "2_2") (pintype "passive"))
      (node (ref "R113") (pin "2") (pinfunction "2_2") (pintype "passive"))
      (node (ref "R114") (pin "2") (pinfunction "2_2") (pintype "passive"))
      (node (ref "R115") (pin "2") (pinfunction "2_2") (pintype "passive"))
      (node (ref "R116") (pin "2") (pinfunction "2_2") (pintype "passive"))
      (node (ref "R117") (pin "2") (pinfunction "2_2") (pintype "passive"))
      (node (ref "R118") (pin "2") (pinfunction "2_2") (pintype "passive"))
      (node (ref "R2") (pin "1") (pinfunction "1_1") (pintype "passive"))
      (node (ref "R23") (pin "2") (pinfunction "2_2") (pintype "passive"))
      (node (ref "R3") (pin "1") (pinfunction "1_1") (pintype "passive"))
      (node (ref "R35") (pin "2") (pinfunction "2_2") (pintype "passive"))
      (node (ref "R41") (pin "2") (pinfunction "2_2") (pintype "passive"))
      (node (ref "R42") (pin "1") (pinfunction "1_1") (pintype "passive"))
      (node (ref "R46") (pin "2") (pinfunction "2_2") (pintype "passive"))
      (node (ref "R49") (pin "1") (pinfunction "1_1") (pintype "passive"))
      (node (ref "R54") (pin "2") (pinfunction "2_2") (pintype "passive"))
      (node (ref "R63") (pin "2") (pinfunction "2_2") (pintype "passive"))
      (node (ref "R65") (pin "2") (pinfunction "2_2") (pintype "passive"))
      (node (ref "R67") (pin "2") (pinfunction "2_2") (pintype "passive"))
      (node (ref "R68") (pin "2") (pinfunction "2_2") (pintype "passive"))
      (node (ref "R7") (pin "1") (pinfunction "1_1") (pintype "passive"))
      (node (ref "R76") (pin "2") (pinfunction "2_2") (pintype "passive"))
      (node (ref "R79") (pin "2") (pinfunction "2_2") (pintype "passive"))
      (node (ref "RAIN_SENSOR") (pin "2") (pinfunction "2_2") (pintype "passive"))
      (node (ref "RGB_LED") (pin "4") (pinfunction "4_4") (pintype "passive"))
      (node (ref "RTCC") (pin "7") (pinfunction "VSS_7") (pintype "bidirectional"))
      (node (ref "SD1") (pin "12") (pinfunction "GND2_12") (pintype "bidirectional"))
      (node (ref "SD1") (pin "20") (pinfunction "GND3_20") (pintype "bidirectional"))
      (node (ref "SD1") (pin "24") (pinfunction "GND4_24") (pintype "bidirectional"))
      (node (ref "SD1") (pin "25") (pinfunction "PAD_25") (pintype "bidirectional"))
      (node (ref "SD1") (pin "4") (pinfunction "AGND_4") (pintype "bidirectional"))
      (node (ref "SD1") (pin "8") (pinfunction "GND_8") (pintype "bidirectional"))
      (node (ref "SD2") (pin "12") (pinfunction "GND2_12") (pintype "bidirectional"))
      (node (ref "SD2") (pin "20") (pinfunction "GND3_20") (pintype "bidirectional"))
      (node (ref "SD2") (pin "24") (pinfunction "GND4_24") (pintype "bidirectional"))
      (node (ref "SD2") (pin "25") (pinfunction "PAD_25") (pintype "bidirectional"))
      (node (ref "SD2") (pin "4") (pinfunction "AGND_4") (pintype "bidirectional"))
      (node (ref "SD2") (pin "8") (pinfunction "GND_8") (pintype "bidirectional"))
      (node (ref "SD3") (pin "12") (pinfunction "GND2_12") (pintype "bidirectional"))
      (node (ref "SD3") (pin "20") (pinfunction "GND3_20") (pintype "bidirectional"))
      (node (ref "SD3") (pin "24") (pinfunction "GND4_24") (pintype "bidirectional"))
      (node (ref "SD3") (pin "25") (pinfunction "PAD_25") (pintype "bidirectional"))
      (node (ref "SD3") (pin "4") (pinfunction "AGND_4") (pintype "bidirectional"))
      (node (ref "SD3") (pin "8") (pinfunction "GND_8") (pintype "bidirectional"))
      (node (ref "STEPPER_0_CS") (pin "2") (pinfunction "GND_2") (pintype "power_in"))
      (node (ref "STEPPER_1_CS") (pin "2") (pinfunction "GND_2") (pintype "power_in"))
      (node (ref "T2") (pin "E") (pinfunction "E_E") (pintype "passive"))
      (node (ref "TEMP_SENSOR_0") (pin "3") (pinfunction "3_3") (pintype "passive"))
      (node (ref "TEMP_SENSOR_1") (pin "3") (pinfunction "3_3") (pintype "passive"))
      (node (ref "TEMP_SENSOR_2") (pin "3") (pinfunction "3_3") (pintype "passive"))
      (node (ref "TEMP_SENSOR_3") (pin "3") (pinfunction "3_3") (pintype "passive"))
      (node (ref "TILT_SENSOR") (pin "1") (pinfunction "1_1") (pintype "passive"))
      (node (ref "TVS25V") (pin "A") (pinfunction "A_A") (pintype "passive"))
      (node (ref "U1") (pin "29") (pinfunction "VSS2_29") (pintype "power_in"))
      (node (ref "U1") (pin "6") (pinfunction "VSS1_6") (pintype "power_in"))
      (node (ref "U10") (pin "2") (pinfunction "2_2") (pintype "passive"))
      (node (ref "U11") (pin "2") (pinfunction "2_2") (pintype "passive"))
      (node (ref "U12") (pin "2") (pinfunction "2_2") (pintype "passive"))
      (node (ref "U15") (pin "20") (pinfunction "AVSS_20") (pintype "passive"))
      (node (ref "U15") (pin "25") (pinfunction "VSS_3_25") (pintype "passive"))
      (node (ref "U15") (pin "41") (pinfunction "VSS_4_41") (pintype "passive"))
      (node (ref "U15") (pin "56") (pinfunction "VSS_56") (pintype "passive"))
      (node (ref "U15") (pin "9") (pinfunction "VSS_2_9") (pintype "passive"))
      (node (ref "U2") (pin "12") (pinfunction "RSVD2_12") (pintype "passive"))
      (node (ref "U2") (pin "2") (pinfunction "RSVD1_2") (pintype "passive"))
      (node (ref "U2") (pin "3") (pinfunction "GND_3") (pintype "power_in"))
      (node (ref "U4") (pin "2") (pinfunction "2_2") (pintype "passive"))
      (node (ref "U5") (pin "1") (pinfunction "CLKIN_1") (pintype "input"))
      (node (ref "U5") (pin "11") (pinfunction "FSYNC_11") (pintype "input"))
      (node (ref "U5") (pin "18") (pinfunction "GND_18") (pintype "power_in"))
      (node (ref "U5") (pin "9") (pinfunction "AD0_9") (pintype "bidirectional"))
      (node (ref "U6") (pin "2") (pinfunction "2_2") (pintype "passive"))
      (node (ref "U7") (pin "2") (pinfunction "2_2") (pintype "passive"))
      (node (ref "U8") (pin "2") (pinfunction "2_2") (pintype "passive"))
      (node (ref "U9") (pin "2") (pinfunction "2_2") (pintype "passive"))
      (node (ref "UNLIMITED_POWER") (pin "4") (pinfunction "4_4") (pintype "passive"))
      (node (ref "UNLIMITED_POWER") (pin "5") (pinfunction "5_5") (pintype "passive"))
      (node (ref "X5") (pin "3") (pinfunction "3_3") (pintype "input"))
      (node (ref "X5") (pin "6") (pinfunction "6_6") (pintype "input"))
      (node (ref "X5") (pin "COM_TERM") (pinfunction "COM_TERM_COM_TERM") (pintype "input"))
    )
    (net (code "25") (name "GPS_PPS") (class "Default")
      (node (ref "GPS") (pin "5") (pinfunction "5_5") (pintype "passive"))
    )
    (net (code "26") (name "GPS_RXD") (class "Default")
      (node (ref "GPS") (pin "4") (pinfunction "4_4") (pintype "passive"))
      (node (ref "GPS_RX") (pin "TP") (pinfunction "TP_TP") (pintype "input"))
      (node (ref "U15") (pin "22") (pinfunction "OA3IN-/AN7/CVD7/C3IN1-/C4IN1-/RPC1/PMA7/RC1_22") (pintype "bidirectional"))
    )
    (net (code "27") (name "GPS_TXD") (class "Default")
      (node (ref "GPS") (pin "3") (pinfunction "3_3") (pintype "passive"))
      (node (ref "GPS_TX") (pin "TP") (pinfunction "TP_TP") (pintype "input"))
      (node (ref "U15") (pin "21") (pinfunction "OA3OUT/AN6/CVD6/C3IN4-/C4IN1+/C4IN4-/RPC0/RC0_21") (pintype "bidirectional"))
    )
    (net (code "28") (name "LIDAR_RX") (class "Default")
      (node (ref "LIDAR") (pin "4") (pinfunction "4_4") (pintype "passive"))
      (node (ref "LIDAR_RX") (pin "TP") (pinfunction "TP_TP") (pintype "input"))
      (node (ref "U15") (pin "60") (pinfunction "RPB10/PWM3H/PMD0/RB10_60") (pintype "bidirectional"))
    )
    (net (code "29") (name "LIDAR_TX") (class "Default")
      (node (ref "LIDAR") (pin "7") (pinfunction "7_7") (pintype "passive"))
      (node (ref "LIDAR_TX") (pin "TP") (pinfunction "TP_TP") (pintype "input"))
      (node (ref "U15") (pin "43") (pinfunction "PGD2/RPB5/SDA3/USBID1/RB5_43") (pintype "bidirectional"))
    )
    (net (code "30") (name "LIMIT_SWITCH_BOTTOM") (class "Default")
      (node (ref "IC1") (pin "23") (pinfunction "AN12/RP12/CN14/PMD0/RB12_23") (pintype "passive"))
      (node (ref "R108") (pin "1") (pinfunction "1_1") (pintype "passive"))
    )
    (net (code "31") (name "LIMIT_SWITCH_UPPER") (class "Default")
      (node (ref "IC1") (pin "24") (pinfunction "AN11/RP13/CN13/PMRD/RB13_24") (pintype "passive"))
      (node (ref "R107") (pin "1") (pinfunction "1_1") (pintype "passive"))
    )
    (net (code "32") (name "LIS3MDLTR_ENABLE") (class "Default")
      (node (ref "U2") (pin "10") (pinfunction "CS_10") (pintype "input"))
    )
    (net (code "33") (name "LIS3MDLTR_SA1") (class "Default")
      (node (ref "U2") (pin "9") (pinfunction "SDO/SA1_9") (pintype "bidirectional"))
    )
    (net (code "34") (name "MCU_0_BUZZER") (class "Default")
      (node (ref "R24") (pin "1") (pinfunction "1_1") (pintype "passive"))
      (node (ref "U1") (pin "35") (pinfunction "RC1/CCP8/T1OSI/RP12_35") (pintype "bidirectional"))
    )
    (net (code "35") (name "MCU_0_CHARGING_INPUT_ENABLE") (class "Default")
      (node (ref "R120") (pin "1") (pinfunction "1_1") (pintype "passive"))
      (node (ref "R85") (pin "1") (pinfunction "1_1") (pintype "passive"))
      (node (ref "U1") (pin "41") (pinfunction "RD3/PMD3/RP20_41") (pintype "bidirectional"))
    )
    (net (code "36") (name "MCU_0_CURRENT_SENSOR_0") (class "Default")
      (node (ref "CS_STEP0") (pin "TP") (pinfunction "TP_TP") (pintype "input"))
      (node (ref "R15") (pin "2") (pinfunction "2_2") (pintype "passive"))
      (node (ref "U1") (pin "19") (pinfunction "RA0/AN0/C1INA/ULPWU/PMA6/RP0_19") (pintype "bidirectional"))
    )
    (net (code "37") (name "MCU_0_CURRENT_SENSOR_1") (class "Default")
      (node (ref "CS_STEP1") (pin "TP") (pinfunction "TP_TP") (pintype "input"))
      (node (ref "R17") (pin "2") (pinfunction "2_2") (pintype "passive"))
      (node (ref "U1") (pin "20") (pinfunction "RA1/AN1/C2INA/VBG/CTDIN/PMA7/RP1_20") (pintype "bidirectional"))
    )
    (net (code "38") (name "MCU_0_CURRENT_SENSOR_2") (class "Default")
      (node (ref "CS_MAIN_MOT") (pin "TP") (pinfunction "TP_TP") (pintype "input"))
      (node (ref "R19") (pin "2") (pinfunction "2_2") (pintype "passive"))
      (node (ref "U1") (pin "25") (pinfunction "RE0/AN5/PMRD_25") (pintype "bidirectional"))
    )
    (net (code "39") (name "MCU_0_CURRENT_SENSOR_3") (class "Default")
      (node (ref "CS_BATT") (pin "TP") (pinfunction "TP_TP") (pintype "input"))
      (node (ref "R21") (pin "2") (pinfunction "2_2") (pintype "passive"))
      (node (ref "U1") (pin "26") (pinfunction "RE1/AN6/PMWR_26") (pintype "bidirectional"))
    )
    (net (code "40") (name "MCU_0_EMERGENCY_LIGHT") (class "Default")
      (node (ref "R119") (pin "1") (pinfunction "1_1") (pintype "passive"))
      (node (ref "U1") (pin "32") (pinfunction "RC0/T1OSO/T1CKI/RP11_32") (pintype "bidirectional"))
    )
    (net (code "41") (name "MCU_0_FAN_0") (class "Default")
      (node (ref "R22") (pin "1") (pinfunction "1_1") (pintype "passive"))
      (node (ref "R86") (pin "1") (pinfunction "1_1") (pintype "passive"))
      (node (ref "U1") (pin "2") (pinfunction "RD4/PMD4/RP21_2") (pintype "bidirectional"))
    )
    (net (code "42") (name "MCU_0_FAN_1") (class "Default")
      (node (ref "R51") (pin "1") (pinfunction "1_1") (pintype "passive"))
      (node (ref "R87") (pin "1") (pinfunction "1_1") (pintype "passive"))
      (node (ref "U1") (pin "3") (pinfunction "RD5/PMD5/RP22_3") (pintype "bidirectional"))
    )
    (net (code "43") (name "MCU_0_FAN_2") (class "Default")
      (node (ref "R53") (pin "1") (pinfunction "1_1") (pintype "passive"))
      (node (ref "R88") (pin "1") (pinfunction "1_1") (pintype "passive"))
      (node (ref "U1") (pin "4") (pinfunction "RD6/PMD6/RP23_4") (pintype "bidirectional"))
    )
    (net (code "44") (name "MCU_0_FAN_3") (class "Default")
      (node (ref "R52") (pin "1") (pinfunction "1_1") (pintype "passive"))
      (node (ref "R89") (pin "1") (pinfunction "1_1") (pintype "passive"))
      (node (ref "U1") (pin "5") (pinfunction "RD7/PMD7/RP24_5") (pintype "bidirectional"))
    )
    (net (code "45") (name "MCU_0_LED0") (class "Default")
      (node (ref "R82") (pin "1") (pinfunction "1_1") (pintype "passive"))
      (node (ref "U1") (pin "38") (pinfunction "RD0/PMD0/SCL2_38") (pintype "bidirectional"))
    )
    (net (code "46") (name "MCU_0_LED1") (class "Default")
      (node (ref "R83") (pin "1") (pinfunction "1_1") (pintype "passive"))
      (node (ref "U1") (pin "39") (pinfunction "RD1/PMD1/SDA2_39") (pintype "bidirectional"))
    )
    (net (code "47") (name "MCU_0_LED2") (class "Default")
      (node (ref "R80") (pin "1") (pinfunction "1_1") (pintype "passive"))
      (node (ref "U1") (pin "40") (pinfunction "RD2/PMD2/RP1_40") (pintype "bidirectional"))
    )
    (net (code "48") (name "MCU_0_LIGHT_SENSOR") (class "Default")
      (node (ref "R66") (pin "1") (pinfunction "1_1") (pintype "passive"))
      (node (ref "U1") (pin "24") (pinfunction "RA5/AN4/C1INC/SS1~{/HLVDIN/RP2}_24") (pintype "bidirectional"))
    )
    (net (code "49") (name "MCU_0_MCLR") (class "Default")
      (node (ref "MCU_0") (pin "P$4") (pinfunction "4_P$4") (pintype "bidirectional"))
      (node (ref "R11") (pin "1") (pinfunction "1_1") (pintype "passive"))
      (node (ref "U1") (pin "18") (pinfunction "~_18") (pintype "input"))
    )
    (net (code "50") (name "MCU_0_PGC") (class "Default")
      (node (ref "MCU_0") (pin "P$3") (pinfunction "3_P$3") (pintype "bidirectional"))
      (node (ref "U1") (pin "16") (pinfunction "RB6/CCP6/KBI2/PGC/RP9_16") (pintype "bidirectional"))
    )
    (net (code "51") (name "MCU_0_PGD") (class "Default")
      (node (ref "MCU_0") (pin "P$2") (pinfunction "2_P$2") (pintype "bidirectional"))
      (node (ref "U1") (pin "17") (pinfunction "RB7/CCP7/KBI3/PGD/RP10_17") (pintype "bidirectional"))
    )
    (net (code "52") (name "MCU_0_RAIN_SENSOR") (class "Default")
      (node (ref "R57") (pin "1") (pinfunction "1_1") (pintype "passive"))
      (node (ref "U1") (pin "27") (pinfunction "RE2/AN7/PMCS_27") (pintype "bidirectional"))
    )
    (net (code "53") (name "MCU_0_TEMP_SENSOR_0") (class "Default")
      (node (ref "R69") (pin "1") (pinfunction "1_1") (pintype "passive"))
      (node (ref "TEMP_SENSOR_0") (pin "2") (pinfunction "2_2") (pintype "passive"))
      (node (ref "U1") (pin "10") (pinfunction "RB2/AN8/C2INC/CTED1/PMA3/REFO/RP5_10") (pintype "bidirectional"))
    )
    (net (code "54") (name "MCU_0_TEMP_SENSOR_1") (class "Default")
      (node (ref "R70") (pin "1") (pinfunction "1_1") (pintype "passive"))
      (node (ref "TEMP_SENSOR_1") (pin "2") (pinfunction "2_2") (pintype "passive"))
      (node (ref "U1") (pin "11") (pinfunction "RB3/AN9/C3INA/CTED2/PMA2/RP6_11") (pintype "bidirectional"))
    )
    (net (code "55") (name "MCU_0_TEMP_SENSOR_2") (class "Default")
      (node (ref "R71") (pin "1") (pinfunction "1_1") (pintype "passive"))
      (node (ref "TEMP_SENSOR_2") (pin "2") (pinfunction "2_2") (pintype "passive"))
      (node (ref "U1") (pin "9") (pinfunction "RB1/AN10/C3INC/PMBE/RTCC/RP4_9") (pintype "bidirectional"))
    )
    (net (code "56") (name "MCU_0_TEMP_SENSOR_3") (class "Default")
      (node (ref "R72") (pin "1") (pinfunction "1_1") (pintype "passive"))
      (node (ref "TEMP_SENSOR_3") (pin "2") (pinfunction "2_2") (pintype "passive"))
      (node (ref "U1") (pin "8") (pinfunction "RB0/AN12/C3IND/INT0/RP3_8") (pintype "bidirectional"))
    )
    (net (code "57") (name "MCU_0_TILT_SENSOR") (class "Default")
      (node (ref "C79") (pin "1") (pinfunction "1_1") (pintype "passive"))
      (node (ref "R90") (pin "1") (pinfunction "1_1") (pintype "passive"))
      (node (ref "TILT") (pin "TP") (pinfunction "TP_TP") (pintype "input"))
      (node (ref "TILT_SENSOR") (pin "2") (pinfunction "2_2") (pintype "passive"))
      (node (ref "U1") (pin "36") (pinfunction "RC2/AN11/C2IND/CTPLS/RP13_36") (pintype "bidirectional"))
    )
    (net (code "58") (name "MCU_0_UART_RX") (class "Default")
      (node (ref "MCU0_RX") (pin "TP") (pinfunction "TP_TP") (pintype "input"))
      (node (ref "U1") (pin "1") (pinfunction "RC7/CCP10/PMA4/RX1/DT1/RP18_1") (pintype "bidirectional"))
      (node (ref "U15") (pin "40") (pinfunction "OSCO/CLKO/RPC15/RC15_40") (pintype "bidirectional"))
    )
    (net (code "59") (name "MCU_0_UART_TX") (class "Default")
      (node (ref "MCU0_TX") (pin "TP") (pinfunction "TP_TP") (pintype "input"))
      (node (ref "U1") (pin "44") (pinfunction "RC6/CCP9/PMA5/TX1/CK1/RP17_44") (pintype "bidirectional"))
      (node (ref "U15") (pin "46") (pinfunction "OA5OUT/AN25/CVD25/C5IN4-/RPB7/SCK1/INT0/RB7_46") (pintype "bidirectional"))
    )
    (net (code "60") (name "MCU_1_BLADE_MOTOR_PWM") (class "Default")
      (node (ref "IC1") (pin "18") (pinfunction "TDO/RP9/SDA1/CN21/PMD3/RB9_18") (pintype "passive"))
      (node (ref "R48") (pin "1") (pinfunction "1_1") (pintype "passive"))
      (node (ref "R97") (pin "1") (pinfunction "1_1") (pintype "passive"))
    )
    (net (code "61") (name "MCU_1_MCLR") (class "Default")
      (node (ref "IC1") (pin "1") (pinfunction "*MCLR_1") (pintype "passive"))
      (node (ref "MCU_1") (pin "P$4") (pinfunction "4_P$4") (pintype "bidirectional"))
      (node (ref "R9") (pin "1") (pinfunction "1_1") (pintype "passive"))
    )
    (net (code "62") (name "MCU_1_PGC") (class "Default")
      (node (ref "IC1") (pin "5") (pinfunction "PGC1/EMUC1/AN3/C2IN+/RP1/CN5/RB1_5") (pintype "passive"))
      (node (ref "MCU_1") (pin "P$3") (pinfunction "3_P$3") (pintype "bidirectional"))
    )
    (net (code "63") (name "MCU_1_PGD") (class "Default")
      (node (ref "IC1") (pin "4") (pinfunction "PGD1/EMUD1/AN2/C2IN-/RP0/CN4/RB0_4") (pintype "passive"))
      (node (ref "MCU_1") (pin "P$2") (pinfunction "2_P$2") (pintype "bidirectional"))
    )
    (net (code "64") (name "MCU_1_STEP_DRV_0_DIR") (class "Default")
      (node (ref "IC1") (pin "2") (pinfunction "AN0/VREF+/CN2/RA0_2") (pintype "passive"))
      (node (ref "SD1") (pin "1") (pinfunction "DIR_1") (pintype "bidirectional"))
    )
    (net (code "65") (name "MCU_1_STEP_DRV_0_ENABLE") (class "Default")
      (node (ref "IC1") (pin "6") (pinfunction "AN4/C1IN-/RP2/SDA2/CN6/RB2_6") (pintype "passive"))
      (node (ref "R94") (pin "1") (pinfunction "1_1") (pintype "passive"))
      (node (ref "SD1") (pin "18") (pinfunction "~{ENBL}_18") (pintype "bidirectional"))
    )
    (net (code "66") (name "MCU_1_STEP_DRV_0_MS1") (class "Default")
      (node (ref "IC1") (pin "7") (pinfunction "AN5/C1IN+/RP3/SCL2/CN7/RB3_7") (pintype "passive"))
      (node (ref "SD1") (pin "7") (pinfunction "MS1_7") (pintype "bidirectional"))
    )
    (net (code "67") (name "MCU_1_STEP_DRV_0_MS2") (class "Default")
      (node (ref "IC1") (pin "9") (pinfunction "OSCI/CLKI/CN30/RA2_9") (pintype "passive"))
      (node (ref "SD1") (pin "6") (pinfunction "MS2_6") (pintype "bidirectional"))
    )
    (net (code "68") (name "MCU_1_STEP_DRV_0_STEP") (class "Default")
      (node (ref "IC1") (pin "3") (pinfunction "AN1/VREF-/CN3/RA1_3") (pintype "passive"))
      (node (ref "SD1") (pin "13") (pinfunction "STEP_13") (pintype "bidirectional"))
    )
    (net (code "69") (name "MCU_1_STEP_DRV_1_DIR") (class "Default")
      (node (ref "IC1") (pin "10") (pinfunction "OSCO/CLKO/CN29/PMA0/RA3_10") (pintype "passive"))
      (node (ref "SD2") (pin "1") (pinfunction "DIR_1") (pintype "bidirectional"))
    )
    (net (code "70") (name "MCU_1_STEP_DRV_1_ENABLE") (class "Default")
      (node (ref "IC1") (pin "12") (pinfunction "SOSCO/T1CK/CN0/PMA1/RA4_12") (pintype "passive"))
      (node (ref "R95") (pin "1") (pinfunction "1_1") (pintype "passive"))
      (node (ref "SD2") (pin "18") (pinfunction "~{ENBL}_18") (pintype "bidirectional"))
    )
    (net (code "71") (name "MCU_1_STEP_DRV_1_MS1") (class "Default")
      (node (ref "IC1") (pin "14") (pinfunction "PGD3/EMUD3/RP5/ASDA1/CN27/PMD7/RB5_14") (pintype "passive"))
      (node (ref "SD2") (pin "7") (pinfunction "MS1_7") (pintype "bidirectional"))
    )
    (net (code "72") (name "MCU_1_STEP_DRV_1_MS2") (class "Default")
      (node (ref "IC1") (pin "15") (pinfunction "PGC3/EMUC3/RP6/ASCL1/CN24/PMD6/RB6_15") (pintype "passive"))
      (node (ref "SD2") (pin "6") (pinfunction "MS2_6") (pintype "bidirectional"))
    )
    (net (code "73") (name "MCU_1_STEP_DRV_1_STEP") (class "Default")
      (node (ref "IC1") (pin "11") (pinfunction "SOSCI/RP4/PMBE/CN1/RB4_11") (pintype "passive"))
      (node (ref "SD2") (pin "13") (pinfunction "STEP_13") (pintype "bidirectional"))
    )
    (net (code "74") (name "MCU_1_STEP_DRV_2_DIR") (class "Default")
      (node (ref "IC1") (pin "16") (pinfunction "RP7/INT0/CN23/PMD5/RB7_16") (pintype "passive"))
      (node (ref "SD3") (pin "1") (pinfunction "DIR_1") (pintype "bidirectional"))
    )
    (net (code "75") (name "MCU_1_STEP_DRV_2_ENABLE") (class "Default")
      (node (ref "IC1") (pin "19") (pinfunction "DISVREG_19") (pintype "passive"))
      (node (ref "R96") (pin "1") (pinfunction "1_1") (pintype "passive"))
      (node (ref "SD3") (pin "18") (pinfunction "~{ENBL}_18") (pintype "bidirectional"))
    )
    (net (code "76") (name "MCU_1_STEP_DRV_2_MS1") (class "Default")
      (node (ref "IC1") (pin "21") (pinfunction "PGD2/EMUD2/TDI/RP10/CN16/PMD2/RB10_21") (pintype "passive"))
      (node (ref "SD3") (pin "7") (pinfunction "MS1_7") (pintype "bidirectional"))
    )
    (net (code "77") (name "MCU_1_STEP_DRV_2_MS2") (class "Default")
      (node (ref "IC1") (pin "22") (pinfunction "PGC2/EMUC2/TMS/RP11/CN15/PMD1/RB11_22") (pintype "passive"))
      (node (ref "SD3") (pin "6") (pinfunction "MS2_6") (pintype "bidirectional"))
    )
    (net (code "78") (name "MCU_1_STEP_DRV_2_STEP") (class "Default")
      (node (ref "IC1") (pin "17") (pinfunction "TCK/RP8/SCL1/CN22/PMD4/RB8_17") (pintype "passive"))
      (node (ref "SD3") (pin "13") (pinfunction "STEP_13") (pintype "bidirectional"))
    )
    (net (code "79") (name "MCU_1_UART1_RX") (class "Default")
      (node (ref "IC1") (pin "26") (pinfunction "AN9/RP15/CN11/PMCS1/RB15_26") (pintype "passive"))
      (node (ref "MCU1_RX") (pin "TP") (pinfunction "TP_TP") (pintype "input"))
      (node (ref "MCU_1_UART_RX_SWITCH") (pin "2") (pinfunction "2_2") (pintype "passive"))
    )
    (net (code "80") (name "MCU_1_UART1_TX") (class "Default")
      (node (ref "IC1") (pin "25") (pinfunction "AN10/CVREF/RTCC/RP14/CN12/PMWR/RB14_25") (pintype "passive"))
      (node (ref "MCU1_TX") (pin "TP") (pinfunction "TP_TP") (pintype "input"))
      (node (ref "MCU_1_UART_TX_SWITCH") (pin "2") (pinfunction "2_2") (pintype "passive"))
    )
    (net (code "81") (name "MCU_2_LED0") (class "Default")
      (node (ref "R84") (pin "1") (pinfunction "1_1") (pintype "passive"))
      (node (ref "U15") (pin "51") (pinfunction "TRD0/RPC7/PWM12H/PWM6L/RC7_51") (pintype "bidirectional"))
    )
    (net (code "82") (name "MCU_2_LED1") (class "Default")
      (node (ref "R91") (pin "1") (pinfunction "1_1") (pintype "passive"))
      (node (ref "U15") (pin "52") (pinfunction "TRD1/RPC8/PWM5H/PMWR/RC8_52") (pintype "bidirectional"))
    )
    (net (code "83") (name "MCU_2_LED2") (class "Default")
      (node (ref "R92") (pin "1") (pinfunction "1_1") (pintype "passive"))
      (node (ref "U15") (pin "53") (pinfunction "TRD2/RPD5/PWM12H/PMRD/RD5_53") (pintype "bidirectional"))
    )
    (net (code "84") (name "MCU_2_LED3") (class "Default")
      (node (ref "R93") (pin "1") (pinfunction "1_1") (pintype "passive"))
      (node (ref "U15") (pin "54") (pinfunction "TRD3/RPD6/PWM12L/RD6_54") (pintype "bidirectional"))
    )
    (net (code "85") (name "MCU_2_LIDAR_ENABLE") (class "Default")
      (node (ref "R62") (pin "1") (pinfunction "1_1") (pintype "passive"))
      (node (ref "U15") (pin "42") (pinfunction "RD8_42") (pintype "bidirectional"))
    )
    (net (code "86") (name "MCU_2_MCLR") (class "Default")
      (node (ref "MCU_2") (pin "P$4") (pinfunction "4_P$4") (pintype "bidirectional"))
      (node (ref "R13") (pin "1") (pinfunction "1_1") (pintype "passive"))
      (node (ref "U15") (pin "7") (pinfunction "~{MCLR}_7") (pintype "input"))
    )
    (net (code "87") (name "MCU_2_PGC") (class "Default")
      (node (ref "MCU_2") (pin "P$3") (pinfunction "3_P$3") (pintype "bidirectional"))
      (node (ref "U15") (pin "17") (pinfunction "PGC1/OA1IN+/AN4/C1IN1+/C1IN3-/C2IN3-/RPB2/RB2_17") (pintype "bidirectional"))
    )
    (net (code "88") (name "MCU_2_PGD") (class "Default")
      (node (ref "MCU_2") (pin "P$2") (pinfunction "2_P$2") (pintype "bidirectional"))
      (node (ref "U15") (pin "18") (pinfunction "PGD1/OA1IN-/AN5/CTCMP/C1IN1-/RTCC/RPB3/RB3_18") (pintype "bidirectional"))
    )
    (net (code "89") (name "MCU_2_SCL") (class "Default")
      (node (ref "MCU_2_I2C_EXTENDER") (pin "2") (pinfunction "2_2") (pintype "passive"))
      (node (ref "MPU6050_SCL") (pin "TP") (pinfunction "TP_TP") (pintype "input"))
      (node (ref "R37") (pin "2") (pinfunction "2_2") (pintype "passive"))
      (node (ref "U15") (pin "28") (pinfunction "AN13/CVD13/C3IN2-/FLT6/SCL4/PMA10/RE13_28") (pintype "bidirectional"))
      (node (ref "U2") (pin "1") (pinfunction "SCL/SPC_1") (pintype "input"))
      (node (ref "U5") (pin "23") (pinfunction "SCL_23") (pintype "bidirectional"))
    )
    (net (code "90") (name "MCU_2_SDA") (class "Default")
      (node (ref "MCU_2_I2C_EXTENDER") (pin "1") (pinfunction "1_1") (pintype "passive"))
      (node (ref "MPU6050_SDA") (pin "TP") (pinfunction "TP_TP") (pintype "input"))
      (node (ref "R36") (pin "2") (pinfunction "2_2") (pintype "passive"))
      (node (ref "U15") (pin "27") (pinfunction "AN12/CVD12/C2IN2-/C5IN2-/SDA4/FLT5/PMA11/RE12_27") (pintype "bidirectional"))
      (node (ref "U2") (pin "11") (pinfunction "SDA/SDI/SDO_11") (pintype "bidirectional"))
      (node (ref "U5") (pin "24") (pinfunction "SDA_24") (pintype "bidirectional"))
    )
    (net (code "91") (name "MCU_2_UART3_RX") (class "Default")
      (node (ref "MCU_1_UART_TX_SWITCH") (pin "1") (pinfunction "1_1") (pintype "passive"))
      (node (ref "U15") (pin "1") (pinfunction "TCK/RPA7/PWM10H/PWM4L/PMD5/RA7_1") (pintype "bidirectional"))
    )
    (net (code "92") (name "MCU_2_UART3_TX") (class "Default")
      (node (ref "MCU_1_UART_RX_SWITCH") (pin "1") (pinfunction "1_1") (pintype "passive"))
      (node (ref "U15") (pin "2") (pinfunction "RPB14/PWM1H/VBUSON1/PMD6/RB14_2") (pintype "bidirectional"))
    )
    (net (code "93") (name "MCU_3_BUTTON_0") (class "Default")
      (node (ref "BUTTONS") (pin "1") (pinfunction "1_1") (pintype "passive"))
      (node (ref "C1") (pin "1") (pinfunction "1_1") (pintype "passive"))
      (node (ref "MCU_3_ESP32") (pin "6") (pinfunction "IO34_6") (pintype "bidirectional"))
      (node (ref "R111") (pin "1") (pinfunction "1_1") (pintype "passive"))
    )
    (net (code "94") (name "MCU_3_BUTTON_1") (class "Default")
      (node (ref "BUTTONS") (pin "2") (pinfunction "2_2") (pintype "passive"))
      (node (ref "C4") (pin "1") (pinfunction "1_1") (pintype "passive"))
      (node (ref "MCU_3_ESP32") (pin "7") (pinfunction "IO35_7") (pintype "bidirectional"))
      (node (ref "R112") (pin "1") (pinfunction "1_1") (pintype "passive"))
    )
    (net (code "95") (name "MCU_3_BUTTON_2") (class "Default")
      (node (ref "BUTTONS") (pin "3") (pinfunction "3_3") (pintype "passive"))
      (node (ref "C73") (pin "1") (pinfunction "1_1") (pintype "passive"))
      (node (ref "MCU_3_ESP32") (pin "8") (pinfunction "IO32_8") (pintype "bidirectional"))
      (node (ref "R113") (pin "1") (pinfunction "1_1") (pintype "passive"))
    )
    (net (code "96") (name "MCU_3_BUTTON_3") (class "Default")
      (node (ref "BUTTONS") (pin "4") (pinfunction "4_4") (pintype "passive"))
      (node (ref "C74") (pin "1") (pinfunction "1_1") (pintype "passive"))
      (node (ref "MCU_3_ESP32") (pin "9") (pinfunction "IO33_9") (pintype "bidirectional"))
      (node (ref "R114") (pin "1") (pinfunction "1_1") (pintype "passive"))
    )
    (net (code "97") (name "MCU_3_BUTTON_4") (class "Default")
      (node (ref "BUTTONS") (pin "5") (pinfunction "5_5") (pintype "passive"))
      (node (ref "C75") (pin "1") (pinfunction "1_1") (pintype "passive"))
      (node (ref "MCU_3_ESP32") (pin "10") (pinfunction "IO25_10") (pintype "bidirectional"))
      (node (ref "R115") (pin "1") (pinfunction "1_1") (pintype "passive"))
    )
    (net (code "98") (name "MCU_3_BUTTON_5") (class "Default")
      (node (ref "BUTTONS") (pin "6") (pinfunction "6_6") (pintype "passive"))
      (node (ref "C76") (pin "1") (pinfunction "1_1") (pintype "passive"))
      (node (ref "MCU_3_ESP32") (pin "11") (pinfunction "IO26_11") (pintype "bidirectional"))
      (node (ref "R116") (pin "1") (pinfunction "1_1") (pintype "passive"))
    )
    (net (code "99") (name "MCU_3_BUTTON_6") (class "Default")
      (node (ref "BUTTONS") (pin "7") (pinfunction "7_7") (pintype "passive"))
      (node (ref "C77") (pin "1") (pinfunction "1_1") (pintype "passive"))
      (node (ref "MCU_3_ESP32") (pin "12") (pinfunction "IO27_12") (pintype "bidirectional"))
      (node (ref "R117") (pin "1") (pinfunction "1_1") (pintype "passive"))
    )
    (net (code "100") (name "MCU_3_BUTTON_7") (class "Default")
      (node (ref "BUTTONS") (pin "8") (pinfunction "8_8") (pintype "passive"))
      (node (ref "C78") (pin "1") (pinfunction "1_1") (pintype "passive"))
      (node (ref "MCU_3_ESP32") (pin "13") (pinfunction "IO14_13") (pintype "bidirectional"))
      (node (ref "R118") (pin "1") (pinfunction "1_1") (pintype "passive"))
    )
    (net (code "101") (name "MCU_3_I2C_SCL") (class "Default")
      (node (ref "DISPLAY") (pin "1") (pinfunction "1_1") (pintype "passive"))
      (node (ref "MCU3_SCL") (pin "TP") (pinfunction "TP_TP") (pintype "input"))
      (node (ref "MCU_3_ESP32") (pin "36") (pinfunction "IO22_36") (pintype "bidirectional"))
      (node (ref "R105") (pin "1") (pinfunction "1_1") (pintype "passive"))
      (node (ref "R5") (pin "2") (pinfunction "2_2") (pintype "passive"))
      (node (ref "RTCC") (pin "3") (pinfunction "SCL_3") (pintype "bidirectional"))
    )
    (net (code "102") (name "MCU_3_I2C_SDA") (class "Default")
      (node (ref "DISPLAY") (pin "2") (pinfunction "2_2") (pintype "passive"))
      (node (ref "MCU3_SDA") (pin "TP") (pinfunction "TP_TP") (pintype "input"))
      (node (ref "MCU_3_ESP32") (pin "33") (pinfunction "IO21_33") (pintype "bidirectional"))
      (node (ref "R106") (pin "1") (pinfunction "1_1") (pintype "passive"))
      (node (ref "R26") (pin "2") (pinfunction "2_2") (pintype "passive"))
      (node (ref "RTCC") (pin "4") (pinfunction "SDA_4") (pintype "bidirectional"))
    )
    (net (code "103") (name "MCU_3_LED_B") (class "Default")
      (node (ref "MCU_3_ESP32") (pin "23") (pinfunction "IO15_23") (pintype "bidirectional"))
      (node (ref "RGB_LED") (pin "3") (pinfunction "3_3") (pintype "passive"))
    )
    (net (code "104") (name "MCU_3_LED_G") (class "Default")
      (node (ref "MCU_3_ESP32") (pin "24") (pinfunction "IO2_24") (pintype "bidirectional"))
      (node (ref "RGB_LED") (pin "2") (pinfunction "2_2") (pintype "passive"))
    )
    (net (code "105") (name "MCU_3_LED_R") (class "Default")
      (node (ref "MCU_3_ESP32") (pin "26") (pinfunction "IO4_26") (pintype "bidirectional"))
      (node (ref "RGB_LED") (pin "1") (pinfunction "1_1") (pintype "passive"))
    )
    (net (code "106") (name "MCU_3_SD_DET") (class "Default")
      (node (ref "MCU_3_ESP32") (pin "22") (pinfunction "SD1_22") (pintype "bidirectional"))
      (node (ref "R103") (pin "1") (pinfunction "1_1") (pintype "passive"))
      (node (ref "X5") (pin "DETECT") (pinfunction "DETECT_DETECT") (pintype "input"))
    )
    (net (code "107") (name "MCU_3_SD_WRTPT") (class "Default")
      (node (ref "MCU_3_ESP32") (pin "21") (pinfunction "SD0_21") (pintype "bidirectional"))
      (node (ref "R104") (pin "1") (pinfunction "1_1") (pintype "passive"))
      (node (ref "X5") (pin "WRITE_PROT") (pinfunction "WRITE_PROT_WRITE_PROT") (pintype "input"))
    )
    (net (code "108") (name "MCU_3_SPI_MISO") (class "Default")
      (node (ref "MCU_3_ESP32") (pin "31") (pinfunction "IO19_31") (pintype "bidirectional"))
      (node (ref "R99") (pin "1") (pinfunction "1_1") (pintype "passive"))
      (node (ref "X5") (pin "7") (pinfunction "7_7") (pintype "input"))
    )
    (net (code "109") (name "MCU_3_SPI_MOSI") (class "Default")
      (node (ref "MCU_3_ESP32") (pin "37") (pinfunction "IO23_37") (pintype "bidirectional"))
      (node (ref "R98") (pin "1") (pinfunction "1_1") (pintype "passive"))
      (node (ref "X5") (pin "2") (pinfunction "2_2") (pintype "input"))
    )
    (net (code "110") (name "MCU_3_SPI_SCK") (class "Default")
      (node (ref "MCU_3_ESP32") (pin "30") (pinfunction "IO18_30") (pintype "bidirectional"))
      (node (ref "X5") (pin "5") (pinfunction "5_5") (pintype "input"))
    )
    (net (code "111") (name "MCU_3_SPI_SS") (class "Default")
      (node (ref "MCU_3_ESP32") (pin "29") (pinfunction "IO5_29") (pintype "bidirectional"))
      (node (ref "R100") (pin "1") (pinfunction "1_1") (pintype "passive"))
      (node (ref "X5") (pin "1") (pinfunction "1_1") (pintype "input"))
    )
    (net (code "112") (name "MCU_3_TRIGGER_CAMERA") (class "Default")
      (node (ref "CAMERA") (pin "1") (pinfunction "1_1") (pintype "passive"))
      (node (ref "MCU_3_ESP32") (pin "14") (pinfunction "IO12_14") (pintype "bidirectional"))
    )
    (net (code "113") (name "MCU_3_UART1_RX") (class "Default")
      (node (ref "MCU3_RX") (pin "TP") (pinfunction "TP_TP") (pintype "input"))
      (node (ref "MCU_1_UART_TX_SWITCH") (pin "3") (pinfunction "3_3") (pintype "passive"))
      (node (ref "MCU_3_ESP32") (pin "17") (pinfunction "SD2_17") (pintype "bidirectional"))
    )
    (net (code "114") (name "MCU_3_UART1_TX") (class "Default")
      (node (ref "MCU3_TX") (pin "TP") (pinfunction "TP_TP") (pintype "input"))
      (node (ref "MCU_1_UART_RX_SWITCH") (pin "3") (pinfunction "3_3") (pintype "passive"))
      (node (ref "MCU_3_ESP32") (pin "18") (pinfunction "SD3_18") (pintype "bidirectional"))
    )
    (net (code "115") (name "MCU_3_UART2_RX") (class "Default")
      (node (ref "MCU_3_ESP32") (pin "27") (pinfunction "IO16_27") (pintype "bidirectional"))
      (node (ref "NAVIGATION_UART") (pin "1") (pinfunction "1_1") (pintype "passive"))
      (node (ref "U15") (pin "12") (pinfunction "AN9/CVD9/RPA11/RA11_12") (pintype "bidirectional"))
    )
    (net (code "116") (name "MCU_3_UART2_TX") (class "Default")
      (node (ref "MCU_3_ESP32") (pin "28") (pinfunction "IO17_28") (pintype "bidirectional"))
      (node (ref "NAVIGATION_UART") (pin "2") (pinfunction "2_2") (pintype "passive"))
      (node (ref "U15") (pin "33") (pinfunction "OA5IN+/DAC1/AN24/CVD24/C5IN1+/C5IN3-/RPA4/RA4_33") (pintype "bidirectional"))
    )
    (net (code "117") (name "MPU6050_INT") (class "Default")
      (node (ref "U5") (pin "12") (pinfunction "INT_12") (pintype "output"))
    )
    (net (code "118") (name "Net-(BUTTONS-Pad9)") (class "Default")
      (node (ref "BUTTONS") (pin "9") (pinfunction "9_9") (pintype "passive"))
      (node (ref "R27") (pin "2") (pinfunction "2_2") (pintype "passive"))
    )
    (net (code "119") (name "Net-(BUZZER-2)") (class "Default")
      (node (ref "BUZZER") (pin "-") (pinfunction "2_-") (pintype "passive"))
      (node (ref "R25") (pin "2") (pinfunction "2_2") (pintype "passive"))
    )
    (net (code "120") (name "Net-(C6-Pad1)") (class "Default")
      (node (ref "C6") (pin "1") (pinfunction "1_1") (pintype "passive"))
      (node (ref "R8") (pin "1") (pinfunction "1_1") (pintype "passive"))
      (node (ref "R9") (pin "2") (pinfunction "2_2") (pintype "passive"))
    )
    (net (code "121") (name "Net-(C11-Pad1)") (class "Default")
      (node (ref "C11") (pin "1") (pinfunction "1_1") (pintype "passive"))
      (node (ref "R10") (pin "1") (pinfunction "1_1") (pintype "passive"))
      (node (ref "R11") (pin "2") (pinfunction "2_2") (pintype "passive"))
    )
    (net (code "122") (name "Net-(C15-Pad1)") (class "Default")
      (node (ref "C15") (pin "1") (pinfunction "1_1") (pintype "passive"))
      (node (ref "R12") (pin "1") (pinfunction "1_1") (pintype "passive"))
      (node (ref "R13") (pin "2") (pinfunction "2_2") (pintype "passive"))
    )
    (net (code "123") (name "Net-(C81-Pad1)") (class "Default")
      (node (ref "C81") (pin "1") (pinfunction "1_1") (pintype "passive"))
      (node (ref "L3") (pin "1") (pinfunction "1_1") (pintype "passive"))
      (node (ref "X5") (pin "4") (pinfunction "4_4") (pintype "input"))
    )
    (net (code "124") (name "Net-(CP2102-REGIN)") (class "Default")
      (node (ref "C37") (pin "2") (pinfunction "2_2") (pintype "passive"))
      (node (ref "C38") (pin "2") (pinfunction "2_2") (pintype "passive"))
      (node (ref "CP2102") (pin "7") (pinfunction "REGIN_7") (pintype "passive"))
      (node (ref "CP2102") (pin "8") (pinfunction "VBUS_8") (pintype "input"))
      (node (ref "D3") (pin "C") (pinfunction "C_C") (pintype "passive"))
      (node (ref "MICROUSB") (pin "1") (pinfunction "VBUS_1") (pintype "power_in"))
    )
    (net (code "125") (name "Net-(CURRENT_SENSOR_BATT-AOUT)") (class "Default")
      (node (ref "C31") (pin "1") (pinfunction "1_1") (pintype "passive"))
      (node (ref "CURRENT_SENSOR_BATT") (pin "4") (pinfunction "AOUT_4") (pintype "output"))
      (node (ref "R21") (pin "1") (pinfunction "1_1") (pintype "passive"))
    )
    (net (code "126") (name "Net-(CURRENT_SENSOR_BATT-VREF)") (class "Default")
      (node (ref "C33") (pin "1") (pinfunction "1_1") (pintype "passive"))
      (node (ref "CURRENT_SENSOR_BATT") (pin "3") (pinfunction "VREF_3") (pintype "bidirectional"))
      (node (ref "R20") (pin "2") (pinfunction "2_2") (pintype "passive"))
    )
    (net (code "127") (name "Net-(EM_LIGHT-Pad2)") (class "Default")
      (node (ref "EM_LIGHT") (pin "2") (pinfunction "2_2") (pintype "passive"))
      (node (ref "NMOS6") (pin "5") (pinfunction "D_5") (pintype "passive"))
      (node (ref "NMOS6") (pin "6") (pinfunction "D_6") (pintype "passive"))
      (node (ref "NMOS6") (pin "7") (pinfunction "D_7") (pintype "passive"))
      (node (ref "NMOS6") (pin "8") (pinfunction "D_8") (pintype "passive"))
      (node (ref "NMOS6") (pin "TH") (pinfunction "TH_TH") (pintype "passive"))
    )
    (net (code "128") (name "Net-(FAN_0-Pad2)") (class "Default")
      (node (ref "FAN_0") (pin "2") (pinfunction "2_2") (pintype "passive"))
      (node (ref "NMOS2") (pin "5") (pinfunction "D_5") (pintype "passive"))
      (node (ref "NMOS2") (pin "6") (pinfunction "D_6") (pintype "passive"))
      (node (ref "NMOS2") (pin "7") (pinfunction "D_7") (pintype "passive"))
      (node (ref "NMOS2") (pin "8") (pinfunction "D_8") (pintype "passive"))
      (node (ref "NMOS2") (pin "TH") (pinfunction "TH_TH") (pintype "passive"))
    )
    (net (code "129") (name "Net-(FAN_1-Pad2)") (class "Default")
      (node (ref "FAN_1") (pin "2") (pinfunction "2_2") (pintype "passive"))
      (node (ref "NMOS3") (pin "5") (pinfunction "D_5") (pintype "passive"))
      (node (ref "NMOS3") (pin "6") (pinfunction "D_6") (pintype "passive"))
      (node (ref "NMOS3") (pin "7") (pinfunction "D_7") (pintype "passive"))
      (node (ref "NMOS3") (pin "8") (pinfunction "D_8") (pintype "passive"))
      (node (ref "NMOS3") (pin "TH") (pinfunction "TH_TH") (pintype "passive"))
    )
    (net (code "130") (name "Net-(FAN_2-Pad2)") (class "Default")
      (node (ref "FAN_2") (pin "2") (pinfunction "2_2") (pintype "passive"))
      (node (ref "NMOS4") (pin "5") (pinfunction "D_5") (pintype "passive"))
      (node (ref "NMOS4") (pin "6") (pinfunction "D_6") (pintype "passive"))
      (node (ref "NMOS4") (pin "7") (pinfunction "D_7") (pintype "passive"))
      (node (ref "NMOS4") (pin "8") (pinfunction "D_8") (pintype "passive"))
      (node (ref "NMOS4") (pin "TH") (pinfunction "TH_TH") (pintype "passive"))
    )
    (net (code "131") (name "Net-(FAN_3-Pad2)") (class "Default")
      (node (ref "FAN_3") (pin "2") (pinfunction "2_2") (pintype "passive"))
      (node (ref "NMOS5") (pin "5") (pinfunction "D_5") (pintype "passive"))
      (node (ref "NMOS5") (pin "6") (pinfunction "D_6") (pintype "passive"))
      (node (ref "NMOS5") (pin "7") (pinfunction "D_7") (pintype "passive"))
      (node (ref "NMOS5") (pin "8") (pinfunction "D_8") (pintype "passive"))
      (node (ref "NMOS5") (pin "TH") (pinfunction "TH_TH") (pintype "passive"))
    )
    (net (code "132") (name "Net-(IC1-VCAP{slash}VDDCORE)") (class "Default")
      (node (ref "C13") (pin "1") (pinfunction "1_1") (pintype "passive"))
      (node (ref "IC1") (pin "20") (pinfunction "VCAP/VDDCORE_20") (pintype "passive"))
    )
    (net (code "133") (name "Net-(LED1-PadA)") (class "Default")
      (node (ref "LED1") (pin "A") (pinfunction "A_A") (pintype "passive"))
      (node (ref "R75") (pin "1") (pinfunction "1_1") (pintype "passive"))
    )
    (net (code "134") (name "Net-(LED2-PadA)") (class "Default")
      (node (ref "LED2") (pin "A") (pinfunction "A_A") (pintype "passive"))
      (node (ref "R28") (pin "2") (pinfunction "2_2") (pintype "passive"))
    )
    (net (code "135") (name "Net-(LED3-PadA)") (class "Default")
      (node (ref "LED3") (pin "A") (pinfunction "A_A") (pintype "passive"))
      (node (ref "R29") (pin "2") (pinfunction "2_2") (pintype "passive"))
    )
    (net (code "136") (name "Net-(LED4-PadA)") (class "Default")
      (node (ref "LED4") (pin "A") (pinfunction "A_A") (pintype "passive"))
      (node (ref "R30") (pin "2") (pinfunction "2_2") (pintype "passive"))
    )
    (net (code "137") (name "Net-(LED5-PadA)") (class "Default")
      (node (ref "LED5") (pin "A") (pinfunction "A_A") (pintype "passive"))
      (node (ref "R31") (pin "2") (pinfunction "2_2") (pintype "passive"))
    )
    (net (code "138") (name "Net-(LED7-PadA)") (class "Default")
      (node (ref "LED7") (pin "A") (pinfunction "A_A") (pintype "passive"))
      (node (ref "R61") (pin "2") (pinfunction "2_2") (pintype "passive"))
    )
    (net (code "139") (name "Net-(LED8-PadA)") (class "Default")
      (node (ref "LED8") (pin "A") (pinfunction "A_A") (pintype "passive"))
      (node (ref "R121") (pin "2") (pinfunction "2_2") (pintype "passive"))
    )
    (net (code "140") (name "Net-(LED12-PadA)") (class "Default")
      (node (ref "LED12") (pin "A") (pinfunction "A_A") (pintype "passive"))
      (node (ref "R80") (pin "2") (pinfunction "2_2") (pintype "passive"))
    )
    (net (code "141") (name "Net-(LED13-PadA)") (class "Default")
      (node (ref "LED13") (pin "A") (pinfunction "A_A") (pintype "passive"))
      (node (ref "R82") (pin "2") (pinfunction "2_2") (pintype "passive"))
    )
    (net (code "142") (name "Net-(LED14-PadA)") (class "Default")
      (node (ref "LED14") (pin "A") (pinfunction "A_A") (pintype "passive"))
      (node (ref "R83") (pin "2") (pinfunction "2_2") (pintype "passive"))
    )
    (net (code "143") (name "Net-(LED15-PadA)") (class "Default")
      (node (ref "LED15") (pin "A") (pinfunction "A_A") (pintype "passive"))
      (node (ref "R84") (pin "2") (pinfunction "2_2") (pintype "passive"))
    )
    (net (code "144") (name "Net-(LED16-PadA)") (class "Default")
      (node (ref "LED16") (pin "A") (pinfunction "A_A") (pintype "passive"))
      (node (ref "R85") (pin "2") (pinfunction "2_2") (pintype "passive"))
    )
    (net (code "145") (name "Net-(LED17-PadA)") (class "Default")
      (node (ref "LED17") (pin "A") (pinfunction "A_A") (pintype "passive"))
      (node (ref "R86") (pin "2") (pinfunction "2_2") (pintype "passive"))
    )
    (net (code "146") (name "Net-(LED18-PadA)") (class "Default")
      (node (ref "LED18") (pin "A") (pinfunction "A_A") (pintype "passive"))
      (node (ref "R87") (pin "2") (pinfunction "2_2") (pintype "passive"))
    )
    (net (code "147") (name "Net-(LED19-PadA)") (class "Default")
      (node (ref "LED19") (pin "A") (pinfunction "A_A") (pintype "passive"))
      (node (ref "R88") (pin "2") (pinfunction "2_2") (pintype "passive"))
    )
    (net (code "148") (name "Net-(LED20-PadA)") (class "Default")
      (node (ref "LED20") (pin "A") (pinfunction "A_A") (pintype "passive"))
      (node (ref "R89") (pin "2") (pinfunction "2_2") (pintype "passive"))
    )
    (net (code "149") (name "Net-(LED21-PadA)") (class "Default")
      (node (ref "LED21") (pin "A") (pinfunction "A_A") (pintype "passive"))
      (node (ref "R91") (pin "2") (pinfunction "2_2") (pintype "passive"))
    )
    (net (code "150") (name "Net-(LED22-PadA)") (class "Default")
      (node (ref "LED22") (pin "A") (pinfunction "A_A") (pintype "passive"))
      (node (ref "R92") (pin "2") (pinfunction "2_2") (pintype "passive"))
    )
    (net (code "151") (name "Net-(LED23-PadA)") (class "Default")
      (node (ref "LED23") (pin "A") (pinfunction "A_A") (pintype "passive"))
      (node (ref "R93") (pin "2") (pinfunction "2_2") (pintype "passive"))
    )
    (net (code "152") (name "Net-(LED24-PadA)") (class "Default")
      (node (ref "LED24") (pin "A") (pinfunction "A_A") (pintype "passive"))
      (node (ref "R94") (pin "2") (pinfunction "2_2") (pintype "passive"))
    )
    (net (code "153") (name "Net-(LED25-PadA)") (class "Default")
      (node (ref "LED25") (pin "A") (pinfunction "A_A") (pintype "passive"))
      (node (ref "R95") (pin "2") (pinfunction "2_2") (pintype "passive"))
    )
    (net (code "154") (name "Net-(LED26-PadA)") (class "Default")
      (node (ref "LED26") (pin "A") (pinfunction "A_A") (pintype "passive"))
      (node (ref "R96") (pin "2") (pinfunction "2_2") (pintype "passive"))
    )
    (net (code "155") (name "Net-(LED27-PadA)") (class "Default")
      (node (ref "LED27") (pin "A") (pinfunction "A_A") (pintype "passive"))
      (node (ref "R97") (pin "2") (pinfunction "2_2") (pintype "passive"))
    )
    (net (code "156") (name "Net-(LIDAR-Pad5)") (class "Default")
      (node (ref "LIDAR") (pin "5") (pinfunction "5_5") (pintype "passive"))
      (node (ref "NMOS1") (pin "5") (pinfunction "D_5") (pintype "passive"))
      (node (ref "NMOS1") (pin "6") (pinfunction "D_6") (pintype "passive"))
      (node (ref "NMOS1") (pin "7") (pinfunction "D_7") (pintype "passive"))
      (node (ref "NMOS1") (pin "8") (pinfunction "D_8") (pintype "passive"))
      (node (ref "NMOS1") (pin "TH") (pinfunction "TH_TH") (pintype "passive"))
    )
    (net (code "157") (name "Net-(LIGHT_SENSOR-Pad1)") (class "Default")
      (node (ref "LIGHT_SENSOR") (pin "1") (pinfunction "1_1") (pintype "passive"))
      (node (ref "R64") (pin "2") (pinfunction "2_2") (pintype "passive"))
      (node (ref "R66") (pin "2") (pinfunction "2_2") (pintype "passive"))
    )
    (net (code "158") (name "Net-(LIMIT_SWITCH_DOWN-Pad2)") (class "Default")
      (node (ref "LIMIT_SWITCH_DOWN") (pin "2") (pinfunction "2_2") (pintype "passive"))
      (node (ref "R108") (pin "2") (pinfunction "2_2") (pintype "passive"))
      (node (ref "R109") (pin "2") (pinfunction "2_2") (pintype "passive"))
    )
    (net (code "159") (name "Net-(LIMIT_SWITCH_UP-Pad2)") (class "Default")
      (node (ref "LIMIT_SWITCH_UP") (pin "2") (pinfunction "2_2") (pintype "passive"))
      (node (ref "R107") (pin "2") (pinfunction "2_2") (pintype "passive"))
      (node (ref "R110") (pin "2") (pinfunction "2_2") (pintype "passive"))
    )
    (net (code "160") (name "Net-(MAIN_MOTOR_CS-AOUT)") (class "Default")
      (node (ref "C28") (pin "1") (pinfunction "1_1") (pintype "passive"))
      (node (ref "MAIN_MOTOR_CS") (pin "4") (pinfunction "AOUT_4") (pintype "output"))
      (node (ref "R19") (pin "1") (pinfunction "1_1") (pintype "passive"))
    )
    (net (code "161") (name "Net-(MAIN_MOTOR_CS-VREF)") (class "Default")
      (node (ref "C30") (pin "1") (pinfunction "1_1") (pintype "passive"))
      (node (ref "MAIN_MOTOR_CS") (pin "3") (pinfunction "VREF_3") (pintype "bidirectional"))
      (node (ref "R18") (pin "2") (pinfunction "2_2") (pintype "passive"))
    )
    (net (code "162") (name "Net-(MCU_3_ESP32-EN)") (class "Default")
      (node (ref "EN") (pin "1") (pinfunction "1_1") (pintype "passive"))
      (node (ref "MCU_3_ESP32") (pin "3") (pinfunction "EN_3") (pintype "input"))
      (node (ref "R73") (pin "2") (pinfunction "2_2") (pintype "passive"))
    )
    (net (code "163") (name "Net-(MCU_3_ESP32-IO0)") (class "Default")
      (node (ref "BOOT") (pin "1") (pinfunction "1_1") (pintype "passive"))
      (node (ref "MCU_3_ESP32") (pin "25") (pinfunction "IO0_25") (pintype "bidirectional"))
      (node (ref "R74") (pin "1") (pinfunction "1_1") (pintype "passive"))
    )
    (net (code "164") (name "Net-(MCU_3_ESP32-IO13)") (class "Default")
      (node (ref "MCU_3_ESP32") (pin "16") (pinfunction "IO13_16") (pintype "bidirectional"))
      (node (ref "R75") (pin "2") (pinfunction "2_2") (pintype "passive"))
    )
    (net (code "165") (name "Net-(NMOS1A-G)") (class "Default")
      (node (ref "NMOS1") (pin "4") (pinfunction "G_4") (pintype "passive"))
      (node (ref "R54") (pin "1") (pinfunction "1_1") (pintype "passive"))
      (node (ref "U10") (pin "3") (pinfunction "3_3") (pintype "passive"))
    )
    (net (code "166") (name "Net-(NMOS2A-G)") (class "Default")
      (node (ref "NMOS2") (pin "4") (pinfunction "G_4") (pintype "passive"))
      (node (ref "R76") (pin "1") (pinfunction "1_1") (pintype "passive"))
      (node (ref "U4") (pin "3") (pinfunction "3_3") (pintype "passive"))
    )
    (net (code "167") (name "Net-(NMOS3A-G)") (class "Default")
      (node (ref "NMOS3") (pin "4") (pinfunction "G_4") (pintype "passive"))
      (node (ref "R63") (pin "1") (pinfunction "1_1") (pintype "passive"))
      (node (ref "U6") (pin "3") (pinfunction "3_3") (pintype "passive"))
    )
    (net (code "168") (name "Net-(NMOS4A-G)") (class "Default")
      (node (ref "NMOS4") (pin "4") (pinfunction "G_4") (pintype "passive"))
      (node (ref "R65") (pin "1") (pinfunction "1_1") (pintype "passive"))
      (node (ref "U7") (pin "3") (pinfunction "3_3") (pintype "passive"))
    )
    (net (code "169") (name "Net-(NMOS5A-G)") (class "Default")
      (node (ref "NMOS5") (pin "4") (pinfunction "G_4") (pintype "passive"))
      (node (ref "R67") (pin "1") (pinfunction "1_1") (pintype "passive"))
      (node (ref "U8") (pin "3") (pinfunction "3_3") (pintype "passive"))
    )
    (net (code "170") (name "Net-(NMOS6A-G)") (class "Default")
      (node (ref "NMOS6") (pin "4") (pinfunction "G_4") (pintype "passive"))
      (node (ref "R68") (pin "1") (pinfunction "1_1") (pintype "passive"))
      (node (ref "U12") (pin "3") (pinfunction "3_3") (pintype "passive"))
    )
    (net (code "171") (name "Net-(NMOS7A-G)") (class "Default")
      (node (ref "NMOS7") (pin "4") (pinfunction "G_4") (pintype "passive"))
      (node (ref "R23") (pin "1") (pinfunction "1_1") (pintype "passive"))
      (node (ref "U11") (pin "3") (pinfunction "3_3") (pintype "passive"))
    )
    (net (code "172") (name "Net-(PERIMETER_WIRE-Pad2)") (class "Default")
      (node (ref "PERIMETER_WIRE") (pin "2") (pinfunction "2_2") (pintype "passive"))
      (node (ref "R4") (pin "2") (pinfunction "2_2") (pintype "passive"))
    )
    (net (code "173") (name "Net-(Q1-D)") (class "Default")
      (node (ref "C80") (pin "+") (pinfunction "+_+") (pintype "passive"))
      (node (ref "D6") (pin "C") (pinfunction "C_C") (pintype "passive"))
      (node (ref "L1") (pin "2") (pinfunction "2_2") (pintype "bidirectional"))
      (node (ref "Q1") (pin "3") (pinfunction "D_3") (pintype "passive"))
    )
    (net (code "174") (name "Net-(Q1-G)") (class "Default")
      (node (ref "D6") (pin "A") (pinfunction "A_A") (pintype "passive"))
      (node (ref "Q1") (pin "1") (pinfunction "G_1") (pintype "passive"))
      (node (ref "R1") (pin "2") (pinfunction "2_2") (pintype "passive"))
    )
    (net (code "175") (name "Net-(Q1-S)") (class "Default")
      (node (ref "PPTC") (pin "1") (pinfunction "1_1") (pintype "passive"))
      (node (ref "Q1") (pin "2") (pinfunction "S_2") (pintype "passive"))
      (node (ref "TVS25V") (pin "C") (pinfunction "C_C") (pintype "passive"))
    )
    (net (code "176") (name "Net-(Q8-G)") (class "Default")
      (node (ref "Q8") (pin "1") (pinfunction "G_1") (pintype "passive"))
      (node (ref "R77") (pin "2") (pinfunction "2_2") (pintype "passive"))
      (node (ref "R81") (pin "1") (pinfunction "1_1") (pintype "passive"))
    )
    (net (code "177") (name "Net-(R22-Pad2)") (class "Default")
      (node (ref "R22") (pin "2") (pinfunction "2_2") (pintype "passive"))
      (node (ref "U4") (pin "1") (pinfunction "1_1") (pintype "passive"))
    )
    (net (code "178") (name "Net-(R24-Pad2)") (class "Default")
      (node (ref "R24") (pin "2") (pinfunction "2_2") (pintype "passive"))
      (node (ref "T2") (pin "B") (pinfunction "B_B") (pintype "passive"))
    )
    (net (code "179") (name "Net-(R25-Pad1)") (class "Default")
      (node (ref "R25") (pin "1") (pinfunction "1_1") (pintype "passive"))
      (node (ref "T2") (pin "C") (pinfunction "C_C") (pintype "passive"))
    )
    (net (code "180") (name "Net-(R47-Pad2)") (class "Default")
      (node (ref "R47") (pin "2") (pinfunction "2_2") (pintype "passive"))
      (node (ref "U13") (pin "4") (pinfunction "4_4") (pintype "passive"))
    )
    (net (code "181") (name "Net-(R48-Pad2)") (class "Default")
      (node (ref "R48") (pin "2") (pinfunction "2_2") (pintype "passive"))
      (node (ref "U11") (pin "1") (pinfunction "1_1") (pintype "passive"))
    )
    (net (code "182") (name "Net-(R51-Pad2)") (class "Default")
      (node (ref "R51") (pin "2") (pinfunction "2_2") (pintype "passive"))
      (node (ref "U6") (pin "1") (pinfunction "1_1") (pintype "passive"))
    )
    (net (code "183") (name "Net-(R52-Pad2)") (class "Default")
      (node (ref "R52") (pin "2") (pinfunction "2_2") (pintype "passive"))
      (node (ref "U8") (pin "1") (pinfunction "1_1") (pintype "passive"))
    )
    (net (code "184") (name "Net-(R53-Pad2)") (class "Default")
      (node (ref "R53") (pin "2") (pinfunction "2_2") (pintype "passive"))
      (node (ref "U7") (pin "1") (pinfunction "1_1") (pintype "passive"))
    )
    (net (code "185") (name "Net-(R55-Pad2)") (class "Default")
      (node (ref "R55") (pin "2") (pinfunction "2_2") (pintype "passive"))
      (node (ref "R57") (pin "2") (pinfunction "2_2") (pintype "passive"))
      (node (ref "RAIN_SENSOR") (pin "1") (pinfunction "1_1") (pintype "passive"))
    )
    (net (code "186") (name "Net-(R62-Pad2)") (class "Default")
      (node (ref "R62") (pin "2") (pinfunction "2_2") (pintype "passive"))
      (node (ref "U10") (pin "1") (pinfunction "1_1") (pintype "passive"))
    )
    (net (code "187") (name "Net-(R78-Pad1)") (class "Default")
      (node (ref "R78") (pin "1") (pinfunction "1_1") (pintype "passive"))
      (node (ref "U13") (pin "1") (pinfunction "1_1") (pintype "passive"))
    )
    (net (code "188") (name "Net-(R81-Pad2)") (class "Default")
      (node (ref "R81") (pin "2") (pinfunction "2_2") (pintype "passive"))
      (node (ref "U9") (pin "4") (pinfunction "4_4") (pintype "passive"))
    )
    (net (code "189") (name "Net-(R101-Pad2)") (class "Default")
      (node (ref "R101") (pin "2") (pinfunction "2_2") (pintype "passive"))
      (node (ref "X5") (pin "8") (pinfunction "8_8") (pintype "input"))
    )
    (net (code "190") (name "Net-(R102-Pad2)") (class "Default")
      (node (ref "R102") (pin "2") (pinfunction "2_2") (pintype "passive"))
      (node (ref "X5") (pin "9") (pinfunction "9_9") (pintype "input"))
    )
    (net (code "191") (name "Net-(R119-Pad2)") (class "Default")
      (node (ref "R119") (pin "2") (pinfunction "2_2") (pintype "passive"))
      (node (ref "U12") (pin "1") (pinfunction "1_1") (pintype "passive"))
    )
    (net (code "192") (name "Net-(R120-Pad2)") (class "Default")
      (node (ref "R120") (pin "2") (pinfunction "2_2") (pintype "passive"))
      (node (ref "U9") (pin "1") (pinfunction "1_1") (pintype "passive"))
    )
    (net (code "193") (name "Net-(RTCC-VBAT)") (class "Default")
      (node (ref "BATT1") (pin "PLUS") (pinfunction "PLUS_PLUS") (pintype "bidirectional"))
      (node (ref "RTCC") (pin "8") (pinfunction "VBAT_8") (pintype "bidirectional"))
    )
    (net (code "194") (name "Net-(SD1-CP1)") (class "Default")
      (node (ref "C35") (pin "1") (pinfunction "1_1") (pintype "passive"))
      (node (ref "SD1") (pin "16") (pinfunction "CP1_16") (pintype "bidirectional"))
    )
    (net (code "195") (name "Net-(SD1-CP2)") (class "Default")
      (node (ref "C35") (pin "2") (pinfunction "2_2") (pintype "passive"))
      (node (ref "SD1") (pin "15") (pinfunction "CP2_15") (pintype "bidirectional"))
    )
    (net (code "196") (name "Net-(SD1-ISET)") (class "Default")
      (node (ref "R35") (pin "1") (pinfunction "1_1") (pintype "passive"))
      (node (ref "SD1") (pin "3") (pinfunction "ISET_3") (pintype "bidirectional"))
    )
    (net (code "197") (name "Net-(SD1-ROSC)") (class "Default")
      (node (ref "R3") (pin "2") (pinfunction "2_2") (pintype "passive"))
      (node (ref "SD1") (pin "5") (pinfunction "ROSC_5") (pintype "bidirectional"))
    )
    (net (code "198") (name "Net-(SD1-VCP)") (class "Default")
      (node (ref "C36") (pin "2") (pinfunction "2_2") (pintype "passive"))
      (node (ref "SD1") (pin "14") (pinfunction "VCP_14") (pintype "bidirectional"))
    )
    (net (code "199") (name "Net-(SD1-VG)") (class "Default")
      (node (ref "C34") (pin "1") (pinfunction "1_1") (pintype "passive"))
      (node (ref "SD1") (pin "17") (pinfunction "VG_17") (pintype "bidirectional"))
    )
    (net (code "200") (name "Net-(SD1-~{FAULT})") (class "Default")
      (node (ref "R32") (pin "2") (pinfunction "2_2") (pintype "passive"))
      (node (ref "SD1") (pin "2") (pinfunction "~{FAULT}_2") (pintype "bidirectional"))
    )
    (net (code "201") (name "Net-(SD2-CP1)") (class "Default")
      (node (ref "C52") (pin "1") (pinfunction "1_1") (pintype "passive"))
      (node (ref "SD2") (pin "16") (pinfunction "CP1_16") (pintype "bidirectional"))
    )
    (net (code "202") (name "Net-(SD2-CP2)") (class "Default")
      (node (ref "C52") (pin "2") (pinfunction "2_2") (pintype "passive"))
      (node (ref "SD2") (pin "15") (pinfunction "CP2_15") (pintype "bidirectional"))
    )
    (net (code "203") (name "Net-(SD2-ISET)") (class "Default")
      (node (ref "R41") (pin "1") (pinfunction "1_1") (pintype "passive"))
      (node (ref "SD2") (pin "3") (pinfunction "ISET_3") (pintype "bidirectional"))
    )
    (net (code "204") (name "Net-(SD2-ROSC)") (class "Default")
      (node (ref "R2") (pin "2") (pinfunction "2_2") (pintype "passive"))
      (node (ref "SD2") (pin "5") (pinfunction "ROSC_5") (pintype "bidirectional"))
    )
    (net (code "205") (name "Net-(SD2-VCP)") (class "Default")
      (node (ref "C53") (pin "2") (pinfunction "2_2") (pintype "passive"))
      (node (ref "SD2") (pin "14") (pinfunction "VCP_14") (pintype "bidirectional"))
    )
    (net (code "206") (name "Net-(SD2-VG)") (class "Default")
      (node (ref "C51") (pin "1") (pinfunction "1_1") (pintype "passive"))
      (node (ref "SD2") (pin "17") (pinfunction "VG_17") (pintype "bidirectional"))
    )
    (net (code "207") (name "Net-(SD2-~{FAULT})") (class "Default")
      (node (ref "R38") (pin "2") (pinfunction "2_2") (pintype "passive"))
      (node (ref "SD2") (pin "2") (pinfunction "~{FAULT}_2") (pintype "bidirectional"))
    )
    (net (code "208") (name "Net-(SD3-CP1)") (class "Default")
      (node (ref "C58") (pin "1") (pinfunction "1_1") (pintype "passive"))
      (node (ref "SD3") (pin "16") (pinfunction "CP1_16") (pintype "bidirectional"))
    )
    (net (code "209") (name "Net-(SD3-CP2)") (class "Default")
      (node (ref "C58") (pin "2") (pinfunction "2_2") (pintype "passive"))
      (node (ref "SD3") (pin "15") (pinfunction "CP2_15") (pintype "bidirectional"))
    )
    (net (code "210") (name "Net-(SD3-ISET)") (class "Default")
      (node (ref "R46") (pin "1") (pinfunction "1_1") (pintype "passive"))
      (node (ref "SD3") (pin "3") (pinfunction "ISET_3") (pintype "bidirectional"))
    )
    (net (code "211") (name "Net-(SD3-ROSC)") (class "Default")
      (node (ref "R42") (pin "2") (pinfunction "2_2") (pintype "passive"))
      (node (ref "SD3") (pin "5") (pinfunction "ROSC_5") (pintype "bidirectional"))
    )
    (net (code "212") (name "Net-(SD3-VCP)") (class "Default")
      (node (ref "C59") (pin "2") (pinfunction "2_2") (pintype "passive"))
      (node (ref "SD3") (pin "14") (pinfunction "VCP_14") (pintype "bidirectional"))
    )
    (net (code "213") (name "Net-(SD3-VG)") (class "Default")
      (node (ref "C57") (pin "1") (pinfunction "1_1") (pintype "passive"))
      (node (ref "SD3") (pin "17") (pinfunction "VG_17") (pintype "bidirectional"))
    )
    (net (code "214") (name "Net-(SD3-~{FAULT})") (class "Default")
      (node (ref "R43") (pin "2") (pinfunction "2_2") (pintype "passive"))
      (node (ref "SD3") (pin "2") (pinfunction "~{FAULT}_2") (pintype "bidirectional"))
    )
    (net (code "215") (name "Net-(STEPPER_0_CS-AOUT)") (class "Default")
      (node (ref "C19") (pin "1") (pinfunction "1_1") (pintype "passive"))
      (node (ref "R15") (pin "1") (pinfunction "1_1") (pintype "passive"))
      (node (ref "STEPPER_0_CS") (pin "4") (pinfunction "AOUT_4") (pintype "output"))
    )
    (net (code "216") (name "Net-(STEPPER_0_CS-VREF)") (class "Default")
      (node (ref "C24") (pin "1") (pinfunction "1_1") (pintype "passive"))
      (node (ref "R14") (pin "2") (pinfunction "2_2") (pintype "passive"))
      (node (ref "STEPPER_0_CS") (pin "3") (pinfunction "VREF_3") (pintype "bidirectional"))
    )
    (net (code "217") (name "Net-(STEPPER_1_CS-AOUT)") (class "Default")
      (node (ref "C25") (pin "1") (pinfunction "1_1") (pintype "passive"))
      (node (ref "R17") (pin "1") (pinfunction "1_1") (pintype "passive"))
      (node (ref "STEPPER_1_CS") (pin "4") (pinfunction "AOUT_4") (pintype "output"))
    )
    (net (code "218") (name "Net-(STEPPER_1_CS-VREF)") (class "Default")
      (node (ref "C27") (pin "1") (pinfunction "1_1") (pintype "passive"))
      (node (ref "R16") (pin "2") (pinfunction "2_2") (pintype "passive"))
      (node (ref "STEPPER_1_CS") (pin "3") (pinfunction "VREF_3") (pintype "bidirectional"))
    )
    (net (code "219") (name "Net-(U1-VDDCORE{slash}VCAP)") (class "Default")
      (node (ref "C7") (pin "1") (pinfunction "1_1") (pintype "passive"))
      (node (ref "U1") (pin "23") (pinfunction "VDDCORE/VCAP_23") (pintype "bidirectional"))
    )
    (net (code "220") (name "Net-(U2-C1)") (class "Default")
      (node (ref "C16") (pin "1") (pinfunction "1_1") (pintype "passive"))
      (node (ref "U2") (pin "4") (pinfunction "C1_4") (pintype "passive"))
    )
    (net (code "221") (name "Net-(U5-CPOUT)") (class "Default")
      (node (ref "C46") (pin "2") (pinfunction "2_2") (pintype "passive"))
      (node (ref "U5") (pin "20") (pinfunction "CPOUT_20") (pintype "output"))
    )
    (net (code "222") (name "Net-(U5-REGOUT)") (class "Default")
      (node (ref "C47") (pin "1") (pinfunction "1_1") (pintype "passive"))
      (node (ref "U5") (pin "10") (pinfunction "REGOUT_10") (pintype "passive"))
    )
    (net (code "223") (name "PERIMETER_WIRE_SENSE") (class "Default")
      (node (ref "D2") (pin "C") (pinfunction "C_C") (pintype "passive"))
      (node (ref "PERIM") (pin "TP") (pinfunction "TP_TP") (pintype "input"))
      (node (ref "R4") (pin "1") (pinfunction "1_1") (pintype "passive"))
      (node (ref "U15") (pin "4") (pinfunction "AN19/CVD19/RPG6/PWM10L/PMA5/RG6_4") (pintype "bidirectional"))
    )
    (net (code "224") (name "STEP_DRV_0_A1") (class "Default")
      (node (ref "SD1") (pin "23") (pinfunction "AOUT1_23") (pintype "bidirectional"))
      (node (ref "STEPPER_0") (pin "1") (pinfunction "1_1") (pintype "passive"))
    )
    (net (code "225") (name "STEP_DRV_0_A2") (class "Default")
      (node (ref "SD1") (pin "21") (pinfunction "AOUT2_21") (pintype "bidirectional"))
      (node (ref "STEPPER_0") (pin "2") (pinfunction "2_2") (pintype "passive"))
    )
    (net (code "226") (name "STEP_DRV_0_B1") (class "Default")
      (node (ref "SD1") (pin "9") (pinfunction "BOUT1_9") (pintype "bidirectional"))
      (node (ref "STEPPER_0") (pin "3") (pinfunction "3_3") (pintype "passive"))
    )
    (net (code "227") (name "STEP_DRV_0_B2") (class "Default")
      (node (ref "SD1") (pin "11") (pinfunction "BOUT2_11") (pintype "bidirectional"))
      (node (ref "STEPPER_0") (pin "4") (pinfunction "4_4") (pintype "passive"))
    )
    (net (code "228") (name "STEP_DRV_0_FAULT") (class "Default")
      (node (ref "R32") (pin "1") (pinfunction "1_1") (pintype "passive"))
      (node (ref "R33") (pin "2") (pinfunction "2_2") (pintype "passive"))
    )
    (net (code "229") (name "STEP_DRV_0_SLEEP") (class "Default")
      (node (ref "R33") (pin "1") (pinfunction "1_1") (pintype "passive"))
      (node (ref "R34") (pin "2") (pinfunction "2_2") (pintype "passive"))
      (node (ref "SD1") (pin "19") (pinfunction "~{SLEEP}_19") (pintype "bidirectional"))
    )
    (net (code "230") (name "STEP_DRV_1_A1") (class "Default")
      (node (ref "SD2") (pin "23") (pinfunction "AOUT1_23") (pintype "bidirectional"))
      (node (ref "STEPPER_1") (pin "1") (pinfunction "1_1") (pintype "passive"))
    )
    (net (code "231") (name "STEP_DRV_1_A2") (class "Default")
      (node (ref "SD2") (pin "21") (pinfunction "AOUT2_21") (pintype "bidirectional"))
      (node (ref "STEPPER_1") (pin "2") (pinfunction "2_2") (pintype "passive"))
    )
    (net (code "232") (name "STEP_DRV_1_B1") (class "Default")
      (node (ref "SD2") (pin "9") (pinfunction "BOUT1_9") (pintype "bidirectional"))
      (node (ref "STEPPER_1") (pin "3") (pinfunction "3_3") (pintype "passive"))
    )
    (net (code "233") (name "STEP_DRV_1_B2") (class "Default")
      (node (ref "SD2") (pin "11") (pinfunction "BOUT2_11") (pintype "bidirectional"))
      (node (ref "STEPPER_1") (pin "4") (pinfunction "4_4") (pintype "passive"))
    )
    (net (code "234") (name "STEP_DRV_1_FAULT") (class "Default")
      (node (ref "R38") (pin "1") (pinfunction "1_1") (pintype "passive"))
      (node (ref "R39") (pin "2") (pinfunction "2_2") (pintype "passive"))
    )
    (net (code "235") (name "STEP_DRV_1_SLEEP") (class "Default")
      (node (ref "R39") (pin "1") (pinfunction "1_1") (pintype "passive"))
      (node (ref "R40") (pin "2") (pinfunction "2_2") (pintype "passive"))
      (node (ref "SD2") (pin "19") (pinfunction "~{SLEEP}_19") (pintype "bidirectional"))
    )
    (net (code "236") (name "STEP_DRV_2_A1") (class "Default")
      (node (ref "SD3") (pin "23") (pinfunction "AOUT1_23") (pintype "bidirectional"))
      (node (ref "STEPPER_2") (pin "1") (pinfunction "1_1") (pintype "passive"))
    )
    (net (code "237") (name "STEP_DRV_2_A2") (class "Default")
      (node (ref "SD3") (pin "21") (pinfunction "AOUT2_21") (pintype "bidirectional"))
      (node (ref "STEPPER_2") (pin "2") (pinfunction "2_2") (pintype "passive"))
    )
    (net (code "238") (name "STEP_DRV_2_B1") (class "Default")
      (node (ref "SD3") (pin "9") (pinfunction "BOUT1_9") (pintype "bidirectional"))
      (node (ref "STEPPER_2") (pin "3") (pinfunction "3_3") (pintype "passive"))
    )
    (net (code "239") (name "STEP_DRV_2_B2") (class "Default")
      (node (ref "SD3") (pin "11") (pinfunction "BOUT2_11") (pintype "bidirectional"))
      (node (ref "STEPPER_2") (pin "4") (pinfunction "4_4") (pintype "passive"))
    )
    (net (code "240") (name "STEP_DRV_2_FAULT") (class "Default")
      (node (ref "R43") (pin "1") (pinfunction "1_1") (pintype "passive"))
      (node (ref "R44") (pin "2") (pinfunction "2_2") (pintype "passive"))
    )
    (net (code "241") (name "STEP_DRV_2_SLEEP") (class "Default")
      (node (ref "R44") (pin "1") (pinfunction "1_1") (pintype "passive"))
      (node (ref "R45") (pin "2") (pinfunction "2_2") (pintype "passive"))
      (node (ref "SD3") (pin "19") (pinfunction "~{SLEEP}_19") (pintype "bidirectional"))
    )
    (net (code "242") (name "VBUS") (class "Default")
      (node (ref "U15") (pin "34") (pinfunction "VBUS_34") (pintype "power_in"))
    )
    (net (code "243") (name "unconnected-(CAMERA-Pad2)") (class "Default")
      (node (ref "CAMERA") (pin "2") (pinfunction "2_2") (pintype "passive"))
    )
    (net (code "244") (name "unconnected-(CP2102-DTR-Pad28)") (class "Default")
      (node (ref "CP2102") (pin "28") (pinfunction "DTR_28") (pintype "output"))
    )
    (net (code "245") (name "unconnected-(CP2102-RTS-Pad24)") (class "Default")
      (node (ref "CP2102") (pin "24") (pinfunction "RTS_24") (pintype "output"))
    )
    (net (code "246") (name "unconnected-(CURRENT_SENSOR_BATT-OCD1-Pad5)") (class "Default")
      (node (ref "CURRENT_SENSOR_BATT") (pin "5") (pinfunction "OCD1_5") (pintype "output"))
    )
    (net (code "247") (name "unconnected-(CURRENT_SENSOR_BATT-OCD2-Pad6)") (class "Default")
      (node (ref "CURRENT_SENSOR_BATT") (pin "6") (pinfunction "OCD2_6") (pintype "output"))
    )
    (net (code "248") (name "unconnected-(H1-MOUNT-PadB3,0)") (class "Default")
      (node (ref "H1") (pin "B3,0") (pinfunction "MOUNT_B3,0") (pintype "passive"))
    )
    (net (code "249") (name "unconnected-(H2-MOUNT-PadB3,0)") (class "Default")
      (node (ref "H2") (pin "B3,0") (pinfunction "MOUNT_B3,0") (pintype "passive"))
    )
    (net (code "250") (name "unconnected-(H3-MOUNT-PadB3,0)") (class "Default")
      (node (ref "H3") (pin "B3,0") (pinfunction "MOUNT_B3,0") (pintype "passive"))
    )
    (net (code "251") (name "unconnected-(H4-MOUNT-PadB3,0)") (class "Default")
      (node (ref "H4") (pin "B3,0") (pinfunction "MOUNT_B3,0") (pintype "passive"))
    )
    (net (code "252") (name "unconnected-(H5-MOUNT-PadB3,0)") (class "Default")
      (node (ref "H5") (pin "B3,0") (pinfunction "MOUNT_B3,0") (pintype "passive"))
    )
    (net (code "253") (name "unconnected-(H6-MOUNT-PadB3,0)") (class "Default")
      (node (ref "H6") (pin "B3,0") (pinfunction "MOUNT_B3,0") (pintype "passive"))
    )
    (net (code "254") (name "unconnected-(LIDAR-Pad3)") (class "Default")
      (node (ref "LIDAR") (pin "3") (pinfunction "3_3") (pintype "passive"))
    )
    (net (code "255") (name "unconnected-(LIDAR-Pad6)") (class "Default")
      (node (ref "LIDAR") (pin "6") (pinfunction "6_6") (pintype "passive"))
    )
    (net (code "256") (name "unconnected-(LIDAR-Pad8)") (class "Default")
      (node (ref "LIDAR") (pin "8") (pinfunction "8_8") (pintype "passive"))
    )
    (net (code "257") (name "unconnected-(MAIN_MOTOR_CS-OCD1-Pad5)") (class "Default")
      (node (ref "MAIN_MOTOR_CS") (pin "5") (pinfunction "OCD1_5") (pintype "output"))
    )
    (net (code "258") (name "unconnected-(MAIN_MOTOR_CS-OCD2-Pad6)") (class "Default")
      (node (ref "MAIN_MOTOR_CS") (pin "6") (pinfunction "OCD2_6") (pintype "output"))
    )
    (net (code "259") (name "unconnected-(MCU_0-NC1-PadA)") (class "Default")
      (node (ref "MCU_0") (pin "A") (pinfunction "NC1_A") (pintype "bidirectional"))
    )
    (net (code "260") (name "unconnected-(MCU_0-NC2-PadB)") (class "Default")
      (node (ref "MCU_0") (pin "B") (pinfunction "NC2_B") (pintype "bidirectional"))
    )
    (net (code "261") (name "unconnected-(MCU_1-NC1-PadA)") (class "Default")
      (node (ref "MCU_1") (pin "A") (pinfunction "NC1_A") (pintype "bidirectional"))
    )
    (net (code "262") (name "unconnected-(MCU_1-NC2-PadB)") (class "Default")
      (node (ref "MCU_1") (pin "B") (pinfunction "NC2_B") (pintype "bidirectional"))
    )
    (net (code "263") (name "unconnected-(MCU_2-NC1-PadA)") (class "Default")
      (node (ref "MCU_2") (pin "A") (pinfunction "NC1_A") (pintype "bidirectional"))
    )
    (net (code "264") (name "unconnected-(MCU_2-NC2-PadB)") (class "Default")
      (node (ref "MCU_2") (pin "B") (pinfunction "NC2_B") (pintype "bidirectional"))
    )
    (net (code "265") (name "unconnected-(MCU_3_ESP32-CLK-Pad20)") (class "Default")
      (node (ref "MCU_3_ESP32") (pin "20") (pinfunction "CLK_20") (pintype "bidirectional"))
    )
    (net (code "266") (name "unconnected-(MCU_3_ESP32-CMD-Pad19)") (class "Default")
      (node (ref "MCU_3_ESP32") (pin "19") (pinfunction "CMD_19") (pintype "bidirectional"))
    )
    (net (code "267") (name "unconnected-(MCU_3_ESP32-SVN-Pad5)") (class "Default")
      (node (ref "MCU_3_ESP32") (pin "5") (pinfunction "SVN_5") (pintype "bidirectional"))
    )
    (net (code "268") (name "unconnected-(MCU_3_ESP32-SVP-Pad4)") (class "Default")
      (node (ref "MCU_3_ESP32") (pin "4") (pinfunction "SVP_4") (pintype "bidirectional"))
    )
    (net (code "269") (name "unconnected-(RTCC-CLKOUT-Pad5)") (class "Default")
      (node (ref "RTCC") (pin "5") (pinfunction "CLKOUT_5") (pintype "bidirectional"))
    )
    (net (code "270") (name "unconnected-(RTCC-NC-Pad9)") (class "Default")
      (node (ref "RTCC") (pin "9") (pinfunction "NC_9") (pintype "bidirectional"))
    )
    (net (code "271") (name "unconnected-(RTCC-NC-Pad10)") (class "Default")
      (node (ref "RTCC") (pin "10") (pinfunction "NC_10") (pintype "bidirectional"))
    )
    (net (code "272") (name "unconnected-(RTCC-~{INT_1}-Pad2)") (class "Default")
      (node (ref "RTCC") (pin "2") (pinfunction "~{INT_1}_2") (pintype "bidirectional"))
    )
    (net (code "273") (name "unconnected-(RTCC-~{INT_2}-Pad6)") (class "Default")
      (node (ref "RTCC") (pin "6") (pinfunction "~{INT_2}_6") (pintype "bidirectional"))
    )
    (net (code "274") (name "unconnected-(STEPPER_0_CS-OCD1-Pad5)") (class "Default")
      (node (ref "STEPPER_0_CS") (pin "5") (pinfunction "OCD1_5") (pintype "output"))
    )
    (net (code "275") (name "unconnected-(STEPPER_0_CS-OCD2-Pad6)") (class "Default")
      (node (ref "STEPPER_0_CS") (pin "6") (pinfunction "OCD2_6") (pintype "output"))
    )
    (net (code "276") (name "unconnected-(STEPPER_1_CS-OCD1-Pad5)") (class "Default")
      (node (ref "STEPPER_1_CS") (pin "5") (pinfunction "OCD1_5") (pintype "output"))
    )
    (net (code "277") (name "unconnected-(STEPPER_1_CS-OCD2-Pad6)") (class "Default")
      (node (ref "STEPPER_1_CS") (pin "6") (pinfunction "OCD2_6") (pintype "output"))
    )
    (net (code "278") (name "unconnected-(U1-NC-Pad34)") (class "Default")
      (node (ref "U1") (pin "34") (pinfunction "NC_34") (pintype "no_connect"))
    )
    (net (code "279") (name "unconnected-(U1-NC_2-Pad12)") (class "Default")
      (node (ref "U1") (pin "12") (pinfunction "NC_2_12") (pintype "no_connect"))
    )
    (net (code "280") (name "unconnected-(U1-NC_3-Pad13)") (class "Default")
      (node (ref "U1") (pin "13") (pinfunction "NC_3_13") (pintype "no_connect"))
    )
    (net (code "281") (name "unconnected-(U1-NC_4-Pad33)") (class "Default")
      (node (ref "U1") (pin "33") (pinfunction "NC_4_33") (pintype "no_connect"))
    )
    (net (code "282") (name "unconnected-(U1-OSC1{slash}CLKI{slash}RA7-Pad30)") (class "Default")
      (node (ref "U1") (pin "30") (pinfunction "OSC1/CLKI/RA7_30") (pintype "bidirectional"))
    )
    (net (code "283") (name "unconnected-(U1-OSC2{slash}CLKO{slash}RA6-Pad31)") (class "Default")
      (node (ref "U1") (pin "31") (pinfunction "OSC2/CLKO/RA6_31") (pintype "bidirectional"))
    )
    (net (code "284") (name "unconnected-(U1-RA3{slash}AN3{slash}C1INB{slash}VREF+-Pad22)") (class "Default")
      (node (ref "U1") (pin "22") (pinfunction "RA3/AN3/C1INB/VREF+_22") (pintype "bidirectional"))
    )
    (net (code "285") (name "unconnected-(U1-RB4{slash}CCP4{slash}PMA1{slash}KBI0{slash}RP7-Pad14)") (class "Default")
      (node (ref "U1") (pin "14") (pinfunction "RB4/CCP4/PMA1/KBI0/RP7_14") (pintype "bidirectional"))
    )
    (net (code "286") (name "unconnected-(U1-RC3{slash}SCK1{slash}SCL1{slash}RP14-Pad37)") (class "Default")
      (node (ref "U1") (pin "37") (pinfunction "RC3/SCK1/SCL1/RP14_37") (pintype "bidirectional"))
    )
    (net (code "287") (name "unconnected-(U1-RC4{slash}SDI1{slash}SDA1{slash}RP15-Pad42)") (class "Default")
      (node (ref "U1") (pin "42") (pinfunction "RC4/SDI1/SDA1/RP15_42") (pintype "bidirectional"))
    )
    (net (code "288") (name "unconnected-(U1-RC5{slash}SDO1{slash}RP16-Pad43)") (class "Default")
      (node (ref "U1") (pin "43") (pinfunction "RC5/SDO1/RP16_43") (pintype "bidirectional"))
    )
    (net (code "289") (name "unconnected-(U2-DRDY-Pad8)") (class "Default")
      (node (ref "U2") (pin "8") (pinfunction "DRDY_8") (pintype "output"))
    )
    (net (code "290") (name "unconnected-(U2-INT-Pad7)") (class "Default")
      (node (ref "U2") (pin "7") (pinfunction "INT_7") (pintype "output"))
    )
    (net (code "291") (name "unconnected-(U5-AUX_CL-Pad7)") (class "Default")
      (node (ref "U5") (pin "7") (pinfunction "AUX_CL_7") (pintype "bidirectional"))
    )
    (net (code "292") (name "unconnected-(U5-AUX_DA-Pad6)") (class "Default")
      (node (ref "U5") (pin "6") (pinfunction "AUX_DA_6") (pintype "bidirectional"))
    )
    (net (code "293") (name "unconnected-(U5-NC_2-Pad2)") (class "Default")
      (node (ref "U5") (pin "2") (pinfunction "NC_2_2") (pintype "passive"))
    )
    (net (code "294") (name "unconnected-(U5-NC_3-Pad3)") (class "Default")
      (node (ref "U5") (pin "3") (pinfunction "NC_3_3") (pintype "passive"))
    )
    (net (code "295") (name "unconnected-(U5-NC_4-Pad4)") (class "Default")
      (node (ref "U5") (pin "4") (pinfunction "NC_4_4") (pintype "passive"))
    )
    (net (code "296") (name "unconnected-(U5-NC_5-Pad5)") (class "Default")
      (node (ref "U5") (pin "5") (pinfunction "NC_5_5") (pintype "passive"))
    )
    (net (code "297") (name "unconnected-(U5-NC_14-Pad14)") (class "Default")
      (node (ref "U5") (pin "14") (pinfunction "NC_14_14") (pintype "passive"))
    )
    (net (code "298") (name "unconnected-(U5-NC_15-Pad15)") (class "Default")
      (node (ref "U5") (pin "15") (pinfunction "NC_15_15") (pintype "passive"))
    )
    (net (code "299") (name "unconnected-(U5-NC_16-Pad16)") (class "Default")
      (node (ref "U5") (pin "16") (pinfunction "NC_16_16") (pintype "passive"))
    )
    (net (code "300") (name "unconnected-(U5-NC_17-Pad17)") (class "Default")
      (node (ref "U5") (pin "17") (pinfunction "NC_17_17") (pintype "passive"))
    )
    (net (code "301") (name "unconnected-(U5-RESV_19-Pad19)") (class "Default")
      (node (ref "U5") (pin "19") (pinfunction "RESV_19_19") (pintype "passive"))
    )
    (net (code "302") (name "unconnected-(U5-RESV_21-Pad21)") (class "Default")
      (node (ref "U5") (pin "21") (pinfunction "RESV_21_21") (pintype "passive"))
    )
    (net (code "303") (name "unconnected-(U5-RESV_22-Pad22)") (class "Default")
      (node (ref "U5") (pin "22") (pinfunction "RESV_22_22") (pintype "passive"))
    )
    (net (code "304") (name "unconnected-(U15-AN10{slash}CVD10{slash}RPA12{slash}RA12-Pad11)") (class "Default")
      (node (ref "U15") (pin "11") (pinfunction "AN10/CVD10/RPA12/RA12_11") (pintype "bidirectional"))
    )
    (net (code "305") (name "unconnected-(U15-AN11{slash}CVD11{slash}C1IN2-{slash}FLT4{slash}PMA12{slash}RC11-Pad24)") (class "Default")
      (node (ref "U15") (pin "24") (pinfunction "AN11/CVD11/C1IN2-/FLT4/PMA12/RC11_24") (pintype "bidirectional"))
    )
    (net (code "306") (name "unconnected-(U15-AN14{slash}CVD14{slash}RPE14{slash}FLT7{slash}PMA1{slash}RE14-Pad29)") (class "Default")
      (node (ref "U15") (pin "29") (pinfunction "AN14/CVD14/RPE14/FLT7/PMA1/RE14_29") (pintype "bidirectional"))
    )
    (net (code "307") (name "unconnected-(U15-AN15{slash}CVD15{slash}RPE15{slash}FLT8{slash}PMA0{slash}RE15-Pad30)") (class "Default")
      (node (ref "U15") (pin "30") (pinfunction "AN15/CVD15/RPE15/FLT8/PMA0/RE15_30") (pintype "bidirectional"))
    )
    (net (code "308") (name "unconnected-(U15-AN16{slash}CVD16{slash}RPG9{slash}PMA2{slash}RG9-Pad8)") (class "Default")
      (node (ref "U15") (pin "8") (pinfunction "AN16/CVD16/RPG9/PMA2/RG9_8") (pintype "bidirectional"))
    )
    (net (code "309") (name "unconnected-(U15-AN17{slash}CVD17{slash}RPG8{slash}SDA1{slash}PMA3{slash}RG8-Pad6)") (class "Default")
      (node (ref "U15") (pin "6") (pinfunction "AN17/CVD17/RPG8/SDA1/PMA3/RG8_6") (pintype "bidirectional"))
    )
    (net (code "310") (name "unconnected-(U15-AN18{slash}CVD18{slash}RPG7{slash}PWM10H{slash}SCL1{slash}PMA4{slash}RG7-Pad5)") (class "Default")
      (node (ref "U15") (pin "5") (pinfunction "AN18/CVD18/RPG7/PWM10H/SCL1/PMA4/RG7_5") (pintype "bidirectional"))
    )
    (net (code "311") (name "unconnected-(U15-D+-Pad37)") (class "Default")
      (node (ref "U15") (pin "37") (pinfunction "D+_37") (pintype "bidirectional"))
    )
    (net (code "312") (name "unconnected-(U15-D--Pad36)") (class "Default")
      (node (ref "U15") (pin "36") (pinfunction "D-_36") (pintype "bidirectional"))
    )
    (net (code "313") (name "unconnected-(U15-DAC2{slash}AN48{slash}CVD48{slash}RPC10{slash}PMA14{slash}PMCS{slash}RC10-Pad45)") (class "Default")
      (node (ref "U15") (pin "45") (pinfunction "DAC2/AN48/CVD48/RPC10/PMA14/PMCS/RC10_45") (pintype "bidirectional"))
    )
    (net (code "314") (name "unconnected-(U15-FLT15{slash}RPB4{slash}SCL2{slash}PMA8{slash}RB4-Pad32)") (class "Default")
      (node (ref "U15") (pin "32") (pinfunction "FLT15/RPB4/SCL2/PMA8/RB4_32") (pintype "bidirectional"))
    )
    (net (code "315") (name "unconnected-(U15-OA2IN+{slash}AN1{slash}C2IN1+{slash}RPA1{slash}RA1-Pad14)") (class "Default")
      (node (ref "U15") (pin "14") (pinfunction "OA2IN+/AN1/C2IN1+/RPA1/RA1_14") (pintype "bidirectional"))
    )
    (net (code "316") (name "unconnected-(U15-OA2OUT{slash}AN0{slash}C2IN4-{slash}C4IN3-{slash}RPA0{slash}RA0-Pad13)") (class "Default")
      (node (ref "U15") (pin "13") (pinfunction "OA2OUT/AN0/C2IN4-/C4IN3-/RPA0/RA0_13") (pintype "bidirectional"))
    )
    (net (code "317") (name "unconnected-(U15-OA3IN+{slash}AN8{slash}CVD8{slash}C3IN1+{slash}C3IN3-{slash}RPC2{slash}FLT3{slash}PMA13{slash}RC2-Pad23)") (class "Default")
      (node (ref "U15") (pin "23") (pinfunction "OA3IN+/AN8/CVD8/C3IN1+/C3IN3-/RPC2/FLT3/PMA13/RC2_23") (pintype "bidirectional"))
    )
    (net (code "318") (name "unconnected-(U15-OSCI{slash}CLKI{slash}AN49{slash}CVD49{slash}RPC12{slash}RC12-Pad39)") (class "Default")
      (node (ref "U15") (pin "39") (pinfunction "OSCI/CLKI/AN49/CVD49/RPC12/RC12_39") (pintype "bidirectional"))
    )
    (net (code "319") (name "unconnected-(U15-PGC2{slash}RPB6{slash}SCL3{slash}SCK2{slash}PMA15{slash}RB6-Pad44)") (class "Default")
      (node (ref "U15") (pin "44") (pinfunction "PGC2/RPB6/SCL3/SCK2/PMA15/RB6_44") (pintype "bidirectional"))
    )
    (net (code "320") (name "unconnected-(U15-PGC3{slash}OA1OUT{slash}VREF+{slash}AN3{slash}C1IN4-{slash}C4IN2-{slash}RPB1{slash}CTED1{slash}PMA6{slash}RB1-Pad16)") (class "Default")
      (node (ref "U15") (pin "16") (pinfunction "PGC3/OA1OUT/VREF+/AN3/C1IN4-/C4IN2-/RPB1/CTED1/PMA6/RB1_16") (pintype "bidirectional"))
    )
    (net (code "321") (name "unconnected-(U15-PGD3{slash}VREF-{slash}OA2IN-{slash}AN2{slash}C2IN1-{slash}RPB0{slash}CTED2{slash}RB0-Pad15)") (class "Default")
      (node (ref "U15") (pin "15") (pinfunction "PGD3/VREF-/OA2IN-/AN2/C2IN1-/RPB0/CTED2/RB0_15") (pintype "bidirectional"))
    )
    (net (code "322") (name "unconnected-(U15-RPB11{slash}PWM9H{slash}PWM3L{slash}PMD1{slash}RB11-Pad61)") (class "Default")
      (node (ref "U15") (pin "61") (pinfunction "RPB11/PWM9H/PWM3L/PMD1/RB11_61") (pintype "bidirectional"))
    )
    (net (code "323") (name "unconnected-(U15-RPB12{slash}PWM2H{slash}PMD2{slash}RB12-Pad62)") (class "Default")
      (node (ref "U15") (pin "62") (pinfunction "RPB12/PWM2H/PMD2/RB12_62") (pintype "bidirectional"))
    )
    (net (code "324") (name "unconnected-(U15-RPB13{slash}PWM8H{slash}PWM2L{slash}CTPLS{slash}PMD3{slash}RB13-Pad63)") (class "Default")
      (node (ref "U15") (pin "63") (pinfunction "RPB13/PWM8H/PWM2L/CTPLS/PMD3/RB13_63") (pintype "bidirectional"))
    )
    (net (code "325") (name "unconnected-(U15-RPB15{slash}PWM7H{slash}PWM1L{slash}PMD7{slash}RB15-Pad3)") (class "Default")
      (node (ref "U15") (pin "3") (pinfunction "RPB15/PWM7H/PWM1L/PMD7/RB15_3") (pintype "bidirectional"))
    )
    (net (code "326") (name "unconnected-(U15-RPC9{slash}PWM11H{slash}PWM5L{slash}RC9-Pad55)") (class "Default")
      (node (ref "U15") (pin "55") (pinfunction "RPC9/PWM11H/PWM5L/RC9_55") (pintype "bidirectional"))
    )
    (net (code "327") (name "unconnected-(U15-RPF0{slash}PWM11H{slash}RF0-Pad58)") (class "Default")
      (node (ref "U15") (pin "58") (pinfunction "RPF0/PWM11H/RF0_58") (pintype "bidirectional"))
    )
    (net (code "328") (name "unconnected-(U15-RPF1{slash}PWM11L{slash}RF1-Pad59)") (class "Default")
      (node (ref "U15") (pin "59") (pinfunction "RPF1/PWM11L/RF1_59") (pintype "bidirectional"))
    )
    (net (code "329") (name "unconnected-(U15-SOSCI{slash}RPC13{slash}RC13-Pad47)") (class "Default")
      (node (ref "U15") (pin "47") (pinfunction "SOSCI/RPC13/RC13_47") (pintype "bidirectional"))
    )
    (net (code "330") (name "unconnected-(U15-SOSCO{slash}T1CK{slash}RPB8{slash}RB8-Pad48)") (class "Default")
      (node (ref "U15") (pin "48") (pinfunction "SOSCO/T1CK/RPB8/RB8_48") (pintype "bidirectional"))
    )
    (net (code "331") (name "unconnected-(U15-TDI{slash}DAC3{slash}AN26{slash}CVD26{slash}RPA8{slash}SDA2{slash}PMA9{slash}RA8-Pad31)") (class "Default")
      (node (ref "U15") (pin "31") (pinfunction "TDI/DAC3/AN26/CVD26/RPA8/SDA2/PMA9/RA8_31") (pintype "bidirectional"))
    )
    (net (code "332") (name "unconnected-(U15-TDO{slash}PWM4H{slash}PMD4{slash}RA10-Pad64)") (class "Default")
      (node (ref "U15") (pin "64") (pinfunction "TDO/PWM4H/PMD4/RA10_64") (pintype "bidirectional"))
    )
    (net (code "333") (name "unconnected-(U15-TMS{slash}OA5IN-{slash}AN27{slash}CVD27{slash}LVDIN{slash}C5IN1-{slash}RPB9{slash}RB9-Pad49)") (class "Default")
      (node (ref "U15") (pin "49") (pinfunction "TMS/OA5IN-/AN27/CVD27/LVDIN/C5IN1-/RPB9/RB9_49") (pintype "bidirectional"))
    )
    (net (code "334") (name "unconnected-(U15-TRCLK{slash}RPC6{slash}PWM6H{slash}RC6-Pad50)") (class "Default")
      (node (ref "U15") (pin "50") (pinfunction "TRCLK/RPC6/PWM6H/RC6_50") (pintype "bidirectional"))
    )
    (net (code "335") (name "~{CP_SUSPEND}") (class "Default")
      (node (ref "CP2102") (pin "11") (pinfunction "~{SUSPEND}_11") (pintype "output"))
      (node (ref "R49") (pin "2") (pinfunction "2_2") (pintype "passive"))
    )
  )
)
